# bluepill-breakout.net
KiCad netlist of a schematic drawn in EAGLE
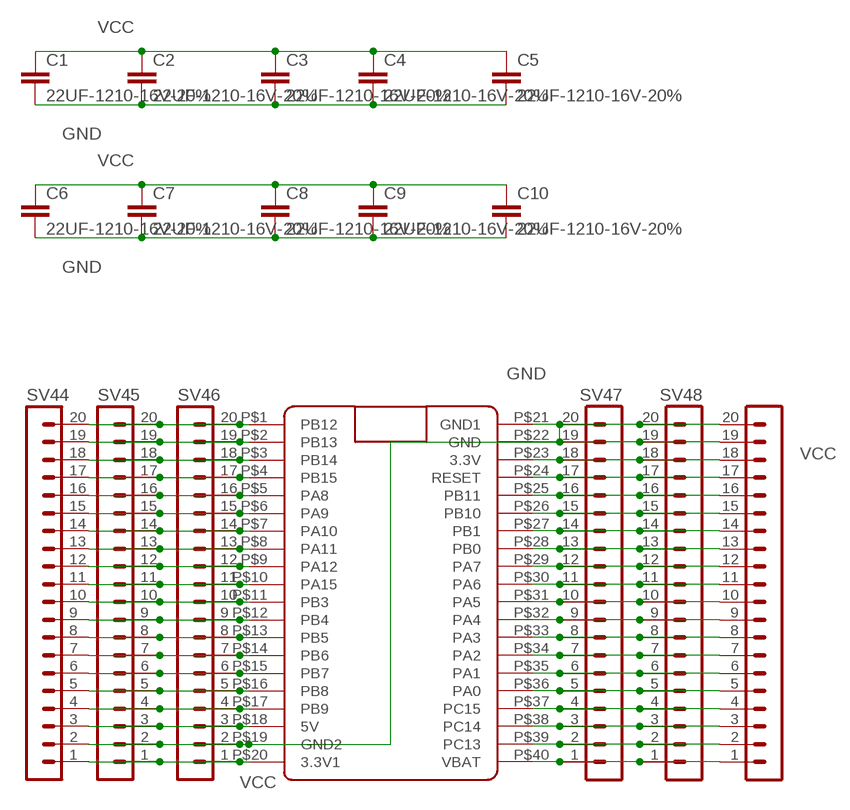
[diagram p0: schematic, sheet 1]
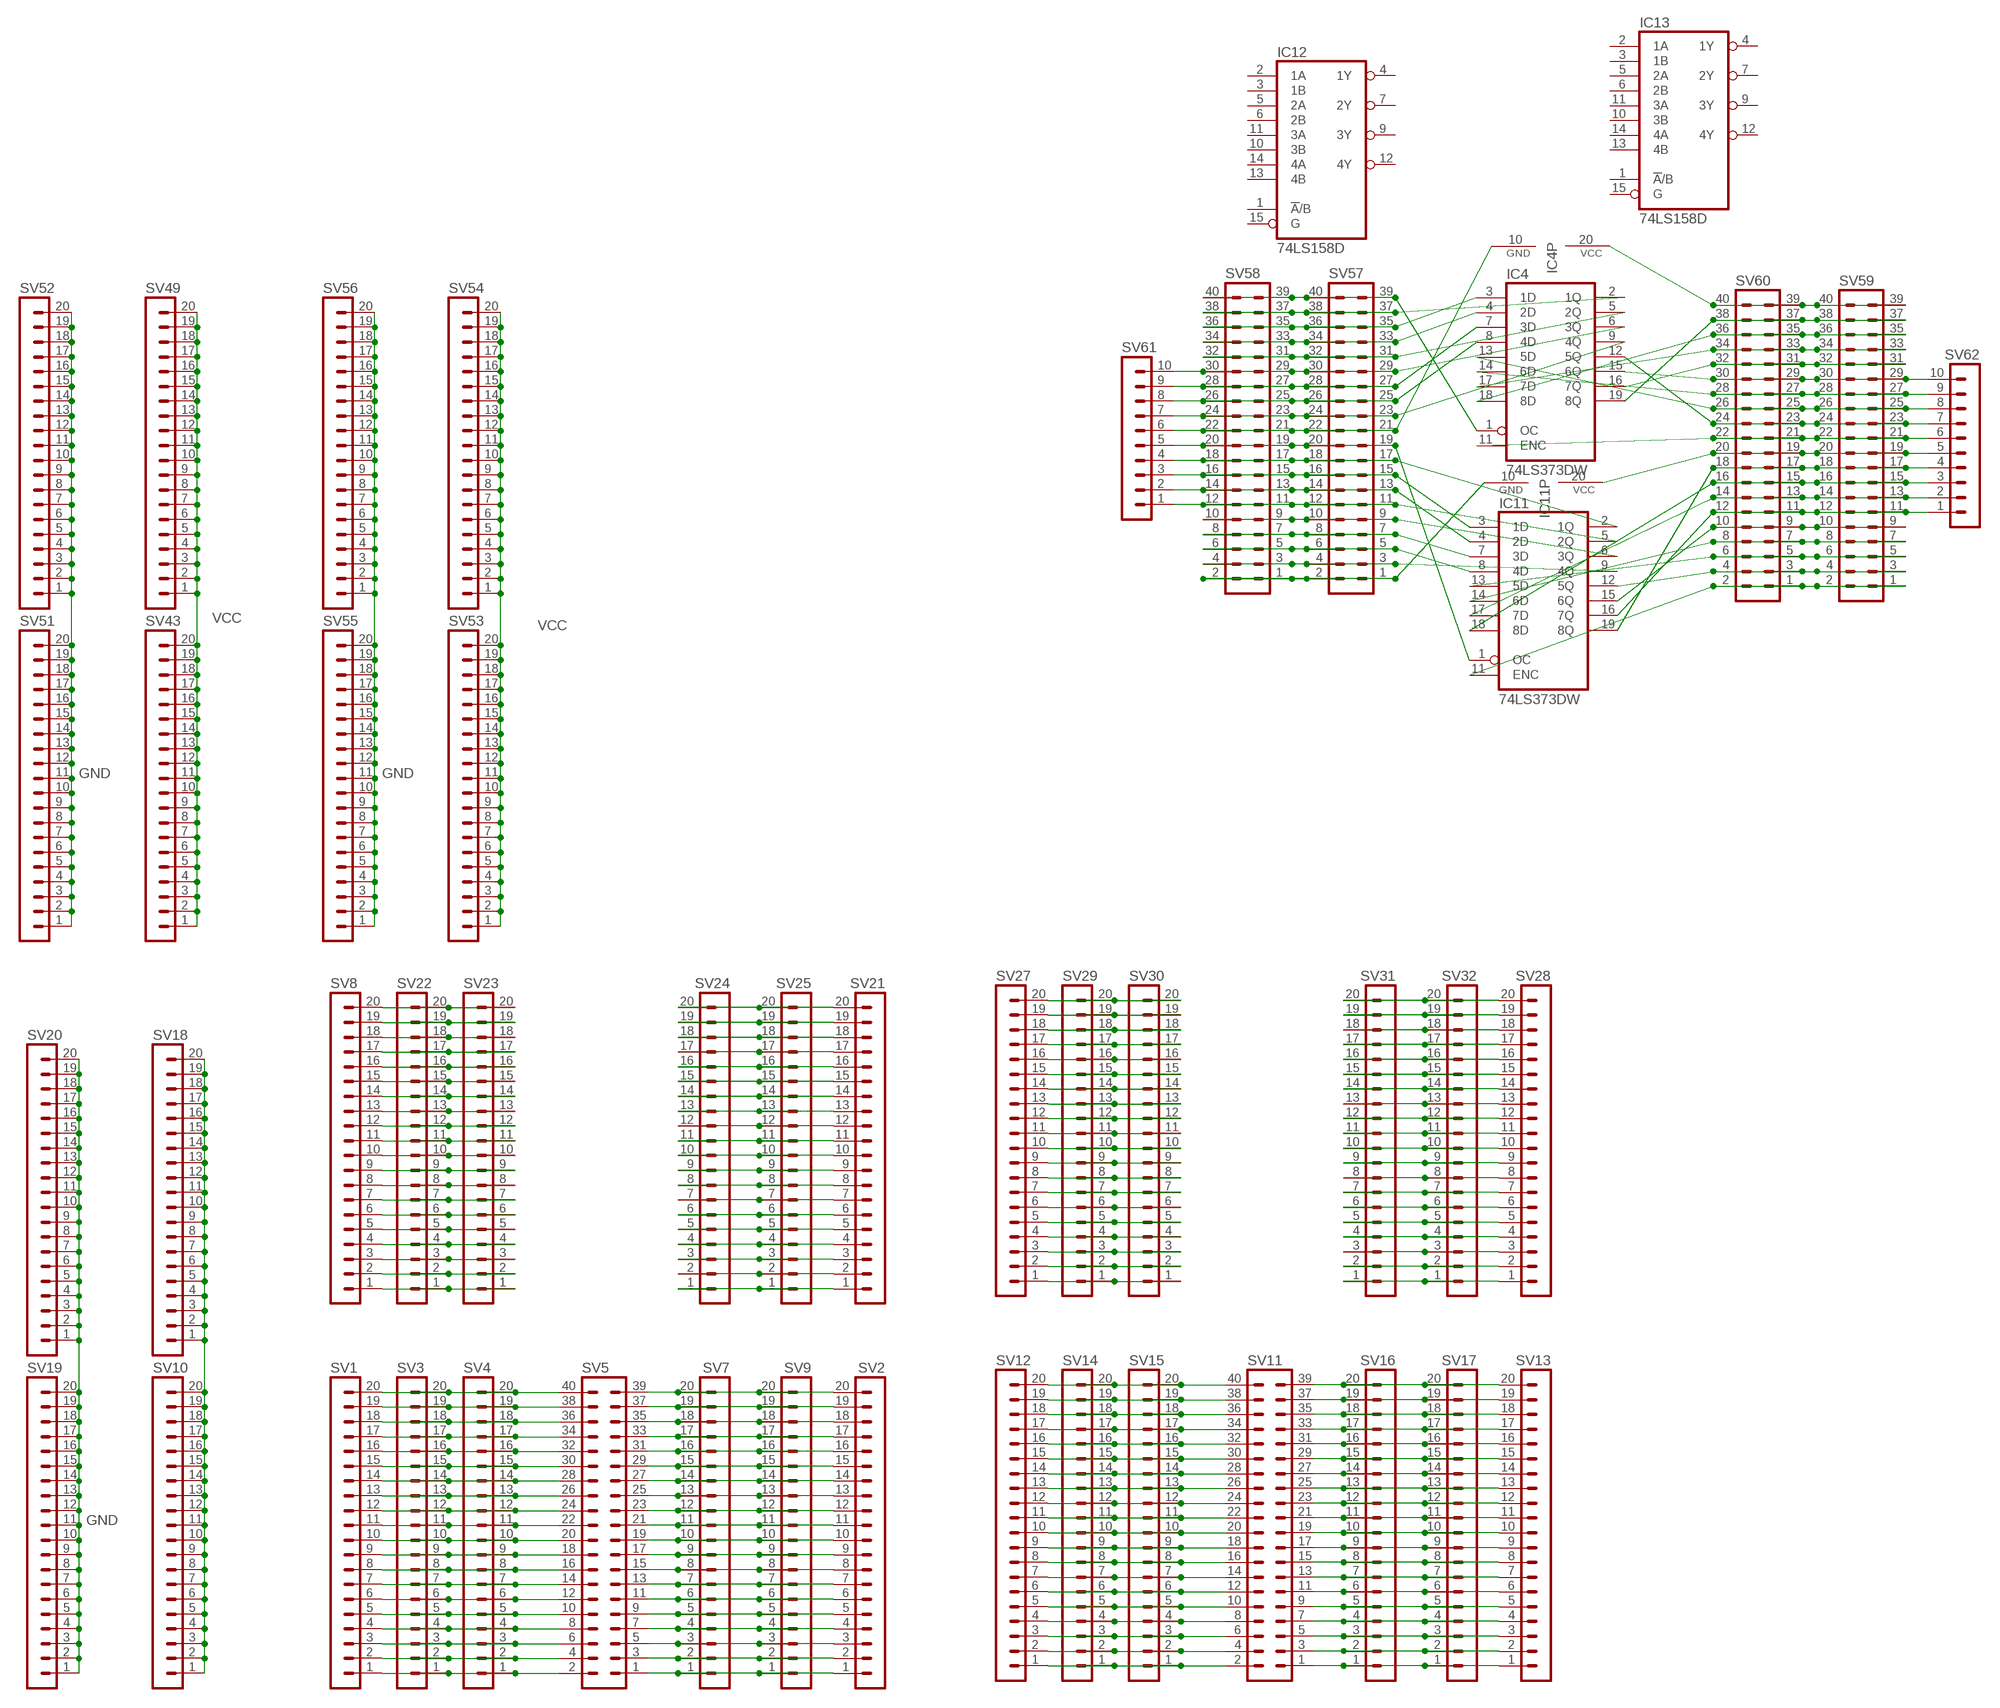
[diagram p1: schematic, sheet 2, part 1 of 2]
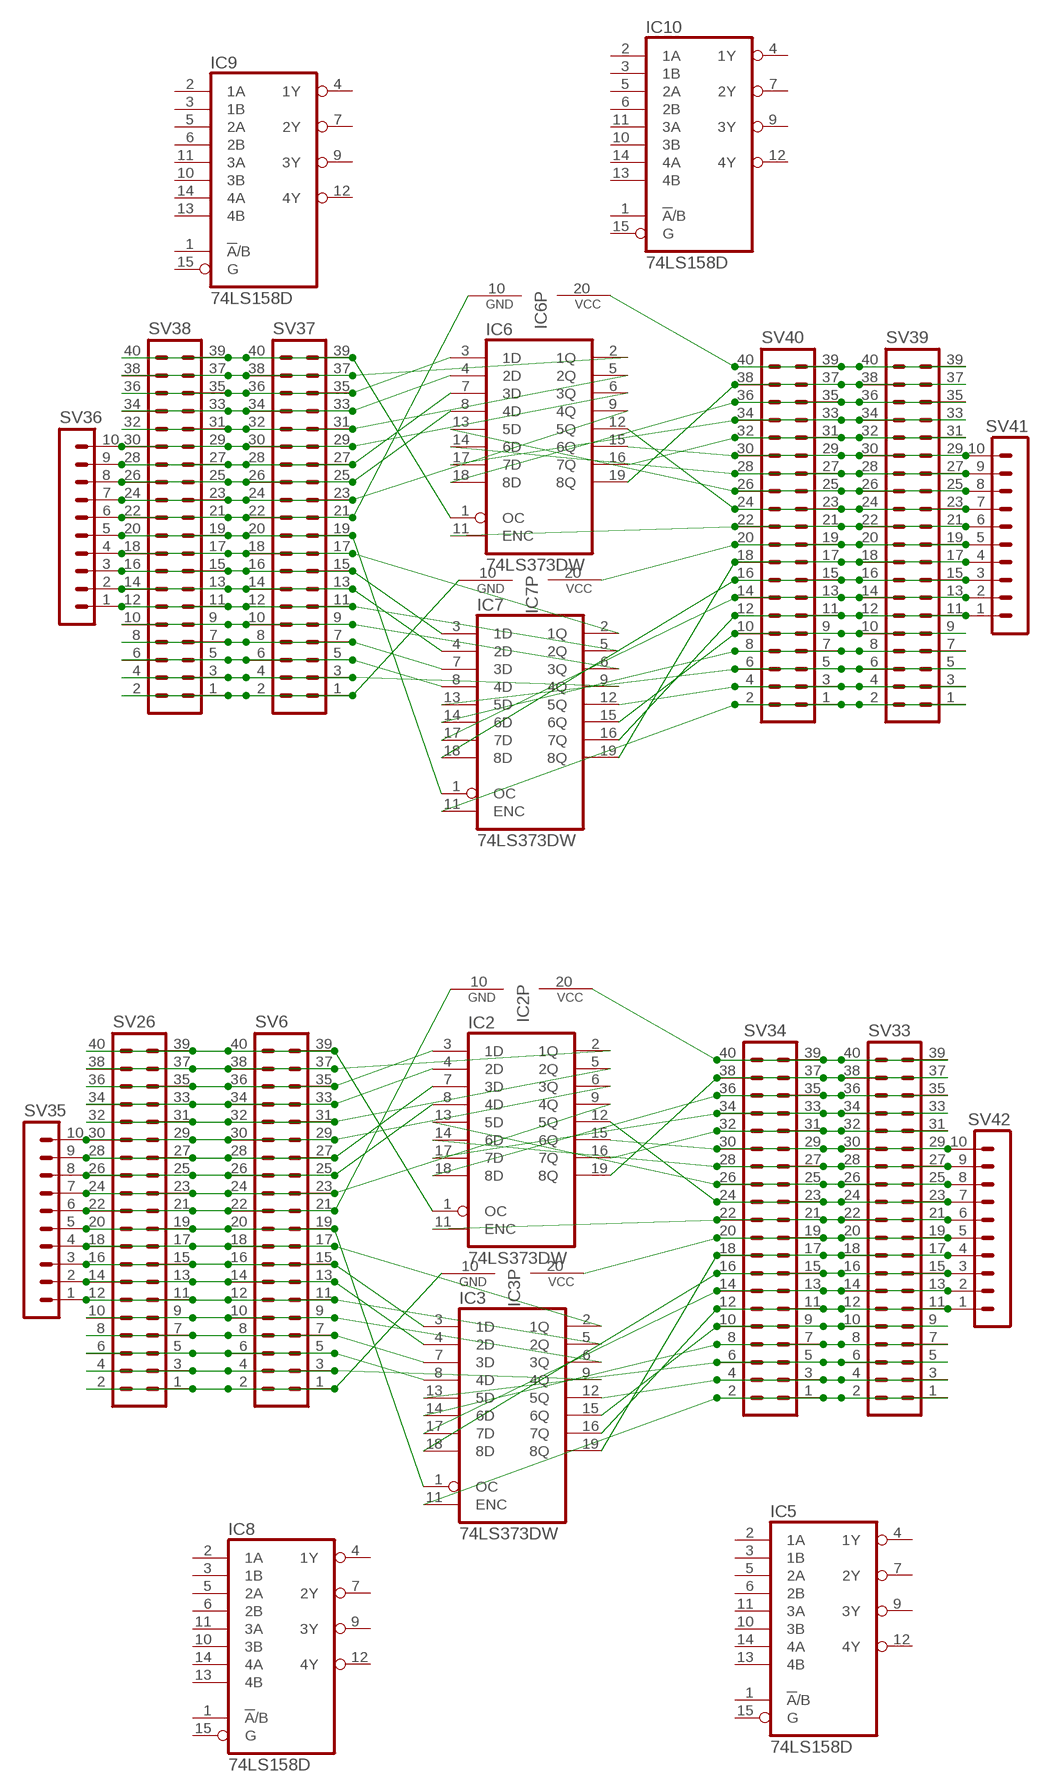
[diagram p2: schematic, sheet 2, part 2 of 2]

(export (version "E")
  (design (tool "Eeschema 10.0.6"))
  (components
    (comp (ref "C1")
      (value "22UF-1210-16V-20%")
      (footprint "eagle-import:1210")
      (libsource (lib "eagle-import") (part "22UF-1210-16V-20%"))
    )
    (comp (ref "C2")
      (value "22UF-1210-16V-20%")
      (footprint "eagle-import:1210")
      (libsource (lib "eagle-import") (part "22UF-1210-16V-20%"))
    )
    (comp (ref "C3")
      (value "22UF-1210-16V-20%")
      (footprint "eagle-import:1210")
      (libsource (lib "eagle-import") (part "22UF-1210-16V-20%"))
    )
    (comp (ref "C4")
      (value "22UF-1210-16V-20%")
      (footprint "eagle-import:1210")
      (libsource (lib "eagle-import") (part "22UF-1210-16V-20%"))
    )
    (comp (ref "C5")
      (value "22UF-1210-16V-20%")
      (footprint "eagle-import:1210")
      (libsource (lib "eagle-import") (part "22UF-1210-16V-20%"))
    )
    (comp (ref "C6")
      (value "22UF-1210-16V-20%")
      (footprint "eagle-import:1210")
      (libsource (lib "eagle-import") (part "22UF-1210-16V-20%"))
    )
    (comp (ref "C7")
      (value "22UF-1210-16V-20%")
      (footprint "eagle-import:1210")
      (libsource (lib "eagle-import") (part "22UF-1210-16V-20%"))
    )
    (comp (ref "C8")
      (value "22UF-1210-16V-20%")
      (footprint "eagle-import:1210")
      (libsource (lib "eagle-import") (part "22UF-1210-16V-20%"))
    )
    (comp (ref "C9")
      (value "22UF-1210-16V-20%")
      (footprint "eagle-import:1210")
      (libsource (lib "eagle-import") (part "22UF-1210-16V-20%"))
    )
    (comp (ref "C10")
      (value "22UF-1210-16V-20%")
      (footprint "eagle-import:1210")
      (libsource (lib "eagle-import") (part "22UF-1210-16V-20%"))
    )
    (comp (ref "SV44")
      (value "MA20-1")
      (footprint "eagle-import:MA20-1")
      (libsource (lib "eagle-import") (part "MA20-1"))
    )
    (comp (ref "SV45")
      (value "MA20-1")
      (footprint "eagle-import:MA20-1")
      (libsource (lib "eagle-import") (part "MA20-1"))
    )
    (comp (ref "SV46")
      (value "MA20-1")
      (footprint "eagle-import:MA20-1")
      (libsource (lib "eagle-import") (part "MA20-1"))
    )
    (comp (ref "SV47")
      (value "MA20-1")
      (footprint "eagle-import:MA20-1")
      (libsource (lib "eagle-import") (part "MA20-1"))
    )
    (comp (ref "SV48")
      (value "MA20-1")
      (footprint "eagle-import:MA20-1")
      (libsource (lib "eagle-import") (part "MA20-1"))
    )
    (comp (ref "SV50")
      (value "MA20-1")
      (footprint "eagle-import:MA20-1")
      (libsource (lib "eagle-import") (part "MA20-1"))
    )
    (comp (ref "U$1")
      (value "BLUE_PILLADVANCED")
      (footprint "eagle-import:BLUE_PILL_ADV")
      (libsource (lib "eagle-import") (part "BLUE_PILLADVANCED"))
    )
    (comp (ref "IC2")
      (value "74LS373DW")
      (footprint "eagle-import:SO20W")
      (libsource (lib "eagle-import") (part "74373DWLS"))
    )
    (comp (ref "IC3")
      (value "74LS373DW")
      (footprint "eagle-import:SO20W")
      (libsource (lib "eagle-import") (part "74373DWLS"))
    )
    (comp (ref "IC4")
      (value "74LS373DW")
      (footprint "eagle-import:SO20W")
      (libsource (lib "eagle-import") (part "74373DWLS"))
    )
    (comp (ref "IC5")
      (value "74LS158D")
      (footprint "eagle-import:SO16")
      (libsource (lib "eagle-import") (part "74158DLS"))
    )
    (comp (ref "IC6")
      (value "74LS373DW")
      (footprint "eagle-import:SO20W")
      (libsource (lib "eagle-import") (part "74373DWLS"))
    )
    (comp (ref "IC7")
      (value "74LS373DW")
      (footprint "eagle-import:SO20W")
      (libsource (lib "eagle-import") (part "74373DWLS"))
    )
    (comp (ref "IC8")
      (value "74LS158D")
      (footprint "eagle-import:SO16")
      (libsource (lib "eagle-import") (part "74158DLS"))
    )
    (comp (ref "IC9")
      (value "74LS158D")
      (footprint "eagle-import:SO16")
      (libsource (lib "eagle-import") (part "74158DLS"))
    )
    (comp (ref "IC10")
      (value "74LS158D")
      (footprint "eagle-import:SO16")
      (libsource (lib "eagle-import") (part "74158DLS"))
    )
    (comp (ref "IC11")
      (value "74LS373DW")
      (footprint "eagle-import:SO20W")
      (libsource (lib "eagle-import") (part "74373DWLS"))
    )
    (comp (ref "IC12")
      (value "74LS158D")
      (footprint "eagle-import:SO16")
      (libsource (lib "eagle-import") (part "74158DLS"))
    )
    (comp (ref "IC13")
      (value "74LS158D")
      (footprint "eagle-import:SO16")
      (libsource (lib "eagle-import") (part "74158DLS"))
    )
    (comp (ref "SV1")
      (value "MA20-1")
      (footprint "eagle-import:MA20-1")
      (libsource (lib "eagle-import") (part "MA20-1"))
    )
    (comp (ref "SV2")
      (value "MA20-1")
      (footprint "eagle-import:MA20-1")
      (libsource (lib "eagle-import") (part "MA20-1"))
    )
    (comp (ref "SV3")
      (value "MA20-1")
      (footprint "eagle-import:MA20-1")
      (libsource (lib "eagle-import") (part "MA20-1"))
    )
    (comp (ref "SV4")
      (value "MA20-1")
      (footprint "eagle-import:MA20-1")
      (libsource (lib "eagle-import") (part "MA20-1"))
    )
    (comp (ref "SV5")
      (value "MA20-2")
      (footprint "eagle-import:MA20-2")
      (libsource (lib "eagle-import") (part "MA20-2"))
    )
    (comp (ref "SV6")
      (value "MA20-2")
      (footprint "eagle-import:MA20-2")
      (libsource (lib "eagle-import") (part "MA20-2"))
    )
    (comp (ref "SV7")
      (value "MA20-1")
      (footprint "eagle-import:MA20-1")
      (libsource (lib "eagle-import") (part "MA20-1"))
    )
    (comp (ref "SV8")
      (value "MA20-1")
      (footprint "eagle-import:MA20-1")
      (libsource (lib "eagle-import") (part "MA20-1"))
    )
    (comp (ref "SV9")
      (value "MA20-1")
      (footprint "eagle-import:MA20-1")
      (libsource (lib "eagle-import") (part "MA20-1"))
    )
    (comp (ref "SV10")
      (value "MA20-1")
      (footprint "eagle-import:MA20-1")
      (libsource (lib "eagle-import") (part "MA20-1"))
    )
    (comp (ref "SV11")
      (value "MA20-2")
      (footprint "eagle-import:MA20-2")
      (libsource (lib "eagle-import") (part "MA20-2"))
    )
    (comp (ref "SV12")
      (value "MA20-1")
      (footprint "eagle-import:MA20-1")
      (libsource (lib "eagle-import") (part "MA20-1"))
    )
    (comp (ref "SV13")
      (value "MA20-1")
      (footprint "eagle-import:MA20-1")
      (libsource (lib "eagle-import") (part "MA20-1"))
    )
    (comp (ref "SV14")
      (value "MA20-1")
      (footprint "eagle-import:MA20-1")
      (libsource (lib "eagle-import") (part "MA20-1"))
    )
    (comp (ref "SV15")
      (value "MA20-1")
      (footprint "eagle-import:MA20-1")
      (libsource (lib "eagle-import") (part "MA20-1"))
    )
    (comp (ref "SV16")
      (value "MA20-1")
      (footprint "eagle-import:MA20-1")
      (libsource (lib "eagle-import") (part "MA20-1"))
    )
    (comp (ref "SV17")
      (value "MA20-1")
      (footprint "eagle-import:MA20-1")
      (libsource (lib "eagle-import") (part "MA20-1"))
    )
    (comp (ref "SV18")
      (value "MA20-1")
      (footprint "eagle-import:MA20-1")
      (libsource (lib "eagle-import") (part "MA20-1"))
    )
    (comp (ref "SV19")
      (value "MA20-1")
      (footprint "eagle-import:MA20-1")
      (libsource (lib "eagle-import") (part "MA20-1"))
    )
    (comp (ref "SV20")
      (value "MA20-1")
      (footprint "eagle-import:MA20-1")
      (libsource (lib "eagle-import") (part "MA20-1"))
    )
    (comp (ref "SV21")
      (value "MA20-1")
      (footprint "eagle-import:MA20-1")
      (libsource (lib "eagle-import") (part "MA20-1"))
    )
    (comp (ref "SV22")
      (value "MA20-1")
      (footprint "eagle-import:MA20-1")
      (libsource (lib "eagle-import") (part "MA20-1"))
    )
    (comp (ref "SV23")
      (value "MA20-1")
      (footprint "eagle-import:MA20-1")
      (libsource (lib "eagle-import") (part "MA20-1"))
    )
    (comp (ref "SV24")
      (value "MA20-1")
      (footprint "eagle-import:MA20-1")
      (libsource (lib "eagle-import") (part "MA20-1"))
    )
    (comp (ref "SV25")
      (value "MA20-1")
      (footprint "eagle-import:MA20-1")
      (libsource (lib "eagle-import") (part "MA20-1"))
    )
    (comp (ref "SV26")
      (value "MA20-2")
      (footprint "eagle-import:MA20-2")
      (libsource (lib "eagle-import") (part "MA20-2"))
    )
    (comp (ref "SV27")
      (value "MA20-1")
      (footprint "eagle-import:MA20-1")
      (libsource (lib "eagle-import") (part "MA20-1"))
    )
    (comp (ref "SV28")
      (value "MA20-1")
      (footprint "eagle-import:MA20-1")
      (libsource (lib "eagle-import") (part "MA20-1"))
    )
    (comp (ref "SV29")
      (value "MA20-1")
      (footprint "eagle-import:MA20-1")
      (libsource (lib "eagle-import") (part "MA20-1"))
    )
    (comp (ref "SV30")
      (value "MA20-1")
      (footprint "eagle-import:MA20-1")
      (libsource (lib "eagle-import") (part "MA20-1"))
    )
    (comp (ref "SV31")
      (value "MA20-1")
      (footprint "eagle-import:MA20-1")
      (libsource (lib "eagle-import") (part "MA20-1"))
    )
    (comp (ref "SV32")
      (value "MA20-1")
      (footprint "eagle-import:MA20-1")
      (libsource (lib "eagle-import") (part "MA20-1"))
    )
    (comp (ref "SV33")
      (value "MA20-2")
      (footprint "eagle-import:MA20-2")
      (libsource (lib "eagle-import") (part "MA20-2"))
    )
    (comp (ref "SV34")
      (value "MA20-2")
      (footprint "eagle-import:MA20-2")
      (libsource (lib "eagle-import") (part "MA20-2"))
    )
    (comp (ref "SV35")
      (value "MA10-1")
      (footprint "eagle-import:MA10-1")
      (libsource (lib "eagle-import") (part "MA10-1"))
    )
    (comp (ref "SV36")
      (value "MA10-1")
      (footprint "eagle-import:MA10-1")
      (libsource (lib "eagle-import") (part "MA10-1"))
    )
    (comp (ref "SV37")
      (value "MA20-2")
      (footprint "eagle-import:MA20-2")
      (libsource (lib "eagle-import") (part "MA20-2"))
    )
    (comp (ref "SV38")
      (value "MA20-2")
      (footprint "eagle-import:MA20-2")
      (libsource (lib "eagle-import") (part "MA20-2"))
    )
    (comp (ref "SV39")
      (value "MA20-2")
      (footprint "eagle-import:MA20-2")
      (libsource (lib "eagle-import") (part "MA20-2"))
    )
    (comp (ref "SV40")
      (value "MA20-2")
      (footprint "eagle-import:MA20-2")
      (libsource (lib "eagle-import") (part "MA20-2"))
    )
    (comp (ref "SV41")
      (value "MA10-1")
      (footprint "eagle-import:MA10-1")
      (libsource (lib "eagle-import") (part "MA10-1"))
    )
    (comp (ref "SV42")
      (value "MA10-1")
      (footprint "eagle-import:MA10-1")
      (libsource (lib "eagle-import") (part "MA10-1"))
    )
    (comp (ref "SV43")
      (value "MA20-1")
      (footprint "eagle-import:MA20-1")
      (libsource (lib "eagle-import") (part "MA20-1"))
    )
    (comp (ref "SV49")
      (value "MA20-1")
      (footprint "eagle-import:MA20-1")
      (libsource (lib "eagle-import") (part "MA20-1"))
    )
    (comp (ref "SV51")
      (value "MA20-1")
      (footprint "eagle-import:MA20-1")
      (libsource (lib "eagle-import") (part "MA20-1"))
    )
    (comp (ref "SV52")
      (value "MA20-1")
      (footprint "eagle-import:MA20-1")
      (libsource (lib "eagle-import") (part "MA20-1"))
    )
    (comp (ref "SV53")
      (value "MA20-1")
      (footprint "eagle-import:MA20-1")
      (libsource (lib "eagle-import") (part "MA20-1"))
    )
    (comp (ref "SV54")
      (value "MA20-1")
      (footprint "eagle-import:MA20-1")
      (libsource (lib "eagle-import") (part "MA20-1"))
    )
    (comp (ref "SV55")
      (value "MA20-1")
      (footprint "eagle-import:MA20-1")
      (libsource (lib "eagle-import") (part "MA20-1"))
    )
    (comp (ref "SV56")
      (value "MA20-1")
      (footprint "eagle-import:MA20-1")
      (libsource (lib "eagle-import") (part "MA20-1"))
    )
    (comp (ref "SV57")
      (value "MA20-2")
      (footprint "eagle-import:MA20-2")
      (libsource (lib "eagle-import") (part "MA20-2"))
    )
    (comp (ref "SV58")
      (value "MA20-2")
      (footprint "eagle-import:MA20-2")
      (libsource (lib "eagle-import") (part "MA20-2"))
    )
    (comp (ref "SV59")
      (value "MA20-2")
      (footprint "eagle-import:MA20-2")
      (libsource (lib "eagle-import") (part "MA20-2"))
    )
    (comp (ref "SV60")
      (value "MA20-2")
      (footprint "eagle-import:MA20-2")
      (libsource (lib "eagle-import") (part "MA20-2"))
    )
    (comp (ref "SV61")
      (value "MA10-1")
      (footprint "eagle-import:MA10-1")
      (libsource (lib "eagle-import") (part "MA10-1"))
    )
    (comp (ref "SV62")
      (value "MA10-1")
      (footprint "eagle-import:MA10-1")
      (libsource (lib "eagle-import") (part "MA10-1"))
    )
  )
  (nets
    (net (code "1") (name "GND") (class "Default")
      (node (ref "C1") (pin "2") (pinfunction "2_2") (pintype "passive"))
      (node (ref "C10") (pin "2") (pinfunction "2_2") (pintype "passive"))
      (node (ref "C2") (pin "2") (pinfunction "2_2") (pintype "passive"))
      (node (ref "C3") (pin "2") (pinfunction "2_2") (pintype "passive"))
      (node (ref "C4") (pin "2") (pinfunction "2_2") (pintype "passive"))
      (node (ref "C5") (pin "2") (pinfunction "2_2") (pintype "passive"))
      (node (ref "C6") (pin "2") (pinfunction "2_2") (pintype "passive"))
      (node (ref "C7") (pin "2") (pinfunction "2_2") (pintype "passive"))
      (node (ref "C8") (pin "2") (pinfunction "2_2") (pintype "passive"))
      (node (ref "C9") (pin "2") (pinfunction "2_2") (pintype "passive"))
      (node (ref "SV19") (pin "1") (pinfunction "1_1") (pintype "passive"))
      (node (ref "SV19") (pin "10") (pinfunction "10_10") (pintype "passive"))
      (node (ref "SV19") (pin "11") (pinfunction "11_11") (pintype "passive"))
      (node (ref "SV19") (pin "12") (pinfunction "12_12") (pintype "passive"))
      (node (ref "SV19") (pin "13") (pinfunction "13_13") (pintype "passive"))
      (node (ref "SV19") (pin "14") (pinfunction "14_14") (pintype "passive"))
      (node (ref "SV19") (pin "15") (pinfunction "15_15") (pintype "passive"))
      (node (ref "SV19") (pin "16") (pinfunction "16_16") (pintype "passive"))
      (node (ref "SV19") (pin "17") (pinfunction "17_17") (pintype "passive"))
      (node (ref "SV19") (pin "18") (pinfunction "18_18") (pintype "passive"))
      (node (ref "SV19") (pin "19") (pinfunction "19_19") (pintype "passive"))
      (node (ref "SV19") (pin "2") (pinfunction "2_2") (pintype "passive"))
      (node (ref "SV19") (pin "20") (pinfunction "20_20") (pintype "passive"))
      (node (ref "SV19") (pin "3") (pinfunction "3_3") (pintype "passive"))
      (node (ref "SV19") (pin "4") (pinfunction "4_4") (pintype "passive"))
      (node (ref "SV19") (pin "5") (pinfunction "5_5") (pintype "passive"))
      (node (ref "SV19") (pin "6") (pinfunction "6_6") (pintype "passive"))
      (node (ref "SV19") (pin "7") (pinfunction "7_7") (pintype "passive"))
      (node (ref "SV19") (pin "8") (pinfunction "8_8") (pintype "passive"))
      (node (ref "SV19") (pin "9") (pinfunction "9_9") (pintype "passive"))
      (node (ref "SV20") (pin "1") (pinfunction "1_1") (pintype "passive"))
      (node (ref "SV20") (pin "10") (pinfunction "10_10") (pintype "passive"))
      (node (ref "SV20") (pin "11") (pinfunction "11_11") (pintype "passive"))
      (node (ref "SV20") (pin "12") (pinfunction "12_12") (pintype "passive"))
      (node (ref "SV20") (pin "13") (pinfunction "13_13") (pintype "passive"))
      (node (ref "SV20") (pin "14") (pinfunction "14_14") (pintype "passive"))
      (node (ref "SV20") (pin "15") (pinfunction "15_15") (pintype "passive"))
      (node (ref "SV20") (pin "16") (pinfunction "16_16") (pintype "passive"))
      (node (ref "SV20") (pin "17") (pinfunction "17_17") (pintype "passive"))
      (node (ref "SV20") (pin "18") (pinfunction "18_18") (pintype "passive"))
      (node (ref "SV20") (pin "19") (pinfunction "19_19") (pintype "passive"))
      (node (ref "SV20") (pin "2") (pinfunction "2_2") (pintype "passive"))
      (node (ref "SV20") (pin "20") (pinfunction "20_20") (pintype "passive"))
      (node (ref "SV20") (pin "3") (pinfunction "3_3") (pintype "passive"))
      (node (ref "SV20") (pin "4") (pinfunction "4_4") (pintype "passive"))
      (node (ref "SV20") (pin "5") (pinfunction "5_5") (pintype "passive"))
      (node (ref "SV20") (pin "6") (pinfunction "6_6") (pintype "passive"))
      (node (ref "SV20") (pin "7") (pinfunction "7_7") (pintype "passive"))
      (node (ref "SV20") (pin "8") (pinfunction "8_8") (pintype "passive"))
      (node (ref "SV20") (pin "9") (pinfunction "9_9") (pintype "passive"))
      (node (ref "SV44") (pin "2") (pinfunction "2_2") (pintype "passive"))
      (node (ref "SV45") (pin "2") (pinfunction "2_2") (pintype "passive"))
      (node (ref "SV46") (pin "2") (pinfunction "2_2") (pintype "passive"))
      (node (ref "SV47") (pin "19") (pinfunction "19_19") (pintype "passive"))
      (node (ref "SV47") (pin "20") (pinfunction "20_20") (pintype "passive"))
      (node (ref "SV48") (pin "19") (pinfunction "19_19") (pintype "passive"))
      (node (ref "SV48") (pin "20") (pinfunction "20_20") (pintype "passive"))
      (node (ref "SV50") (pin "19") (pinfunction "19_19") (pintype "passive"))
      (node (ref "SV50") (pin "20") (pinfunction "20_20") (pintype "passive"))
      (node (ref "SV51") (pin "1") (pinfunction "1_1") (pintype "passive"))
      (node (ref "SV51") (pin "10") (pinfunction "10_10") (pintype "passive"))
      (node (ref "SV51") (pin "11") (pinfunction "11_11") (pintype "passive"))
      (node (ref "SV51") (pin "12") (pinfunction "12_12") (pintype "passive"))
      (node (ref "SV51") (pin "13") (pinfunction "13_13") (pintype "passive"))
      (node (ref "SV51") (pin "14") (pinfunction "14_14") (pintype "passive"))
      (node (ref "SV51") (pin "15") (pinfunction "15_15") (pintype "passive"))
      (node (ref "SV51") (pin "16") (pinfunction "16_16") (pintype "passive"))
      (node (ref "SV51") (pin "17") (pinfunction "17_17") (pintype "passive"))
      (node (ref "SV51") (pin "18") (pinfunction "18_18") (pintype "passive"))
      (node (ref "SV51") (pin "19") (pinfunction "19_19") (pintype "passive"))
      (node (ref "SV51") (pin "2") (pinfunction "2_2") (pintype "passive"))
      (node (ref "SV51") (pin "20") (pinfunction "20_20") (pintype "passive"))
      (node (ref "SV51") (pin "3") (pinfunction "3_3") (pintype "passive"))
      (node (ref "SV51") (pin "4") (pinfunction "4_4") (pintype "passive"))
      (node (ref "SV51") (pin "5") (pinfunction "5_5") (pintype "passive"))
      (node (ref "SV51") (pin "6") (pinfunction "6_6") (pintype "passive"))
      (node (ref "SV51") (pin "7") (pinfunction "7_7") (pintype "passive"))
      (node (ref "SV51") (pin "8") (pinfunction "8_8") (pintype "passive"))
      (node (ref "SV51") (pin "9") (pinfunction "9_9") (pintype "passive"))
      (node (ref "SV52") (pin "1") (pinfunction "1_1") (pintype "passive"))
      (node (ref "SV52") (pin "10") (pinfunction "10_10") (pintype "passive"))
      (node (ref "SV52") (pin "11") (pinfunction "11_11") (pintype "passive"))
      (node (ref "SV52") (pin "12") (pinfunction "12_12") (pintype "passive"))
      (node (ref "SV52") (pin "13") (pinfunction "13_13") (pintype "passive"))
      (node (ref "SV52") (pin "14") (pinfunction "14_14") (pintype "passive"))
      (node (ref "SV52") (pin "15") (pinfunction "15_15") (pintype "passive"))
      (node (ref "SV52") (pin "16") (pinfunction "16_16") (pintype "passive"))
      (node (ref "SV52") (pin "17") (pinfunction "17_17") (pintype "passive"))
      (node (ref "SV52") (pin "18") (pinfunction "18_18") (pintype "passive"))
      (node (ref "SV52") (pin "19") (pinfunction "19_19") (pintype "passive"))
      (node (ref "SV52") (pin "2") (pinfunction "2_2") (pintype "passive"))
      (node (ref "SV52") (pin "20") (pinfunction "20_20") (pintype "passive"))
      (node (ref "SV52") (pin "3") (pinfunction "3_3") (pintype "passive"))
      (node (ref "SV52") (pin "4") (pinfunction "4_4") (pintype "passive"))
      (node (ref "SV52") (pin "5") (pinfunction "5_5") (pintype "passive"))
      (node (ref "SV52") (pin "6") (pinfunction "6_6") (pintype "passive"))
      (node (ref "SV52") (pin "7") (pinfunction "7_7") (pintype "passive"))
      (node (ref "SV52") (pin "8") (pinfunction "8_8") (pintype "passive"))
      (node (ref "SV52") (pin "9") (pinfunction "9_9") (pintype "passive"))
      (node (ref "SV55") (pin "1") (pinfunction "1_1") (pintype "passive"))
      (node (ref "SV55") (pin "10") (pinfunction "10_10") (pintype "passive"))
      (node (ref "SV55") (pin "11") (pinfunction "11_11") (pintype "passive"))
      (node (ref "SV55") (pin "12") (pinfunction "12_12") (pintype "passive"))
      (node (ref "SV55") (pin "13") (pinfunction "13_13") (pintype "passive"))
      (node (ref "SV55") (pin "14") (pinfunction "14_14") (pintype "passive"))
      (node (ref "SV55") (pin "15") (pinfunction "15_15") (pintype "passive"))
      (node (ref "SV55") (pin "16") (pinfunction "16_16") (pintype "passive"))
      (node (ref "SV55") (pin "17") (pinfunction "17_17") (pintype "passive"))
      (node (ref "SV55") (pin "18") (pinfunction "18_18") (pintype "passive"))
      (node (ref "SV55") (pin "19") (pinfunction "19_19") (pintype "passive"))
      (node (ref "SV55") (pin "2") (pinfunction "2_2") (pintype "passive"))
      (node (ref "SV55") (pin "20") (pinfunction "20_20") (pintype "passive"))
      (node (ref "SV55") (pin "3") (pinfunction "3_3") (pintype "passive"))
      (node (ref "SV55") (pin "4") (pinfunction "4_4") (pintype "passive"))
      (node (ref "SV55") (pin "5") (pinfunction "5_5") (pintype "passive"))
      (node (ref "SV55") (pin "6") (pinfunction "6_6") (pintype "passive"))
      (node (ref "SV55") (pin "7") (pinfunction "7_7") (pintype "passive"))
      (node (ref "SV55") (pin "8") (pinfunction "8_8") (pintype "passive"))
      (node (ref "SV55") (pin "9") (pinfunction "9_9") (pintype "passive"))
      (node (ref "SV56") (pin "1") (pinfunction "1_1") (pintype "passive"))
      (node (ref "SV56") (pin "10") (pinfunction "10_10") (pintype "passive"))
      (node (ref "SV56") (pin "11") (pinfunction "11_11") (pintype "passive"))
      (node (ref "SV56") (pin "12") (pinfunction "12_12") (pintype "passive"))
      (node (ref "SV56") (pin "13") (pinfunction "13_13") (pintype "passive"))
      (node (ref "SV56") (pin "14") (pinfunction "14_14") (pintype "passive"))
      (node (ref "SV56") (pin "15") (pinfunction "15_15") (pintype "passive"))
      (node (ref "SV56") (pin "16") (pinfunction "16_16") (pintype "passive"))
      (node (ref "SV56") (pin "17") (pinfunction "17_17") (pintype "passive"))
      (node (ref "SV56") (pin "18") (pinfunction "18_18") (pintype "passive"))
      (node (ref "SV56") (pin "19") (pinfunction "19_19") (pintype "passive"))
      (node (ref "SV56") (pin "2") (pinfunction "2_2") (pintype "passive"))
      (node (ref "SV56") (pin "20") (pinfunction "20_20") (pintype "passive"))
      (node (ref "SV56") (pin "3") (pinfunction "3_3") (pintype "passive"))
      (node (ref "SV56") (pin "4") (pinfunction "4_4") (pintype "passive"))
      (node (ref "SV56") (pin "5") (pinfunction "5_5") (pintype "passive"))
      (node (ref "SV56") (pin "6") (pinfunction "6_6") (pintype "passive"))
      (node (ref "SV56") (pin "7") (pinfunction "7_7") (pintype "passive"))
      (node (ref "SV56") (pin "8") (pinfunction "8_8") (pintype "passive"))
      (node (ref "SV56") (pin "9") (pinfunction "9_9") (pintype "passive"))
      (node (ref "U$1") (pin "P$19") (pinfunction "GND2_P$19") (pintype "bidirectional"))
      (node (ref "U$1") (pin "P$21") (pinfunction "GND1_P$21") (pintype "power_in"))
      (node (ref "U$1") (pin "P$22") (pinfunction "GND_P$22") (pintype "bidirectional"))
    )
    (net (code "2") (name "Net-(IC2A-1D)") (class "Default")
      (node (ref "IC2") (pin "3") (pinfunction "1D_3") (pintype "input"))
      (node (ref "SV26") (pin "35") (pinfunction "35_35") (pintype "passive"))
      (node (ref "SV26") (pin "36") (pinfunction "36_36") (pintype "passive"))
      (node (ref "SV6") (pin "35") (pinfunction "35_35") (pintype "passive"))
      (node (ref "SV6") (pin "36") (pinfunction "36_36") (pintype "passive"))
    )
    (net (code "3") (name "Net-(IC2A-1Q)") (class "Default")
      (node (ref "IC2") (pin "2") (pinfunction "1Q_2") (pintype "tri_state"))
      (node (ref "SV26") (pin "37") (pinfunction "37_37") (pintype "passive"))
      (node (ref "SV26") (pin "38") (pinfunction "38_38") (pintype "passive"))
      (node (ref "SV6") (pin "37") (pinfunction "37_37") (pintype "passive"))
      (node (ref "SV6") (pin "38") (pinfunction "38_38") (pintype "passive"))
    )
    (net (code "4") (name "Net-(IC2A-2D)") (class "Default")
      (node (ref "IC2") (pin "4") (pinfunction "2D_4") (pintype "input"))
      (node (ref "SV26") (pin "33") (pinfunction "33_33") (pintype "passive"))
      (node (ref "SV26") (pin "34") (pinfunction "34_34") (pintype "passive"))
      (node (ref "SV6") (pin "33") (pinfunction "33_33") (pintype "passive"))
      (node (ref "SV6") (pin "34") (pinfunction "34_34") (pintype "passive"))
    )
    (net (code "5") (name "Net-(IC2A-2Q)") (class "Default")
      (node (ref "IC2") (pin "5") (pinfunction "2Q_5") (pintype "tri_state"))
      (node (ref "SV26") (pin "31") (pinfunction "31_31") (pintype "passive"))
      (node (ref "SV26") (pin "32") (pinfunction "32_32") (pintype "passive"))
      (node (ref "SV6") (pin "31") (pinfunction "31_31") (pintype "passive"))
      (node (ref "SV6") (pin "32") (pinfunction "32_32") (pintype "passive"))
    )
    (net (code "6") (name "Net-(IC2A-3D)") (class "Default")
      (node (ref "IC2") (pin "7") (pinfunction "3D_7") (pintype "input"))
      (node (ref "SV26") (pin "27") (pinfunction "27_27") (pintype "passive"))
      (node (ref "SV26") (pin "28") (pinfunction "28_28") (pintype "passive"))
      (node (ref "SV35") (pin "9") (pinfunction "9_9") (pintype "passive"))
      (node (ref "SV6") (pin "27") (pinfunction "27_27") (pintype "passive"))
      (node (ref "SV6") (pin "28") (pinfunction "28_28") (pintype "passive"))
    )
    (net (code "7") (name "Net-(IC2A-3Q)") (class "Default")
      (node (ref "IC2") (pin "6") (pinfunction "3Q_6") (pintype "tri_state"))
      (node (ref "SV26") (pin "29") (pinfunction "29_29") (pintype "passive"))
      (node (ref "SV26") (pin "30") (pinfunction "30_30") (pintype "passive"))
      (node (ref "SV35") (pin "10") (pinfunction "10_10") (pintype "passive"))
      (node (ref "SV6") (pin "29") (pinfunction "29_29") (pintype "passive"))
      (node (ref "SV6") (pin "30") (pinfunction "30_30") (pintype "passive"))
    )
    (net (code "8") (name "Net-(IC2A-4D)") (class "Default")
      (node (ref "IC2") (pin "8") (pinfunction "4D_8") (pintype "input"))
      (node (ref "SV26") (pin "25") (pinfunction "25_25") (pintype "passive"))
      (node (ref "SV26") (pin "26") (pinfunction "26_26") (pintype "passive"))
      (node (ref "SV35") (pin "8") (pinfunction "8_8") (pintype "passive"))
      (node (ref "SV6") (pin "25") (pinfunction "25_25") (pintype "passive"))
      (node (ref "SV6") (pin "26") (pinfunction "26_26") (pintype "passive"))
    )
    (net (code "9") (name "Net-(IC2A-4Q)") (class "Default")
      (node (ref "IC2") (pin "9") (pinfunction "4Q_9") (pintype "tri_state"))
      (node (ref "SV26") (pin "23") (pinfunction "23_23") (pintype "passive"))
      (node (ref "SV26") (pin "24") (pinfunction "24_24") (pintype "passive"))
      (node (ref "SV35") (pin "7") (pinfunction "7_7") (pintype "passive"))
      (node (ref "SV6") (pin "23") (pinfunction "23_23") (pintype "passive"))
      (node (ref "SV6") (pin "24") (pinfunction "24_24") (pintype "passive"))
    )
    (net (code "10") (name "Net-(IC2A-5D)") (class "Default")
      (node (ref "IC2") (pin "13") (pinfunction "5D_13") (pintype "input"))
      (node (ref "SV33") (pin "25") (pinfunction "25_25") (pintype "passive"))
      (node (ref "SV33") (pin "26") (pinfunction "26_26") (pintype "passive"))
      (node (ref "SV34") (pin "25") (pinfunction "25_25") (pintype "passive"))
      (node (ref "SV34") (pin "26") (pinfunction "26_26") (pintype "passive"))
      (node (ref "SV42") (pin "8") (pinfunction "8_8") (pintype "passive"))
    )
    (net (code "11") (name "Net-(IC2A-5Q)") (class "Default")
      (node (ref "IC2") (pin "12") (pinfunction "5Q_12") (pintype "tri_state"))
      (node (ref "SV33") (pin "23") (pinfunction "23_23") (pintype "passive"))
      (node (ref "SV33") (pin "24") (pinfunction "24_24") (pintype "passive"))
      (node (ref "SV34") (pin "23") (pinfunction "23_23") (pintype "passive"))
      (node (ref "SV34") (pin "24") (pinfunction "24_24") (pintype "passive"))
      (node (ref "SV42") (pin "7") (pinfunction "7_7") (pintype "passive"))
    )
    (net (code "12") (name "Net-(IC2A-6D)") (class "Default")
      (node (ref "IC2") (pin "14") (pinfunction "6D_14") (pintype "input"))
      (node (ref "SV33") (pin "27") (pinfunction "27_27") (pintype "passive"))
      (node (ref "SV33") (pin "28") (pinfunction "28_28") (pintype "passive"))
      (node (ref "SV34") (pin "27") (pinfunction "27_27") (pintype "passive"))
      (node (ref "SV34") (pin "28") (pinfunction "28_28") (pintype "passive"))
      (node (ref "SV42") (pin "9") (pinfunction "9_9") (pintype "passive"))
    )
    (net (code "13") (name "Net-(IC2A-6Q)") (class "Default")
      (node (ref "IC2") (pin "15") (pinfunction "6Q_15") (pintype "tri_state"))
      (node (ref "SV33") (pin "29") (pinfunction "29_29") (pintype "passive"))
      (node (ref "SV33") (pin "30") (pinfunction "30_30") (pintype "passive"))
      (node (ref "SV34") (pin "29") (pinfunction "29_29") (pintype "passive"))
      (node (ref "SV34") (pin "30") (pinfunction "30_30") (pintype "passive"))
      (node (ref "SV42") (pin "10") (pinfunction "10_10") (pintype "passive"))
    )
    (net (code "14") (name "Net-(IC2A-7D)") (class "Default")
      (node (ref "IC2") (pin "17") (pinfunction "7D_17") (pintype "input"))
      (node (ref "SV33") (pin "33") (pinfunction "33_33") (pintype "passive"))
      (node (ref "SV33") (pin "34") (pinfunction "34_34") (pintype "passive"))
      (node (ref "SV34") (pin "33") (pinfunction "33_33") (pintype "passive"))
      (node (ref "SV34") (pin "34") (pinfunction "34_34") (pintype "passive"))
    )
    (net (code "15") (name "Net-(IC2A-7Q)") (class "Default")
      (node (ref "IC2") (pin "16") (pinfunction "7Q_16") (pintype "tri_state"))
      (node (ref "SV33") (pin "31") (pinfunction "31_31") (pintype "passive"))
      (node (ref "SV33") (pin "32") (pinfunction "32_32") (pintype "passive"))
      (node (ref "SV34") (pin "31") (pinfunction "31_31") (pintype "passive"))
      (node (ref "SV34") (pin "32") (pinfunction "32_32") (pintype "passive"))
    )
    (net (code "16") (name "Net-(IC2A-8D)") (class "Default")
      (node (ref "IC2") (pin "18") (pinfunction "8D_18") (pintype "input"))
      (node (ref "SV33") (pin "35") (pinfunction "35_35") (pintype "passive"))
      (node (ref "SV33") (pin "36") (pinfunction "36_36") (pintype "passive"))
      (node (ref "SV34") (pin "35") (pinfunction "35_35") (pintype "passive"))
      (node (ref "SV34") (pin "36") (pinfunction "36_36") (pintype "passive"))
    )
    (net (code "17") (name "Net-(IC2A-8Q)") (class "Default")
      (node (ref "IC2") (pin "19") (pinfunction "8Q_19") (pintype "tri_state"))
      (node (ref "SV33") (pin "37") (pinfunction "37_37") (pintype "passive"))
      (node (ref "SV33") (pin "38") (pinfunction "38_38") (pintype "passive"))
      (node (ref "SV34") (pin "37") (pinfunction "37_37") (pintype "passive"))
      (node (ref "SV34") (pin "38") (pinfunction "38_38") (pintype "passive"))
    )
    (net (code "18") (name "Net-(IC2A-ENC)") (class "Default")
      (node (ref "IC2") (pin "11") (pinfunction "ENC_11") (pintype "input"))
      (node (ref "SV33") (pin "21") (pinfunction "21_21") (pintype "passive"))
      (node (ref "SV33") (pin "22") (pinfunction "22_22") (pintype "passive"))
      (node (ref "SV34") (pin "21") (pinfunction "21_21") (pintype "passive"))
      (node (ref "SV34") (pin "22") (pinfunction "22_22") (pintype "passive"))
      (node (ref "SV42") (pin "6") (pinfunction "6_6") (pintype "passive"))
    )
    (net (code "19") (name "Net-(IC2A-OC)") (class "Default")
      (node (ref "IC2") (pin "1") (pinfunction "OC_1") (pintype "input"))
      (node (ref "SV26") (pin "39") (pinfunction "39_39") (pintype "passive"))
      (node (ref "SV26") (pin "40") (pinfunction "40_40") (pintype "passive"))
      (node (ref "SV6") (pin "39") (pinfunction "39_39") (pintype "passive"))
      (node (ref "SV6") (pin "40") (pinfunction "40_40") (pintype "passive"))
    )
    (net (code "20") (name "Net-(IC2B-GND)") (class "Default")
      (node (ref "IC2") (pin "10") (pinfunction "GND_10") (pintype "power_in"))
      (node (ref "SV26") (pin "21") (pinfunction "21_21") (pintype "passive"))
      (node (ref "SV26") (pin "22") (pinfunction "22_22") (pintype "passive"))
      (node (ref "SV35") (pin "6") (pinfunction "6_6") (pintype "passive"))
      (node (ref "SV6") (pin "21") (pinfunction "21_21") (pintype "passive"))
      (node (ref "SV6") (pin "22") (pinfunction "22_22") (pintype "passive"))
    )
    (net (code "21") (name "Net-(IC2B-VCC)") (class "Default")
      (node (ref "IC2") (pin "20") (pinfunction "VCC_20") (pintype "power_in"))
      (node (ref "SV33") (pin "39") (pinfunction "39_39") (pintype "passive"))
      (node (ref "SV33") (pin "40") (pinfunction "40_40") (pintype "passive"))
      (node (ref "SV34") (pin "39") (pinfunction "39_39") (pintype "passive"))
      (node (ref "SV34") (pin "40") (pinfunction "40_40") (pintype "passive"))
    )
    (net (code "22") (name "Net-(IC3A-1D)") (class "Default")
      (node (ref "IC3") (pin "3") (pinfunction "1D_3") (pintype "input"))
      (node (ref "SV26") (pin "15") (pinfunction "15_15") (pintype "passive"))
      (node (ref "SV26") (pin "16") (pinfunction "16_16") (pintype "passive"))
      (node (ref "SV35") (pin "3") (pinfunction "3_3") (pintype "passive"))
      (node (ref "SV6") (pin "15") (pinfunction "15_15") (pintype "passive"))
      (node (ref "SV6") (pin "16") (pinfunction "16_16") (pintype "passive"))
    )
    (net (code "23") (name "Net-(IC3A-1Q)") (class "Default")
      (node (ref "IC3") (pin "2") (pinfunction "1Q_2") (pintype "tri_state"))
      (node (ref "SV26") (pin "17") (pinfunction "17_17") (pintype "passive"))
      (node (ref "SV26") (pin "18") (pinfunction "18_18") (pintype "passive"))
      (node (ref "SV35") (pin "4") (pinfunction "4_4") (pintype "passive"))
      (node (ref "SV6") (pin "17") (pinfunction "17_17") (pintype "passive"))
      (node (ref "SV6") (pin "18") (pinfunction "18_18") (pintype "passive"))
    )
    (net (code "24") (name "Net-(IC3A-2D)") (class "Default")
      (node (ref "IC3") (pin "4") (pinfunction "2D_4") (pintype "input"))
      (node (ref "SV26") (pin "13") (pinfunction "13_13") (pintype "passive"))
      (node (ref "SV26") (pin "14") (pinfunction "14_14") (pintype "passive"))
      (node (ref "SV35") (pin "2") (pinfunction "2_2") (pintype "passive"))
      (node (ref "SV6") (pin "13") (pinfunction "13_13") (pintype "passive"))
      (node (ref "SV6") (pin "14") (pinfunction "14_14") (pintype "passive"))
    )
    (net (code "25") (name "Net-(IC3A-2Q)") (class "Default")
      (node (ref "IC3") (pin "5") (pinfunction "2Q_5") (pintype "tri_state"))
      (node (ref "SV26") (pin "11") (pinfunction "11_11") (pintype "passive"))
      (node (ref "SV26") (pin "12") (pinfunction "12_12") (pintype "passive"))
      (node (ref "SV35") (pin "1") (pinfunction "1_1") (pintype "passive"))
      (node (ref "SV6") (pin "11") (pinfunction "11_11") (pintype "passive"))
      (node (ref "SV6") (pin "12") (pinfunction "12_12") (pintype "passive"))
    )
    (net (code "26") (name "Net-(IC3A-3D)") (class "Default")
      (node (ref "IC3") (pin "7") (pinfunction "3D_7") (pintype "input"))
      (node (ref "SV26") (pin "7") (pinfunction "7_7") (pintype "passive"))
      (node (ref "SV26") (pin "8") (pinfunction "8_8") (pintype "passive"))
      (node (ref "SV6") (pin "7") (pinfunction "7_7") (pintype "passive"))
      (node (ref "SV6") (pin "8") (pinfunction "8_8") (pintype "passive"))
    )
    (net (code "27") (name "Net-(IC3A-3Q)") (class "Default")
      (node (ref "IC3") (pin "6") (pinfunction "3Q_6") (pintype "tri_state"))
      (node (ref "SV26") (pin "10") (pinfunction "10_10") (pintype "passive"))
      (node (ref "SV26") (pin "9") (pinfunction "9_9") (pintype "passive"))
      (node (ref "SV6") (pin "10") (pinfunction "10_10") (pintype "passive"))
      (node (ref "SV6") (pin "9") (pinfunction "9_9") (pintype "passive"))
    )
    (net (code "28") (name "Net-(IC3A-4D)") (class "Default")
      (node (ref "IC3") (pin "8") (pinfunction "4D_8") (pintype "input"))
      (node (ref "SV26") (pin "5") (pinfunction "5_5") (pintype "passive"))
      (node (ref "SV26") (pin "6") (pinfunction "6_6") (pintype "passive"))
      (node (ref "SV6") (pin "5") (pinfunction "5_5") (pintype "passive"))
      (node (ref "SV6") (pin "6") (pinfunction "6_6") (pintype "passive"))
    )
    (net (code "29") (name "Net-(IC3A-4Q)") (class "Default")
      (node (ref "IC3") (pin "9") (pinfunction "4Q_9") (pintype "tri_state"))
      (node (ref "SV26") (pin "3") (pinfunction "3_3") (pintype "passive"))
      (node (ref "SV26") (pin "4") (pinfunction "4_4") (pintype "passive"))
      (node (ref "SV6") (pin "3") (pinfunction "3_3") (pintype "passive"))
      (node (ref "SV6") (pin "4") (pinfunction "4_4") (pintype "passive"))
    )
    (net (code "30") (name "Net-(IC3A-5D)") (class "Default")
      (node (ref "IC3") (pin "13") (pinfunction "5D_13") (pintype "input"))
      (node (ref "SV33") (pin "5") (pinfunction "5_5") (pintype "passive"))
      (node (ref "SV33") (pin "6") (pinfunction "6_6") (pintype "passive"))
      (node (ref "SV34") (pin "5") (pinfunction "5_5") (pintype "passive"))
      (node (ref "SV34") (pin "6") (pinfunction "6_6") (pintype "passive"))
    )
    (net (code "31") (name "Net-(IC3A-5Q)") (class "Default")
      (node (ref "IC3") (pin "12") (pinfunction "5Q_12") (pintype "tri_state"))
      (node (ref "SV33") (pin "3") (pinfunction "3_3") (pintype "passive"))
      (node (ref "SV33") (pin "4") (pinfunction "4_4") (pintype "passive"))
      (node (ref "SV34") (pin "3") (pinfunction "3_3") (pintype "passive"))
      (node (ref "SV34") (pin "4") (pinfunction "4_4") (pintype "passive"))
    )
    (net (code "32") (name "Net-(IC3A-6D)") (class "Default")
      (node (ref "IC3") (pin "14") (pinfunction "6D_14") (pintype "input"))
      (node (ref "SV33") (pin "7") (pinfunction "7_7") (pintype "passive"))
      (node (ref "SV33") (pin "8") (pinfunction "8_8") (pintype "passive"))
      (node (ref "SV34") (pin "7") (pinfunction "7_7") (pintype "passive"))
      (node (ref "SV34") (pin "8") (pinfunction "8_8") (pintype "passive"))
    )
    (net (code "33") (name "Net-(IC3A-6Q)") (class "Default")
      (node (ref "IC3") (pin "15") (pinfunction "6Q_15") (pintype "tri_state"))
      (node (ref "SV33") (pin "10") (pinfunction "10_10") (pintype "passive"))
      (node (ref "SV33") (pin "9") (pinfunction "9_9") (pintype "passive"))
      (node (ref "SV34") (pin "10") (pinfunction "10_10") (pintype "passive"))
      (node (ref "SV34") (pin "9") (pinfunction "9_9") (pintype "passive"))
    )
    (net (code "34") (name "Net-(IC3A-7D)") (class "Default")
      (node (ref "IC3") (pin "17") (pinfunction "7D_17") (pintype "input"))
      (node (ref "SV33") (pin "13") (pinfunction "13_13") (pintype "passive"))
      (node (ref "SV33") (pin "14") (pinfunction "14_14") (pintype "passive"))
      (node (ref "SV34") (pin "13") (pinfunction "13_13") (pintype "passive"))
      (node (ref "SV34") (pin "14") (pinfunction "14_14") (pintype "passive"))
      (node (ref "SV42") (pin "2") (pinfunction "2_2") (pintype "passive"))
    )
    (net (code "35") (name "Net-(IC3A-7Q)") (class "Default")
      (node (ref "IC3") (pin "16") (pinfunction "7Q_16") (pintype "tri_state"))
      (node (ref "SV33") (pin "11") (pinfunction "11_11") (pintype "passive"))
      (node (ref "SV33") (pin "12") (pinfunction "12_12") (pintype "passive"))
      (node (ref "SV34") (pin "11") (pinfunction "11_11") (pintype "passive"))
      (node (ref "SV34") (pin "12") (pinfunction "12_12") (pintype "passive"))
      (node (ref "SV42") (pin "1") (pinfunction "1_1") (pintype "passive"))
    )
    (net (code "36") (name "Net-(IC3A-8D)") (class "Default")
      (node (ref "IC3") (pin "18") (pinfunction "8D_18") (pintype "input"))
      (node (ref "SV33") (pin "15") (pinfunction "15_15") (pintype "passive"))
      (node (ref "SV33") (pin "16") (pinfunction "16_16") (pintype "passive"))
      (node (ref "SV34") (pin "15") (pinfunction "15_15") (pintype "passive"))
      (node (ref "SV34") (pin "16") (pinfunction "16_16") (pintype "passive"))
      (node (ref "SV42") (pin "3") (pinfunction "3_3") (pintype "passive"))
    )
    (net (code "37") (name "Net-(IC3A-8Q)") (class "Default")
      (node (ref "IC3") (pin "19") (pinfunction "8Q_19") (pintype "tri_state"))
      (node (ref "SV33") (pin "17") (pinfunction "17_17") (pintype "passive"))
      (node (ref "SV33") (pin "18") (pinfunction "18_18") (pintype "passive"))
      (node (ref "SV34") (pin "17") (pinfunction "17_17") (pintype "passive"))
      (node (ref "SV34") (pin "18") (pinfunction "18_18") (pintype "passive"))
      (node (ref "SV42") (pin "4") (pinfunction "4_4") (pintype "passive"))
    )
    (net (code "38") (name "Net-(IC3A-ENC)") (class "Default")
      (node (ref "IC3") (pin "11") (pinfunction "ENC_11") (pintype "input"))
      (node (ref "SV33") (pin "1") (pinfunction "1_1") (pintype "passive"))
      (node (ref "SV33") (pin "2") (pinfunction "2_2") (pintype "passive"))
      (node (ref "SV34") (pin "1") (pinfunction "1_1") (pintype "passive"))
      (node (ref "SV34") (pin "2") (pinfunction "2_2") (pintype "passive"))
    )
    (net (code "39") (name "Net-(IC3A-OC)") (class "Default")
      (node (ref "IC3") (pin "1") (pinfunction "OC_1") (pintype "input"))
      (node (ref "SV26") (pin "19") (pinfunction "19_19") (pintype "passive"))
      (node (ref "SV26") (pin "20") (pinfunction "20_20") (pintype "passive"))
      (node (ref "SV35") (pin "5") (pinfunction "5_5") (pintype "passive"))
      (node (ref "SV6") (pin "19") (pinfunction "19_19") (pintype "passive"))
      (node (ref "SV6") (pin "20") (pinfunction "20_20") (pintype "passive"))
    )
    (net (code "40") (name "Net-(IC3B-GND)") (class "Default")
      (node (ref "IC3") (pin "10") (pinfunction "GND_10") (pintype "power_in"))
      (node (ref "SV26") (pin "1") (pinfunction "1_1") (pintype "passive"))
      (node (ref "SV26") (pin "2") (pinfunction "2_2") (pintype "passive"))
      (node (ref "SV6") (pin "1") (pinfunction "1_1") (pintype "passive"))
      (node (ref "SV6") (pin "2") (pinfunction "2_2") (pintype "passive"))
    )
    (net (code "41") (name "Net-(IC3B-VCC)") (class "Default")
      (node (ref "IC3") (pin "20") (pinfunction "VCC_20") (pintype "power_in"))
      (node (ref "SV33") (pin "19") (pinfunction "19_19") (pintype "passive"))
      (node (ref "SV33") (pin "20") (pinfunction "20_20") (pintype "passive"))
      (node (ref "SV34") (pin "19") (pinfunction "19_19") (pintype "passive"))
      (node (ref "SV34") (pin "20") (pinfunction "20_20") (pintype "passive"))
      (node (ref "SV42") (pin "5") (pinfunction "5_5") (pintype "passive"))
    )
    (net (code "42") (name "Net-(IC4A-1D)") (class "Default")
      (node (ref "IC4") (pin "3") (pinfunction "1D_3") (pintype "input"))
      (node (ref "SV57") (pin "35") (pinfunction "35_35") (pintype "passive"))
      (node (ref "SV57") (pin "36") (pinfunction "36_36") (pintype "passive"))
      (node (ref "SV58") (pin "35") (pinfunction "35_35") (pintype "passive"))
      (node (ref "SV58") (pin "36") (pinfunction "36_36") (pintype "passive"))
    )
    (net (code "43") (name "Net-(IC4A-1Q)") (class "Default")
      (node (ref "IC4") (pin "2") (pinfunction "1Q_2") (pintype "tri_state"))
      (node (ref "SV57") (pin "37") (pinfunction "37_37") (pintype "passive"))
      (node (ref "SV57") (pin "38") (pinfunction "38_38") (pintype "passive"))
      (node (ref "SV58") (pin "37") (pinfunction "37_37") (pintype "passive"))
      (node (ref "SV58") (pin "38") (pinfunction "38_38") (pintype "passive"))
    )
    (net (code "44") (name "Net-(IC4A-2D)") (class "Default")
      (node (ref "IC4") (pin "4") (pinfunction "2D_4") (pintype "input"))
      (node (ref "SV57") (pin "33") (pinfunction "33_33") (pintype "passive"))
      (node (ref "SV57") (pin "34") (pinfunction "34_34") (pintype "passive"))
      (node (ref "SV58") (pin "33") (pinfunction "33_33") (pintype "passive"))
      (node (ref "SV58") (pin "34") (pinfunction "34_34") (pintype "passive"))
    )
    (net (code "45") (name "Net-(IC4A-2Q)") (class "Default")
      (node (ref "IC4") (pin "5") (pinfunction "2Q_5") (pintype "tri_state"))
      (node (ref "SV57") (pin "31") (pinfunction "31_31") (pintype "passive"))
      (node (ref "SV57") (pin "32") (pinfunction "32_32") (pintype "passive"))
      (node (ref "SV58") (pin "31") (pinfunction "31_31") (pintype "passive"))
      (node (ref "SV58") (pin "32") (pinfunction "32_32") (pintype "passive"))
    )
    (net (code "46") (name "Net-(IC4A-3D)") (class "Default")
      (node (ref "IC4") (pin "7") (pinfunction "3D_7") (pintype "input"))
      (node (ref "SV57") (pin "27") (pinfunction "27_27") (pintype "passive"))
      (node (ref "SV57") (pin "28") (pinfunction "28_28") (pintype "passive"))
      (node (ref "SV58") (pin "27") (pinfunction "27_27") (pintype "passive"))
      (node (ref "SV58") (pin "28") (pinfunction "28_28") (pintype "passive"))
      (node (ref "SV61") (pin "9") (pinfunction "9_9") (pintype "passive"))
    )
    (net (code "47") (name "Net-(IC4A-3Q)") (class "Default")
      (node (ref "IC4") (pin "6") (pinfunction "3Q_6") (pintype "tri_state"))
      (node (ref "SV57") (pin "29") (pinfunction "29_29") (pintype "passive"))
      (node (ref "SV57") (pin "30") (pinfunction "30_30") (pintype "passive"))
      (node (ref "SV58") (pin "29") (pinfunction "29_29") (pintype "passive"))
      (node (ref "SV58") (pin "30") (pinfunction "30_30") (pintype "passive"))
      (node (ref "SV61") (pin "10") (pinfunction "10_10") (pintype "passive"))
    )
    (net (code "48") (name "Net-(IC4A-4D)") (class "Default")
      (node (ref "IC4") (pin "8") (pinfunction "4D_8") (pintype "input"))
      (node (ref "SV57") (pin "25") (pinfunction "25_25") (pintype "passive"))
      (node (ref "SV57") (pin "26") (pinfunction "26_26") (pintype "passive"))
      (node (ref "SV58") (pin "25") (pinfunction "25_25") (pintype "passive"))
      (node (ref "SV58") (pin "26") (pinfunction "26_26") (pintype "passive"))
      (node (ref "SV61") (pin "8") (pinfunction "8_8") (pintype "passive"))
    )
    (net (code "49") (name "Net-(IC4A-4Q)") (class "Default")
      (node (ref "IC4") (pin "9") (pinfunction "4Q_9") (pintype "tri_state"))
      (node (ref "SV57") (pin "23") (pinfunction "23_23") (pintype "passive"))
      (node (ref "SV57") (pin "24") (pinfunction "24_24") (pintype "passive"))
      (node (ref "SV58") (pin "23") (pinfunction "23_23") (pintype "passive"))
      (node (ref "SV58") (pin "24") (pinfunction "24_24") (pintype "passive"))
      (node (ref "SV61") (pin "7") (pinfunction "7_7") (pintype "passive"))
    )
    (net (code "50") (name "Net-(IC4A-5D)") (class "Default")
      (node (ref "IC4") (pin "13") (pinfunction "5D_13") (pintype "input"))
      (node (ref "SV59") (pin "25") (pinfunction "25_25") (pintype "passive"))
      (node (ref "SV59") (pin "26") (pinfunction "26_26") (pintype "passive"))
      (node (ref "SV60") (pin "25") (pinfunction "25_25") (pintype "passive"))
      (node (ref "SV60") (pin "26") (pinfunction "26_26") (pintype "passive"))
      (node (ref "SV62") (pin "8") (pinfunction "8_8") (pintype "passive"))
    )
    (net (code "51") (name "Net-(IC4A-5Q)") (class "Default")
      (node (ref "IC4") (pin "12") (pinfunction "5Q_12") (pintype "tri_state"))
      (node (ref "SV59") (pin "23") (pinfunction "23_23") (pintype "passive"))
      (node (ref "SV59") (pin "24") (pinfunction "24_24") (pintype "passive"))
      (node (ref "SV60") (pin "23") (pinfunction "23_23") (pintype "passive"))
      (node (ref "SV60") (pin "24") (pinfunction "24_24") (pintype "passive"))
      (node (ref "SV62") (pin "7") (pinfunction "7_7") (pintype "passive"))
    )
    (net (code "52") (name "Net-(IC4A-6D)") (class "Default")
      (node (ref "IC4") (pin "14") (pinfunction "6D_14") (pintype "input"))
      (node (ref "SV59") (pin "27") (pinfunction "27_27") (pintype "passive"))
      (node (ref "SV59") (pin "28") (pinfunction "28_28") (pintype "passive"))
      (node (ref "SV60") (pin "27") (pinfunction "27_27") (pintype "passive"))
      (node (ref "SV60") (pin "28") (pinfunction "28_28") (pintype "passive"))
      (node (ref "SV62") (pin "9") (pinfunction "9_9") (pintype "passive"))
    )
    (net (code "53") (name "Net-(IC4A-6Q)") (class "Default")
      (node (ref "IC4") (pin "15") (pinfunction "6Q_15") (pintype "tri_state"))
      (node (ref "SV59") (pin "29") (pinfunction "29_29") (pintype "passive"))
      (node (ref "SV59") (pin "30") (pinfunction "30_30") (pintype "passive"))
      (node (ref "SV60") (pin "29") (pinfunction "29_29") (pintype "passive"))
      (node (ref "SV60") (pin "30") (pinfunction "30_30") (pintype "passive"))
      (node (ref "SV62") (pin "10") (pinfunction "10_10") (pintype "passive"))
    )
    (net (code "54") (name "Net-(IC4A-7D)") (class "Default")
      (node (ref "IC4") (pin "17") (pinfunction "7D_17") (pintype "input"))
      (node (ref "SV59") (pin "33") (pinfunction "33_33") (pintype "passive"))
      (node (ref "SV59") (pin "34") (pinfunction "34_34") (pintype "passive"))
      (node (ref "SV60") (pin "33") (pinfunction "33_33") (pintype "passive"))
      (node (ref "SV60") (pin "34") (pinfunction "34_34") (pintype "passive"))
    )
    (net (code "55") (name "Net-(IC4A-7Q)") (class "Default")
      (node (ref "IC4") (pin "16") (pinfunction "7Q_16") (pintype "tri_state"))
      (node (ref "SV59") (pin "31") (pinfunction "31_31") (pintype "passive"))
      (node (ref "SV59") (pin "32") (pinfunction "32_32") (pintype "passive"))
      (node (ref "SV60") (pin "31") (pinfunction "31_31") (pintype "passive"))
      (node (ref "SV60") (pin "32") (pinfunction "32_32") (pintype "passive"))
    )
    (net (code "56") (name "Net-(IC4A-8D)") (class "Default")
      (node (ref "IC4") (pin "18") (pinfunction "8D_18") (pintype "input"))
      (node (ref "SV59") (pin "35") (pinfunction "35_35") (pintype "passive"))
      (node (ref "SV59") (pin "36") (pinfunction "36_36") (pintype "passive"))
      (node (ref "SV60") (pin "35") (pinfunction "35_35") (pintype "passive"))
      (node (ref "SV60") (pin "36") (pinfunction "36_36") (pintype "passive"))
    )
    (net (code "57") (name "Net-(IC4A-8Q)") (class "Default")
      (node (ref "IC4") (pin "19") (pinfunction "8Q_19") (pintype "tri_state"))
      (node (ref "SV59") (pin "37") (pinfunction "37_37") (pintype "passive"))
      (node (ref "SV59") (pin "38") (pinfunction "38_38") (pintype "passive"))
      (node (ref "SV60") (pin "37") (pinfunction "37_37") (pintype "passive"))
      (node (ref "SV60") (pin "38") (pinfunction "38_38") (pintype "passive"))
    )
    (net (code "58") (name "Net-(IC4A-ENC)") (class "Default")
      (node (ref "IC4") (pin "11") (pinfunction "ENC_11") (pintype "input"))
      (node (ref "SV59") (pin "21") (pinfunction "21_21") (pintype "passive"))
      (node (ref "SV59") (pin "22") (pinfunction "22_22") (pintype "passive"))
      (node (ref "SV60") (pin "21") (pinfunction "21_21") (pintype "passive"))
      (node (ref "SV60") (pin "22") (pinfunction "22_22") (pintype "passive"))
      (node (ref "SV62") (pin "6") (pinfunction "6_6") (pintype "passive"))
    )
    (net (code "59") (name "Net-(IC4A-OC)") (class "Default")
      (node (ref "IC4") (pin "1") (pinfunction "OC_1") (pintype "input"))
      (node (ref "SV57") (pin "39") (pinfunction "39_39") (pintype "passive"))
      (node (ref "SV57") (pin "40") (pinfunction "40_40") (pintype "passive"))
      (node (ref "SV58") (pin "39") (pinfunction "39_39") (pintype "passive"))
      (node (ref "SV58") (pin "40") (pinfunction "40_40") (pintype "passive"))
    )
    (net (code "60") (name "Net-(IC4B-GND)") (class "Default")
      (node (ref "IC4") (pin "10") (pinfunction "GND_10") (pintype "power_in"))
      (node (ref "SV57") (pin "21") (pinfunction "21_21") (pintype "passive"))
      (node (ref "SV57") (pin "22") (pinfunction "22_22") (pintype "passive"))
      (node (ref "SV58") (pin "21") (pinfunction "21_21") (pintype "passive"))
      (node (ref "SV58") (pin "22") (pinfunction "22_22") (pintype "passive"))
      (node (ref "SV61") (pin "6") (pinfunction "6_6") (pintype "passive"))
    )
    (net (code "61") (name "Net-(IC4B-VCC)") (class "Default")
      (node (ref "IC4") (pin "20") (pinfunction "VCC_20") (pintype "power_in"))
      (node (ref "SV59") (pin "39") (pinfunction "39_39") (pintype "passive"))
      (node (ref "SV59") (pin "40") (pinfunction "40_40") (pintype "passive"))
      (node (ref "SV60") (pin "39") (pinfunction "39_39") (pintype "passive"))
      (node (ref "SV60") (pin "40") (pinfunction "40_40") (pintype "passive"))
    )
    (net (code "62") (name "Net-(IC6A-1D)") (class "Default")
      (node (ref "IC6") (pin "3") (pinfunction "1D_3") (pintype "input"))
      (node (ref "SV37") (pin "35") (pinfunction "35_35") (pintype "passive"))
      (node (ref "SV37") (pin "36") (pinfunction "36_36") (pintype "passive"))
      (node (ref "SV38") (pin "35") (pinfunction "35_35") (pintype "passive"))
      (node (ref "SV38") (pin "36") (pinfunction "36_36") (pintype "passive"))
    )
    (net (code "63") (name "Net-(IC6A-1Q)") (class "Default")
      (node (ref "IC6") (pin "2") (pinfunction "1Q_2") (pintype "tri_state"))
      (node (ref "SV37") (pin "37") (pinfunction "37_37") (pintype "passive"))
      (node (ref "SV37") (pin "38") (pinfunction "38_38") (pintype "passive"))
      (node (ref "SV38") (pin "37") (pinfunction "37_37") (pintype "passive"))
      (node (ref "SV38") (pin "38") (pinfunction "38_38") (pintype "passive"))
    )
    (net (code "64") (name "Net-(IC6A-2D)") (class "Default")
      (node (ref "IC6") (pin "4") (pinfunction "2D_4") (pintype "input"))
      (node (ref "SV37") (pin "33") (pinfunction "33_33") (pintype "passive"))
      (node (ref "SV37") (pin "34") (pinfunction "34_34") (pintype "passive"))
      (node (ref "SV38") (pin "33") (pinfunction "33_33") (pintype "passive"))
      (node (ref "SV38") (pin "34") (pinfunction "34_34") (pintype "passive"))
    )
    (net (code "65") (name "Net-(IC6A-2Q)") (class "Default")
      (node (ref "IC6") (pin "5") (pinfunction "2Q_5") (pintype "tri_state"))
      (node (ref "SV37") (pin "31") (pinfunction "31_31") (pintype "passive"))
      (node (ref "SV37") (pin "32") (pinfunction "32_32") (pintype "passive"))
      (node (ref "SV38") (pin "31") (pinfunction "31_31") (pintype "passive"))
      (node (ref "SV38") (pin "32") (pinfunction "32_32") (pintype "passive"))
    )
    (net (code "66") (name "Net-(IC6A-3D)") (class "Default")
      (node (ref "IC6") (pin "7") (pinfunction "3D_7") (pintype "input"))
      (node (ref "SV36") (pin "9") (pinfunction "9_9") (pintype "passive"))
      (node (ref "SV37") (pin "27") (pinfunction "27_27") (pintype "passive"))
      (node (ref "SV37") (pin "28") (pinfunction "28_28") (pintype "passive"))
      (node (ref "SV38") (pin "27") (pinfunction "27_27") (pintype "passive"))
      (node (ref "SV38") (pin "28") (pinfunction "28_28") (pintype "passive"))
    )
    (net (code "67") (name "Net-(IC6A-3Q)") (class "Default")
      (node (ref "IC6") (pin "6") (pinfunction "3Q_6") (pintype "tri_state"))
      (node (ref "SV36") (pin "10") (pinfunction "10_10") (pintype "passive"))
      (node (ref "SV37") (pin "29") (pinfunction "29_29") (pintype "passive"))
      (node (ref "SV37") (pin "30") (pinfunction "30_30") (pintype "passive"))
      (node (ref "SV38") (pin "29") (pinfunction "29_29") (pintype "passive"))
      (node (ref "SV38") (pin "30") (pinfunction "30_30") (pintype "passive"))
    )
    (net (code "68") (name "Net-(IC6A-4D)") (class "Default")
      (node (ref "IC6") (pin "8") (pinfunction "4D_8") (pintype "input"))
      (node (ref "SV36") (pin "8") (pinfunction "8_8") (pintype "passive"))
      (node (ref "SV37") (pin "25") (pinfunction "25_25") (pintype "passive"))
      (node (ref "SV37") (pin "26") (pinfunction "26_26") (pintype "passive"))
      (node (ref "SV38") (pin "25") (pinfunction "25_25") (pintype "passive"))
      (node (ref "SV38") (pin "26") (pinfunction "26_26") (pintype "passive"))
    )
    (net (code "69") (name "Net-(IC6A-4Q)") (class "Default")
      (node (ref "IC6") (pin "9") (pinfunction "4Q_9") (pintype "tri_state"))
      (node (ref "SV36") (pin "7") (pinfunction "7_7") (pintype "passive"))
      (node (ref "SV37") (pin "23") (pinfunction "23_23") (pintype "passive"))
      (node (ref "SV37") (pin "24") (pinfunction "24_24") (pintype "passive"))
      (node (ref "SV38") (pin "23") (pinfunction "23_23") (pintype "passive"))
      (node (ref "SV38") (pin "24") (pinfunction "24_24") (pintype "passive"))
    )
    (net (code "70") (name "Net-(IC6A-5D)") (class "Default")
      (node (ref "IC6") (pin "13") (pinfunction "5D_13") (pintype "input"))
      (node (ref "SV39") (pin "25") (pinfunction "25_25") (pintype "passive"))
      (node (ref "SV39") (pin "26") (pinfunction "26_26") (pintype "passive"))
      (node (ref "SV40") (pin "25") (pinfunction "25_25") (pintype "passive"))
      (node (ref "SV40") (pin "26") (pinfunction "26_26") (pintype "passive"))
      (node (ref "SV41") (pin "8") (pinfunction "8_8") (pintype "passive"))
    )
    (net (code "71") (name "Net-(IC6A-5Q)") (class "Default")
      (node (ref "IC6") (pin "12") (pinfunction "5Q_12") (pintype "tri_state"))
      (node (ref "SV39") (pin "23") (pinfunction "23_23") (pintype "passive"))
      (node (ref "SV39") (pin "24") (pinfunction "24_24") (pintype "passive"))
      (node (ref "SV40") (pin "23") (pinfunction "23_23") (pintype "passive"))
      (node (ref "SV40") (pin "24") (pinfunction "24_24") (pintype "passive"))
      (node (ref "SV41") (pin "7") (pinfunction "7_7") (pintype "passive"))
    )
    (net (code "72") (name "Net-(IC6A-6D)") (class "Default")
      (node (ref "IC6") (pin "14") (pinfunction "6D_14") (pintype "input"))
      (node (ref "SV39") (pin "27") (pinfunction "27_27") (pintype "passive"))
      (node (ref "SV39") (pin "28") (pinfunction "28_28") (pintype "passive"))
      (node (ref "SV40") (pin "27") (pinfunction "27_27") (pintype "passive"))
      (node (ref "SV40") (pin "28") (pinfunction "28_28") (pintype "passive"))
      (node (ref "SV41") (pin "9") (pinfunction "9_9") (pintype "passive"))
    )
    (net (code "73") (name "Net-(IC6A-6Q)") (class "Default")
      (node (ref "IC6") (pin "15") (pinfunction "6Q_15") (pintype "tri_state"))
      (node (ref "SV39") (pin "29") (pinfunction "29_29") (pintype "passive"))
      (node (ref "SV39") (pin "30") (pinfunction "30_30") (pintype "passive"))
      (node (ref "SV40") (pin "29") (pinfunction "29_29") (pintype "passive"))
      (node (ref "SV40") (pin "30") (pinfunction "30_30") (pintype "passive"))
      (node (ref "SV41") (pin "10") (pinfunction "10_10") (pintype "passive"))
    )
    (net (code "74") (name "Net-(IC6A-7D)") (class "Default")
      (node (ref "IC6") (pin "17") (pinfunction "7D_17") (pintype "input"))
      (node (ref "SV39") (pin "33") (pinfunction "33_33") (pintype "passive"))
      (node (ref "SV39") (pin "34") (pinfunction "34_34") (pintype "passive"))
      (node (ref "SV40") (pin "33") (pinfunction "33_33") (pintype "passive"))
      (node (ref "SV40") (pin "34") (pinfunction "34_34") (pintype "passive"))
    )
    (net (code "75") (name "Net-(IC6A-7Q)") (class "Default")
      (node (ref "IC6") (pin "16") (pinfunction "7Q_16") (pintype "tri_state"))
      (node (ref "SV39") (pin "31") (pinfunction "31_31") (pintype "passive"))
      (node (ref "SV39") (pin "32") (pinfunction "32_32") (pintype "passive"))
      (node (ref "SV40") (pin "31") (pinfunction "31_31") (pintype "passive"))
      (node (ref "SV40") (pin "32") (pinfunction "32_32") (pintype "passive"))
    )
    (net (code "76") (name "Net-(IC6A-8D)") (class "Default")
      (node (ref "IC6") (pin "18") (pinfunction "8D_18") (pintype "input"))
      (node (ref "SV39") (pin "35") (pinfunction "35_35") (pintype "passive"))
      (node (ref "SV39") (pin "36") (pinfunction "36_36") (pintype "passive"))
      (node (ref "SV40") (pin "35") (pinfunction "35_35") (pintype "passive"))
      (node (ref "SV40") (pin "36") (pinfunction "36_36") (pintype "passive"))
    )
    (net (code "77") (name "Net-(IC6A-8Q)") (class "Default")
      (node (ref "IC6") (pin "19") (pinfunction "8Q_19") (pintype "tri_state"))
      (node (ref "SV39") (pin "37") (pinfunction "37_37") (pintype "passive"))
      (node (ref "SV39") (pin "38") (pinfunction "38_38") (pintype "passive"))
      (node (ref "SV40") (pin "37") (pinfunction "37_37") (pintype "passive"))
      (node (ref "SV40") (pin "38") (pinfunction "38_38") (pintype "passive"))
    )
    (net (code "78") (name "Net-(IC6A-ENC)") (class "Default")
      (node (ref "IC6") (pin "11") (pinfunction "ENC_11") (pintype "input"))
      (node (ref "SV39") (pin "21") (pinfunction "21_21") (pintype "passive"))
      (node (ref "SV39") (pin "22") (pinfunction "22_22") (pintype "passive"))
      (node (ref "SV40") (pin "21") (pinfunction "21_21") (pintype "passive"))
      (node (ref "SV40") (pin "22") (pinfunction "22_22") (pintype "passive"))
      (node (ref "SV41") (pin "6") (pinfunction "6_6") (pintype "passive"))
    )
    (net (code "79") (name "Net-(IC6A-OC)") (class "Default")
      (node (ref "IC6") (pin "1") (pinfunction "OC_1") (pintype "input"))
      (node (ref "SV37") (pin "39") (pinfunction "39_39") (pintype "passive"))
      (node (ref "SV37") (pin "40") (pinfunction "40_40") (pintype "passive"))
      (node (ref "SV38") (pin "39") (pinfunction "39_39") (pintype "passive"))
      (node (ref "SV38") (pin "40") (pinfunction "40_40") (pintype "passive"))
    )
    (net (code "80") (name "Net-(IC6B-GND)") (class "Default")
      (node (ref "IC6") (pin "10") (pinfunction "GND_10") (pintype "power_in"))
      (node (ref "SV36") (pin "6") (pinfunction "6_6") (pintype "passive"))
      (node (ref "SV37") (pin "21") (pinfunction "21_21") (pintype "passive"))
      (node (ref "SV37") (pin "22") (pinfunction "22_22") (pintype "passive"))
      (node (ref "SV38") (pin "21") (pinfunction "21_21") (pintype "passive"))
      (node (ref "SV38") (pin "22") (pinfunction "22_22") (pintype "passive"))
    )
    (net (code "81") (name "Net-(IC6B-VCC)") (class "Default")
      (node (ref "IC6") (pin "20") (pinfunction "VCC_20") (pintype "power_in"))
      (node (ref "SV39") (pin "39") (pinfunction "39_39") (pintype "passive"))
      (node (ref "SV39") (pin "40") (pinfunction "40_40") (pintype "passive"))
      (node (ref "SV40") (pin "39") (pinfunction "39_39") (pintype "passive"))
      (node (ref "SV40") (pin "40") (pinfunction "40_40") (pintype "passive"))
    )
    (net (code "82") (name "Net-(IC7A-1D)") (class "Default")
      (node (ref "IC7") (pin "3") (pinfunction "1D_3") (pintype "input"))
      (node (ref "SV36") (pin "3") (pinfunction "3_3") (pintype "passive"))
      (node (ref "SV37") (pin "15") (pinfunction "15_15") (pintype "passive"))
      (node (ref "SV37") (pin "16") (pinfunction "16_16") (pintype "passive"))
      (node (ref "SV38") (pin "15") (pinfunction "15_15") (pintype "passive"))
      (node (ref "SV38") (pin "16") (pinfunction "16_16") (pintype "passive"))
    )
    (net (code "83") (name "Net-(IC7A-1Q)") (class "Default")
      (node (ref "IC7") (pin "2") (pinfunction "1Q_2") (pintype "tri_state"))
      (node (ref "SV36") (pin "4") (pinfunction "4_4") (pintype "passive"))
      (node (ref "SV37") (pin "17") (pinfunction "17_17") (pintype "passive"))
      (node (ref "SV37") (pin "18") (pinfunction "18_18") (pintype "passive"))
      (node (ref "SV38") (pin "17") (pinfunction "17_17") (pintype "passive"))
      (node (ref "SV38") (pin "18") (pinfunction "18_18") (pintype "passive"))
    )
    (net (code "84") (name "Net-(IC7A-2D)") (class "Default")
      (node (ref "IC7") (pin "4") (pinfunction "2D_4") (pintype "input"))
      (node (ref "SV36") (pin "2") (pinfunction "2_2") (pintype "passive"))
      (node (ref "SV37") (pin "13") (pinfunction "13_13") (pintype "passive"))
      (node (ref "SV37") (pin "14") (pinfunction "14_14") (pintype "passive"))
      (node (ref "SV38") (pin "13") (pinfunction "13_13") (pintype "passive"))
      (node (ref "SV38") (pin "14") (pinfunction "14_14") (pintype "passive"))
    )
    (net (code "85") (name "Net-(IC7A-2Q)") (class "Default")
      (node (ref "IC7") (pin "5") (pinfunction "2Q_5") (pintype "tri_state"))
      (node (ref "SV36") (pin "1") (pinfunction "1_1") (pintype "passive"))
      (node (ref "SV37") (pin "11") (pinfunction "11_11") (pintype "passive"))
      (node (ref "SV37") (pin "12") (pinfunction "12_12") (pintype "passive"))
      (node (ref "SV38") (pin "11") (pinfunction "11_11") (pintype "passive"))
      (node (ref "SV38") (pin "12") (pinfunction "12_12") (pintype "passive"))
    )
    (net (code "86") (name "Net-(IC7A-3D)") (class "Default")
      (node (ref "IC7") (pin "7") (pinfunction "3D_7") (pintype "input"))
      (node (ref "SV37") (pin "7") (pinfunction "7_7") (pintype "passive"))
      (node (ref "SV37") (pin "8") (pinfunction "8_8") (pintype "passive"))
      (node (ref "SV38") (pin "7") (pinfunction "7_7") (pintype "passive"))
      (node (ref "SV38") (pin "8") (pinfunction "8_8") (pintype "passive"))
    )
    (net (code "87") (name "Net-(IC7A-3Q)") (class "Default")
      (node (ref "IC7") (pin "6") (pinfunction "3Q_6") (pintype "tri_state"))
      (node (ref "SV37") (pin "10") (pinfunction "10_10") (pintype "passive"))
      (node (ref "SV37") (pin "9") (pinfunction "9_9") (pintype "passive"))
      (node (ref "SV38") (pin "10") (pinfunction "10_10") (pintype "passive"))
      (node (ref "SV38") (pin "9") (pinfunction "9_9") (pintype "passive"))
    )
    (net (code "88") (name "Net-(IC7A-4D)") (class "Default")
      (node (ref "IC7") (pin "8") (pinfunction "4D_8") (pintype "input"))
      (node (ref "SV37") (pin "5") (pinfunction "5_5") (pintype "passive"))
      (node (ref "SV37") (pin "6") (pinfunction "6_6") (pintype "passive"))
      (node (ref "SV38") (pin "5") (pinfunction "5_5") (pintype "passive"))
      (node (ref "SV38") (pin "6") (pinfunction "6_6") (pintype "passive"))
    )
    (net (code "89") (name "Net-(IC7A-4Q)") (class "Default")
      (node (ref "IC7") (pin "9") (pinfunction "4Q_9") (pintype "tri_state"))
      (node (ref "SV37") (pin "3") (pinfunction "3_3") (pintype "passive"))
      (node (ref "SV37") (pin "4") (pinfunction "4_4") (pintype "passive"))
      (node (ref "SV38") (pin "3") (pinfunction "3_3") (pintype "passive"))
      (node (ref "SV38") (pin "4") (pinfunction "4_4") (pintype "passive"))
    )
    (net (code "90") (name "Net-(IC7A-5D)") (class "Default")
      (node (ref "IC7") (pin "13") (pinfunction "5D_13") (pintype "input"))
      (node (ref "SV39") (pin "5") (pinfunction "5_5") (pintype "passive"))
      (node (ref "SV39") (pin "6") (pinfunction "6_6") (pintype "passive"))
      (node (ref "SV40") (pin "5") (pinfunction "5_5") (pintype "passive"))
      (node (ref "SV40") (pin "6") (pinfunction "6_6") (pintype "passive"))
    )
    (net (code "91") (name "Net-(IC7A-5Q)") (class "Default")
      (node (ref "IC7") (pin "12") (pinfunction "5Q_12") (pintype "tri_state"))
      (node (ref "SV39") (pin "3") (pinfunction "3_3") (pintype "passive"))
      (node (ref "SV39") (pin "4") (pinfunction "4_4") (pintype "passive"))
      (node (ref "SV40") (pin "3") (pinfunction "3_3") (pintype "passive"))
      (node (ref "SV40") (pin "4") (pinfunction "4_4") (pintype "passive"))
    )
    (net (code "92") (name "Net-(IC7A-6D)") (class "Default")
      (node (ref "IC7") (pin "14") (pinfunction "6D_14") (pintype "input"))
      (node (ref "SV39") (pin "7") (pinfunction "7_7") (pintype "passive"))
      (node (ref "SV39") (pin "8") (pinfunction "8_8") (pintype "passive"))
      (node (ref "SV40") (pin "7") (pinfunction "7_7") (pintype "passive"))
      (node (ref "SV40") (pin "8") (pinfunction "8_8") (pintype "passive"))
    )
    (net (code "93") (name "Net-(IC7A-6Q)") (class "Default")
      (node (ref "IC7") (pin "15") (pinfunction "6Q_15") (pintype "tri_state"))
      (node (ref "SV39") (pin "10") (pinfunction "10_10") (pintype "passive"))
      (node (ref "SV39") (pin "9") (pinfunction "9_9") (pintype "passive"))
      (node (ref "SV40") (pin "10") (pinfunction "10_10") (pintype "passive"))
      (node (ref "SV40") (pin "9") (pinfunction "9_9") (pintype "passive"))
    )
    (net (code "94") (name "Net-(IC7A-7D)") (class "Default")
      (node (ref "IC7") (pin "17") (pinfunction "7D_17") (pintype "input"))
      (node (ref "SV39") (pin "13") (pinfunction "13_13") (pintype "passive"))
      (node (ref "SV39") (pin "14") (pinfunction "14_14") (pintype "passive"))
      (node (ref "SV40") (pin "13") (pinfunction "13_13") (pintype "passive"))
      (node (ref "SV40") (pin "14") (pinfunction "14_14") (pintype "passive"))
      (node (ref "SV41") (pin "2") (pinfunction "2_2") (pintype "passive"))
    )
    (net (code "95") (name "Net-(IC7A-7Q)") (class "Default")
      (node (ref "IC7") (pin "16") (pinfunction "7Q_16") (pintype "tri_state"))
      (node (ref "SV39") (pin "11") (pinfunction "11_11") (pintype "passive"))
      (node (ref "SV39") (pin "12") (pinfunction "12_12") (pintype "passive"))
      (node (ref "SV40") (pin "11") (pinfunction "11_11") (pintype "passive"))
      (node (ref "SV40") (pin "12") (pinfunction "12_12") (pintype "passive"))
      (node (ref "SV41") (pin "1") (pinfunction "1_1") (pintype "passive"))
    )
    (net (code "96") (name "Net-(IC7A-8D)") (class "Default")
      (node (ref "IC7") (pin "18") (pinfunction "8D_18") (pintype "input"))
      (node (ref "SV39") (pin "15") (pinfunction "15_15") (pintype "passive"))
      (node (ref "SV39") (pin "16") (pinfunction "16_16") (pintype "passive"))
      (node (ref "SV40") (pin "15") (pinfunction "15_15") (pintype "passive"))
      (node (ref "SV40") (pin "16") (pinfunction "16_16") (pintype "passive"))
      (node (ref "SV41") (pin "3") (pinfunction "3_3") (pintype "passive"))
    )
    (net (code "97") (name "Net-(IC7A-8Q)") (class "Default")
      (node (ref "IC7") (pin "19") (pinfunction "8Q_19") (pintype "tri_state"))
      (node (ref "SV39") (pin "17") (pinfunction "17_17") (pintype "passive"))
      (node (ref "SV39") (pin "18") (pinfunction "18_18") (pintype "passive"))
      (node (ref "SV40") (pin "17") (pinfunction "17_17") (pintype "passive"))
      (node (ref "SV40") (pin "18") (pinfunction "18_18") (pintype "passive"))
      (node (ref "SV41") (pin "4") (pinfunction "4_4") (pintype "passive"))
    )
    (net (code "98") (name "Net-(IC7A-ENC)") (class "Default")
      (node (ref "IC7") (pin "11") (pinfunction "ENC_11") (pintype "input"))
      (node (ref "SV39") (pin "1") (pinfunction "1_1") (pintype "passive"))
      (node (ref "SV39") (pin "2") (pinfunction "2_2") (pintype "passive"))
      (node (ref "SV40") (pin "1") (pinfunction "1_1") (pintype "passive"))
      (node (ref "SV40") (pin "2") (pinfunction "2_2") (pintype "passive"))
    )
    (net (code "99") (name "Net-(IC7A-OC)") (class "Default")
      (node (ref "IC7") (pin "1") (pinfunction "OC_1") (pintype "input"))
      (node (ref "SV36") (pin "5") (pinfunction "5_5") (pintype "passive"))
      (node (ref "SV37") (pin "19") (pinfunction "19_19") (pintype "passive"))
      (node (ref "SV37") (pin "20") (pinfunction "20_20") (pintype "passive"))
      (node (ref "SV38") (pin "19") (pinfunction "19_19") (pintype "passive"))
      (node (ref "SV38") (pin "20") (pinfunction "20_20") (pintype "passive"))
    )
    (net (code "100") (name "Net-(IC7B-GND)") (class "Default")
      (node (ref "IC7") (pin "10") (pinfunction "GND_10") (pintype "power_in"))
      (node (ref "SV37") (pin "1") (pinfunction "1_1") (pintype "passive"))
      (node (ref "SV37") (pin "2") (pinfunction "2_2") (pintype "passive"))
      (node (ref "SV38") (pin "1") (pinfunction "1_1") (pintype "passive"))
      (node (ref "SV38") (pin "2") (pinfunction "2_2") (pintype "passive"))
    )
    (net (code "101") (name "Net-(IC7B-VCC)") (class "Default")
      (node (ref "IC7") (pin "20") (pinfunction "VCC_20") (pintype "power_in"))
      (node (ref "SV39") (pin "19") (pinfunction "19_19") (pintype "passive"))
      (node (ref "SV39") (pin "20") (pinfunction "20_20") (pintype "passive"))
      (node (ref "SV40") (pin "19") (pinfunction "19_19") (pintype "passive"))
      (node (ref "SV40") (pin "20") (pinfunction "20_20") (pintype "passive"))
      (node (ref "SV41") (pin "5") (pinfunction "5_5") (pintype "passive"))
    )
    (net (code "102") (name "Net-(IC11A-1D)") (class "Default")
      (node (ref "IC11") (pin "3") (pinfunction "1D_3") (pintype "input"))
      (node (ref "SV57") (pin "15") (pinfunction "15_15") (pintype "passive"))
      (node (ref "SV57") (pin "16") (pinfunction "16_16") (pintype "passive"))
      (node (ref "SV58") (pin "15") (pinfunction "15_15") (pintype "passive"))
      (node (ref "SV58") (pin "16") (pinfunction "16_16") (pintype "passive"))
      (node (ref "SV61") (pin "3") (pinfunction "3_3") (pintype "passive"))
    )
    (net (code "103") (name "Net-(IC11A-1Q)") (class "Default")
      (node (ref "IC11") (pin "2") (pinfunction "1Q_2") (pintype "tri_state"))
      (node (ref "SV57") (pin "17") (pinfunction "17_17") (pintype "passive"))
      (node (ref "SV57") (pin "18") (pinfunction "18_18") (pintype "passive"))
      (node (ref "SV58") (pin "17") (pinfunction "17_17") (pintype "passive"))
      (node (ref "SV58") (pin "18") (pinfunction "18_18") (pintype "passive"))
      (node (ref "SV61") (pin "4") (pinfunction "4_4") (pintype "passive"))
    )
    (net (code "104") (name "Net-(IC11A-2D)") (class "Default")
      (node (ref "IC11") (pin "4") (pinfunction "2D_4") (pintype "input"))
      (node (ref "SV57") (pin "13") (pinfunction "13_13") (pintype "passive"))
      (node (ref "SV57") (pin "14") (pinfunction "14_14") (pintype "passive"))
      (node (ref "SV58") (pin "13") (pinfunction "13_13") (pintype "passive"))
      (node (ref "SV58") (pin "14") (pinfunction "14_14") (pintype "passive"))
      (node (ref "SV61") (pin "2") (pinfunction "2_2") (pintype "passive"))
    )
    (net (code "105") (name "Net-(IC11A-2Q)") (class "Default")
      (node (ref "IC11") (pin "5") (pinfunction "2Q_5") (pintype "tri_state"))
      (node (ref "SV57") (pin "11") (pinfunction "11_11") (pintype "passive"))
      (node (ref "SV57") (pin "12") (pinfunction "12_12") (pintype "passive"))
      (node (ref "SV58") (pin "11") (pinfunction "11_11") (pintype "passive"))
      (node (ref "SV58") (pin "12") (pinfunction "12_12") (pintype "passive"))
      (node (ref "SV61") (pin "1") (pinfunction "1_1") (pintype "passive"))
    )
    (net (code "106") (name "Net-(IC11A-3D)") (class "Default")
      (node (ref "IC11") (pin "7") (pinfunction "3D_7") (pintype "input"))
      (node (ref "SV57") (pin "7") (pinfunction "7_7") (pintype "passive"))
      (node (ref "SV57") (pin "8") (pinfunction "8_8") (pintype "passive"))
      (node (ref "SV58") (pin "7") (pinfunction "7_7") (pintype "passive"))
      (node (ref "SV58") (pin "8") (pinfunction "8_8") (pintype "passive"))
    )
    (net (code "107") (name "Net-(IC11A-3Q)") (class "Default")
      (node (ref "IC11") (pin "6") (pinfunction "3Q_6") (pintype "tri_state"))
      (node (ref "SV57") (pin "10") (pinfunction "10_10") (pintype "passive"))
      (node (ref "SV57") (pin "9") (pinfunction "9_9") (pintype "passive"))
      (node (ref "SV58") (pin "10") (pinfunction "10_10") (pintype "passive"))
      (node (ref "SV58") (pin "9") (pinfunction "9_9") (pintype "passive"))
    )
    (net (code "108") (name "Net-(IC11A-4D)") (class "Default")
      (node (ref "IC11") (pin "8") (pinfunction "4D_8") (pintype "input"))
      (node (ref "SV57") (pin "5") (pinfunction "5_5") (pintype "passive"))
      (node (ref "SV57") (pin "6") (pinfunction "6_6") (pintype "passive"))
      (node (ref "SV58") (pin "5") (pinfunction "5_5") (pintype "passive"))
      (node (ref "SV58") (pin "6") (pinfunction "6_6") (pintype "passive"))
    )
    (net (code "109") (name "Net-(IC11A-4Q)") (class "Default")
      (node (ref "IC11") (pin "9") (pinfunction "4Q_9") (pintype "tri_state"))
      (node (ref "SV57") (pin "3") (pinfunction "3_3") (pintype "passive"))
      (node (ref "SV57") (pin "4") (pinfunction "4_4") (pintype "passive"))
      (node (ref "SV58") (pin "3") (pinfunction "3_3") (pintype "passive"))
      (node (ref "SV58") (pin "4") (pinfunction "4_4") (pintype "passive"))
    )
    (net (code "110") (name "Net-(IC11A-5D)") (class "Default")
      (node (ref "IC11") (pin "13") (pinfunction "5D_13") (pintype "input"))
      (node (ref "SV59") (pin "5") (pinfunction "5_5") (pintype "passive"))
      (node (ref "SV59") (pin "6") (pinfunction "6_6") (pintype "passive"))
      (node (ref "SV60") (pin "5") (pinfunction "5_5") (pintype "passive"))
      (node (ref "SV60") (pin "6") (pinfunction "6_6") (pintype "passive"))
    )
    (net (code "111") (name "Net-(IC11A-5Q)") (class "Default")
      (node (ref "IC11") (pin "12") (pinfunction "5Q_12") (pintype "tri_state"))
      (node (ref "SV59") (pin "3") (pinfunction "3_3") (pintype "passive"))
      (node (ref "SV59") (pin "4") (pinfunction "4_4") (pintype "passive"))
      (node (ref "SV60") (pin "3") (pinfunction "3_3") (pintype "passive"))
      (node (ref "SV60") (pin "4") (pinfunction "4_4") (pintype "passive"))
    )
    (net (code "112") (name "Net-(IC11A-6D)") (class "Default")
      (node (ref "IC11") (pin "14") (pinfunction "6D_14") (pintype "input"))
      (node (ref "SV59") (pin "7") (pinfunction "7_7") (pintype "passive"))
      (node (ref "SV59") (pin "8") (pinfunction "8_8") (pintype "passive"))
      (node (ref "SV60") (pin "7") (pinfunction "7_7") (pintype "passive"))
      (node (ref "SV60") (pin "8") (pinfunction "8_8") (pintype "passive"))
    )
    (net (code "113") (name "Net-(IC11A-6Q)") (class "Default")
      (node (ref "IC11") (pin "15") (pinfunction "6Q_15") (pintype "tri_state"))
      (node (ref "SV59") (pin "10") (pinfunction "10_10") (pintype "passive"))
      (node (ref "SV59") (pin "9") (pinfunction "9_9") (pintype "passive"))
      (node (ref "SV60") (pin "10") (pinfunction "10_10") (pintype "passive"))
      (node (ref "SV60") (pin "9") (pinfunction "9_9") (pintype "passive"))
    )
    (net (code "114") (name "Net-(IC11A-7D)") (class "Default")
      (node (ref "IC11") (pin "17") (pinfunction "7D_17") (pintype "input"))
      (node (ref "SV59") (pin "13") (pinfunction "13_13") (pintype "passive"))
      (node (ref "SV59") (pin "14") (pinfunction "14_14") (pintype "passive"))
      (node (ref "SV60") (pin "13") (pinfunction "13_13") (pintype "passive"))
      (node (ref "SV60") (pin "14") (pinfunction "14_14") (pintype "passive"))
      (node (ref "SV62") (pin "2") (pinfunction "2_2") (pintype "passive"))
    )
    (net (code "115") (name "Net-(IC11A-7Q)") (class "Default")
      (node (ref "IC11") (pin "16") (pinfunction "7Q_16") (pintype "tri_state"))
      (node (ref "SV59") (pin "11") (pinfunction "11_11") (pintype "passive"))
      (node (ref "SV59") (pin "12") (pinfunction "12_12") (pintype "passive"))
      (node (ref "SV60") (pin "11") (pinfunction "11_11") (pintype "passive"))
      (node (ref "SV60") (pin "12") (pinfunction "12_12") (pintype "passive"))
      (node (ref "SV62") (pin "1") (pinfunction "1_1") (pintype "passive"))
    )
    (net (code "116") (name "Net-(IC11A-8D)") (class "Default")
      (node (ref "IC11") (pin "18") (pinfunction "8D_18") (pintype "input"))
      (node (ref "SV59") (pin "15") (pinfunction "15_15") (pintype "passive"))
      (node (ref "SV59") (pin "16") (pinfunction "16_16") (pintype "passive"))
      (node (ref "SV60") (pin "15") (pinfunction "15_15") (pintype "passive"))
      (node (ref "SV60") (pin "16") (pinfunction "16_16") (pintype "passive"))
      (node (ref "SV62") (pin "3") (pinfunction "3_3") (pintype "passive"))
    )
    (net (code "117") (name "Net-(IC11A-8Q)") (class "Default")
      (node (ref "IC11") (pin "19") (pinfunction "8Q_19") (pintype "tri_state"))
      (node (ref "SV59") (pin "17") (pinfunction "17_17") (pintype "passive"))
      (node (ref "SV59") (pin "18") (pinfunction "18_18") (pintype "passive"))
      (node (ref "SV60") (pin "17") (pinfunction "17_17") (pintype "passive"))
      (node (ref "SV60") (pin "18") (pinfunction "18_18") (pintype "passive"))
      (node (ref "SV62") (pin "4") (pinfunction "4_4") (pintype "passive"))
    )
    (net (code "118") (name "Net-(IC11A-ENC)") (class "Default")
      (node (ref "IC11") (pin "11") (pinfunction "ENC_11") (pintype "input"))
      (node (ref "SV59") (pin "1") (pinfunction "1_1") (pintype "passive"))
      (node (ref "SV59") (pin "2") (pinfunction "2_2") (pintype "passive"))
      (node (ref "SV60") (pin "1") (pinfunction "1_1") (pintype "passive"))
      (node (ref "SV60") (pin "2") (pinfunction "2_2") (pintype "passive"))
    )
    (net (code "119") (name "Net-(IC11A-OC)") (class "Default")
      (node (ref "IC11") (pin "1") (pinfunction "OC_1") (pintype "input"))
      (node (ref "SV57") (pin "19") (pinfunction "19_19") (pintype "passive"))
      (node (ref "SV57") (pin "20") (pinfunction "20_20") (pintype "passive"))
      (node (ref "SV58") (pin "19") (pinfunction "19_19") (pintype "passive"))
      (node (ref "SV58") (pin "20") (pinfunction "20_20") (pintype "passive"))
      (node (ref "SV61") (pin "5") (pinfunction "5_5") (pintype "passive"))
    )
    (net (code "120") (name "Net-(IC11B-GND)") (class "Default")
      (node (ref "IC11") (pin "10") (pinfunction "GND_10") (pintype "power_in"))
      (node (ref "SV57") (pin "1") (pinfunction "1_1") (pintype "passive"))
      (node (ref "SV57") (pin "2") (pinfunction "2_2") (pintype "passive"))
      (node (ref "SV58") (pin "1") (pinfunction "1_1") (pintype "passive"))
      (node (ref "SV58") (pin "2") (pinfunction "2_2") (pintype "passive"))
    )
    (net (code "121") (name "Net-(IC11B-VCC)") (class "Default")
      (node (ref "IC11") (pin "20") (pinfunction "VCC_20") (pintype "power_in"))
      (node (ref "SV59") (pin "19") (pinfunction "19_19") (pintype "passive"))
      (node (ref "SV59") (pin "20") (pinfunction "20_20") (pintype "passive"))
      (node (ref "SV60") (pin "19") (pinfunction "19_19") (pintype "passive"))
      (node (ref "SV60") (pin "20") (pinfunction "20_20") (pintype "passive"))
      (node (ref "SV62") (pin "5") (pinfunction "5_5") (pintype "passive"))
    )
    (net (code "122") (name "Net-(SV1-Pad1)") (class "Default")
      (node (ref "SV1") (pin "1") (pinfunction "1_1") (pintype "passive"))
      (node (ref "SV3") (pin "1") (pinfunction "1_1") (pintype "passive"))
      (node (ref "SV4") (pin "1") (pinfunction "1_1") (pintype "passive"))
      (node (ref "SV5") (pin "2") (pinfunction "2_2") (pintype "passive"))
    )
    (net (code "123") (name "Net-(SV1-Pad2)") (class "Default")
      (node (ref "SV1") (pin "2") (pinfunction "2_2") (pintype "passive"))
      (node (ref "SV3") (pin "2") (pinfunction "2_2") (pintype "passive"))
      (node (ref "SV4") (pin "2") (pinfunction "2_2") (pintype "passive"))
      (node (ref "SV5") (pin "4") (pinfunction "4_4") (pintype "passive"))
    )
    (net (code "124") (name "Net-(SV1-Pad3)") (class "Default")
      (node (ref "SV1") (pin "3") (pinfunction "3_3") (pintype "passive"))
      (node (ref "SV3") (pin "3") (pinfunction "3_3") (pintype "passive"))
      (node (ref "SV4") (pin "3") (pinfunction "3_3") (pintype "passive"))
      (node (ref "SV5") (pin "6") (pinfunction "6_6") (pintype "passive"))
    )
    (net (code "125") (name "Net-(SV1-Pad4)") (class "Default")
      (node (ref "SV1") (pin "4") (pinfunction "4_4") (pintype "passive"))
      (node (ref "SV3") (pin "4") (pinfunction "4_4") (pintype "passive"))
      (node (ref "SV4") (pin "4") (pinfunction "4_4") (pintype "passive"))
      (node (ref "SV5") (pin "8") (pinfunction "8_8") (pintype "passive"))
    )
    (net (code "126") (name "Net-(SV1-Pad5)") (class "Default")
      (node (ref "SV1") (pin "5") (pinfunction "5_5") (pintype "passive"))
      (node (ref "SV3") (pin "5") (pinfunction "5_5") (pintype "passive"))
      (node (ref "SV4") (pin "5") (pinfunction "5_5") (pintype "passive"))
      (node (ref "SV5") (pin "10") (pinfunction "10_10") (pintype "passive"))
    )
    (net (code "127") (name "Net-(SV1-Pad6)") (class "Default")
      (node (ref "SV1") (pin "6") (pinfunction "6_6") (pintype "passive"))
      (node (ref "SV3") (pin "6") (pinfunction "6_6") (pintype "passive"))
      (node (ref "SV4") (pin "6") (pinfunction "6_6") (pintype "passive"))
      (node (ref "SV5") (pin "12") (pinfunction "12_12") (pintype "passive"))
    )
    (net (code "128") (name "Net-(SV1-Pad7)") (class "Default")
      (node (ref "SV1") (pin "7") (pinfunction "7_7") (pintype "passive"))
      (node (ref "SV3") (pin "7") (pinfunction "7_7") (pintype "passive"))
      (node (ref "SV4") (pin "7") (pinfunction "7_7") (pintype "passive"))
      (node (ref "SV5") (pin "14") (pinfunction "14_14") (pintype "passive"))
    )
    (net (code "129") (name "Net-(SV1-Pad8)") (class "Default")
      (node (ref "SV1") (pin "8") (pinfunction "8_8") (pintype "passive"))
      (node (ref "SV3") (pin "8") (pinfunction "8_8") (pintype "passive"))
      (node (ref "SV4") (pin "8") (pinfunction "8_8") (pintype "passive"))
      (node (ref "SV5") (pin "16") (pinfunction "16_16") (pintype "passive"))
    )
    (net (code "130") (name "Net-(SV1-Pad9)") (class "Default")
      (node (ref "SV1") (pin "9") (pinfunction "9_9") (pintype "passive"))
      (node (ref "SV3") (pin "9") (pinfunction "9_9") (pintype "passive"))
      (node (ref "SV4") (pin "9") (pinfunction "9_9") (pintype "passive"))
      (node (ref "SV5") (pin "18") (pinfunction "18_18") (pintype "passive"))
    )
    (net (code "131") (name "Net-(SV1-Pad10)") (class "Default")
      (node (ref "SV1") (pin "10") (pinfunction "10_10") (pintype "passive"))
      (node (ref "SV3") (pin "10") (pinfunction "10_10") (pintype "passive"))
      (node (ref "SV4") (pin "10") (pinfunction "10_10") (pintype "passive"))
      (node (ref "SV5") (pin "20") (pinfunction "20_20") (pintype "passive"))
    )
    (net (code "132") (name "Net-(SV1-Pad11)") (class "Default")
      (node (ref "SV1") (pin "11") (pinfunction "11_11") (pintype "passive"))
      (node (ref "SV3") (pin "11") (pinfunction "11_11") (pintype "passive"))
      (node (ref "SV4") (pin "11") (pinfunction "11_11") (pintype "passive"))
      (node (ref "SV5") (pin "22") (pinfunction "22_22") (pintype "passive"))
    )
    (net (code "133") (name "Net-(SV1-Pad12)") (class "Default")
      (node (ref "SV1") (pin "12") (pinfunction "12_12") (pintype "passive"))
      (node (ref "SV3") (pin "12") (pinfunction "12_12") (pintype "passive"))
      (node (ref "SV4") (pin "12") (pinfunction "12_12") (pintype "passive"))
      (node (ref "SV5") (pin "24") (pinfunction "24_24") (pintype "passive"))
    )
    (net (code "134") (name "Net-(SV1-Pad13)") (class "Default")
      (node (ref "SV1") (pin "13") (pinfunction "13_13") (pintype "passive"))
      (node (ref "SV3") (pin "13") (pinfunction "13_13") (pintype "passive"))
      (node (ref "SV4") (pin "13") (pinfunction "13_13") (pintype "passive"))
      (node (ref "SV5") (pin "26") (pinfunction "26_26") (pintype "passive"))
    )
    (net (code "135") (name "Net-(SV1-Pad14)") (class "Default")
      (node (ref "SV1") (pin "14") (pinfunction "14_14") (pintype "passive"))
      (node (ref "SV3") (pin "14") (pinfunction "14_14") (pintype "passive"))
      (node (ref "SV4") (pin "14") (pinfunction "14_14") (pintype "passive"))
      (node (ref "SV5") (pin "28") (pinfunction "28_28") (pintype "passive"))
    )
    (net (code "136") (name "Net-(SV1-Pad15)") (class "Default")
      (node (ref "SV1") (pin "15") (pinfunction "15_15") (pintype "passive"))
      (node (ref "SV3") (pin "15") (pinfunction "15_15") (pintype "passive"))
      (node (ref "SV4") (pin "15") (pinfunction "15_15") (pintype "passive"))
      (node (ref "SV5") (pin "30") (pinfunction "30_30") (pintype "passive"))
    )
    (net (code "137") (name "Net-(SV1-Pad16)") (class "Default")
      (node (ref "SV1") (pin "16") (pinfunction "16_16") (pintype "passive"))
      (node (ref "SV3") (pin "16") (pinfunction "16_16") (pintype "passive"))
      (node (ref "SV4") (pin "16") (pinfunction "16_16") (pintype "passive"))
      (node (ref "SV5") (pin "32") (pinfunction "32_32") (pintype "passive"))
    )
    (net (code "138") (name "Net-(SV1-Pad17)") (class "Default")
      (node (ref "SV1") (pin "17") (pinfunction "17_17") (pintype "passive"))
      (node (ref "SV3") (pin "17") (pinfunction "17_17") (pintype "passive"))
      (node (ref "SV4") (pin "17") (pinfunction "17_17") (pintype "passive"))
      (node (ref "SV5") (pin "34") (pinfunction "34_34") (pintype "passive"))
    )
    (net (code "139") (name "Net-(SV1-Pad18)") (class "Default")
      (node (ref "SV1") (pin "18") (pinfunction "18_18") (pintype "passive"))
      (node (ref "SV3") (pin "18") (pinfunction "18_18") (pintype "passive"))
      (node (ref "SV4") (pin "18") (pinfunction "18_18") (pintype "passive"))
      (node (ref "SV5") (pin "36") (pinfunction "36_36") (pintype "passive"))
    )
    (net (code "140") (name "Net-(SV1-Pad19)") (class "Default")
      (node (ref "SV1") (pin "19") (pinfunction "19_19") (pintype "passive"))
      (node (ref "SV3") (pin "19") (pinfunction "19_19") (pintype "passive"))
      (node (ref "SV4") (pin "19") (pinfunction "19_19") (pintype "passive"))
      (node (ref "SV5") (pin "38") (pinfunction "38_38") (pintype "passive"))
    )
    (net (code "141") (name "Net-(SV1-Pad20)") (class "Default")
      (node (ref "SV1") (pin "20") (pinfunction "20_20") (pintype "passive"))
      (node (ref "SV3") (pin "20") (pinfunction "20_20") (pintype "passive"))
      (node (ref "SV4") (pin "20") (pinfunction "20_20") (pintype "passive"))
      (node (ref "SV5") (pin "40") (pinfunction "40_40") (pintype "passive"))
    )
    (net (code "142") (name "Net-(SV2-Pad1)") (class "Default")
      (node (ref "SV2") (pin "1") (pinfunction "1_1") (pintype "passive"))
      (node (ref "SV5") (pin "1") (pinfunction "1_1") (pintype "passive"))
      (node (ref "SV7") (pin "1") (pinfunction "1_1") (pintype "passive"))
      (node (ref "SV9") (pin "1") (pinfunction "1_1") (pintype "passive"))
    )
    (net (code "143") (name "Net-(SV2-Pad2)") (class "Default")
      (node (ref "SV2") (pin "2") (pinfunction "2_2") (pintype "passive"))
      (node (ref "SV5") (pin "3") (pinfunction "3_3") (pintype "passive"))
      (node (ref "SV7") (pin "2") (pinfunction "2_2") (pintype "passive"))
      (node (ref "SV9") (pin "2") (pinfunction "2_2") (pintype "passive"))
    )
    (net (code "144") (name "Net-(SV2-Pad3)") (class "Default")
      (node (ref "SV2") (pin "3") (pinfunction "3_3") (pintype "passive"))
      (node (ref "SV5") (pin "5") (pinfunction "5_5") (pintype "passive"))
      (node (ref "SV7") (pin "3") (pinfunction "3_3") (pintype "passive"))
      (node (ref "SV9") (pin "3") (pinfunction "3_3") (pintype "passive"))
    )
    (net (code "145") (name "Net-(SV2-Pad4)") (class "Default")
      (node (ref "SV2") (pin "4") (pinfunction "4_4") (pintype "passive"))
      (node (ref "SV5") (pin "7") (pinfunction "7_7") (pintype "passive"))
      (node (ref "SV7") (pin "4") (pinfunction "4_4") (pintype "passive"))
      (node (ref "SV9") (pin "4") (pinfunction "4_4") (pintype "passive"))
    )
    (net (code "146") (name "Net-(SV2-Pad5)") (class "Default")
      (node (ref "SV2") (pin "5") (pinfunction "5_5") (pintype "passive"))
      (node (ref "SV5") (pin "9") (pinfunction "9_9") (pintype "passive"))
      (node (ref "SV7") (pin "5") (pinfunction "5_5") (pintype "passive"))
      (node (ref "SV9") (pin "5") (pinfunction "5_5") (pintype "passive"))
    )
    (net (code "147") (name "Net-(SV2-Pad6)") (class "Default")
      (node (ref "SV2") (pin "6") (pinfunction "6_6") (pintype "passive"))
      (node (ref "SV5") (pin "11") (pinfunction "11_11") (pintype "passive"))
      (node (ref "SV7") (pin "6") (pinfunction "6_6") (pintype "passive"))
      (node (ref "SV9") (pin "6") (pinfunction "6_6") (pintype "passive"))
    )
    (net (code "148") (name "Net-(SV2-Pad7)") (class "Default")
      (node (ref "SV2") (pin "7") (pinfunction "7_7") (pintype "passive"))
      (node (ref "SV5") (pin "13") (pinfunction "13_13") (pintype "passive"))
      (node (ref "SV7") (pin "7") (pinfunction "7_7") (pintype "passive"))
      (node (ref "SV9") (pin "7") (pinfunction "7_7") (pintype "passive"))
    )
    (net (code "149") (name "Net-(SV2-Pad8)") (class "Default")
      (node (ref "SV2") (pin "8") (pinfunction "8_8") (pintype "passive"))
      (node (ref "SV5") (pin "15") (pinfunction "15_15") (pintype "passive"))
      (node (ref "SV7") (pin "8") (pinfunction "8_8") (pintype "passive"))
      (node (ref "SV9") (pin "8") (pinfunction "8_8") (pintype "passive"))
    )
    (net (code "150") (name "Net-(SV2-Pad9)") (class "Default")
      (node (ref "SV2") (pin "9") (pinfunction "9_9") (pintype "passive"))
      (node (ref "SV5") (pin "17") (pinfunction "17_17") (pintype "passive"))
      (node (ref "SV7") (pin "9") (pinfunction "9_9") (pintype "passive"))
      (node (ref "SV9") (pin "9") (pinfunction "9_9") (pintype "passive"))
    )
    (net (code "151") (name "Net-(SV2-Pad10)") (class "Default")
      (node (ref "SV2") (pin "10") (pinfunction "10_10") (pintype "passive"))
      (node (ref "SV5") (pin "19") (pinfunction "19_19") (pintype "passive"))
      (node (ref "SV7") (pin "10") (pinfunction "10_10") (pintype "passive"))
      (node (ref "SV9") (pin "10") (pinfunction "10_10") (pintype "passive"))
    )
    (net (code "152") (name "Net-(SV2-Pad11)") (class "Default")
      (node (ref "SV2") (pin "11") (pinfunction "11_11") (pintype "passive"))
      (node (ref "SV5") (pin "21") (pinfunction "21_21") (pintype "passive"))
      (node (ref "SV7") (pin "11") (pinfunction "11_11") (pintype "passive"))
      (node (ref "SV9") (pin "11") (pinfunction "11_11") (pintype "passive"))
    )
    (net (code "153") (name "Net-(SV2-Pad12)") (class "Default")
      (node (ref "SV2") (pin "12") (pinfunction "12_12") (pintype "passive"))
      (node (ref "SV5") (pin "23") (pinfunction "23_23") (pintype "passive"))
      (node (ref "SV7") (pin "12") (pinfunction "12_12") (pintype "passive"))
      (node (ref "SV9") (pin "12") (pinfunction "12_12") (pintype "passive"))
    )
    (net (code "154") (name "Net-(SV2-Pad13)") (class "Default")
      (node (ref "SV2") (pin "13") (pinfunction "13_13") (pintype "passive"))
      (node (ref "SV5") (pin "25") (pinfunction "25_25") (pintype "passive"))
      (node (ref "SV7") (pin "13") (pinfunction "13_13") (pintype "passive"))
      (node (ref "SV9") (pin "13") (pinfunction "13_13") (pintype "passive"))
    )
    (net (code "155") (name "Net-(SV2-Pad14)") (class "Default")
      (node (ref "SV2") (pin "14") (pinfunction "14_14") (pintype "passive"))
      (node (ref "SV5") (pin "27") (pinfunction "27_27") (pintype "passive"))
      (node (ref "SV7") (pin "14") (pinfunction "14_14") (pintype "passive"))
      (node (ref "SV9") (pin "14") (pinfunction "14_14") (pintype "passive"))
    )
    (net (code "156") (name "Net-(SV2-Pad15)") (class "Default")
      (node (ref "SV2") (pin "15") (pinfunction "15_15") (pintype "passive"))
      (node (ref "SV5") (pin "29") (pinfunction "29_29") (pintype "passive"))
      (node (ref "SV7") (pin "15") (pinfunction "15_15") (pintype "passive"))
      (node (ref "SV9") (pin "15") (pinfunction "15_15") (pintype "passive"))
    )
    (net (code "157") (name "Net-(SV2-Pad16)") (class "Default")
      (node (ref "SV2") (pin "16") (pinfunction "16_16") (pintype "passive"))
      (node (ref "SV5") (pin "31") (pinfunction "31_31") (pintype "passive"))
      (node (ref "SV7") (pin "16") (pinfunction "16_16") (pintype "passive"))
      (node (ref "SV9") (pin "16") (pinfunction "16_16") (pintype "passive"))
    )
    (net (code "158") (name "Net-(SV2-Pad17)") (class "Default")
      (node (ref "SV2") (pin "17") (pinfunction "17_17") (pintype "passive"))
      (node (ref "SV5") (pin "33") (pinfunction "33_33") (pintype "passive"))
      (node (ref "SV7") (pin "17") (pinfunction "17_17") (pintype "passive"))
      (node (ref "SV9") (pin "17") (pinfunction "17_17") (pintype "passive"))
    )
    (net (code "159") (name "Net-(SV2-Pad18)") (class "Default")
      (node (ref "SV2") (pin "18") (pinfunction "18_18") (pintype "passive"))
      (node (ref "SV5") (pin "35") (pinfunction "35_35") (pintype "passive"))
      (node (ref "SV7") (pin "18") (pinfunction "18_18") (pintype "passive"))
      (node (ref "SV9") (pin "18") (pinfunction "18_18") (pintype "passive"))
    )
    (net (code "160") (name "Net-(SV2-Pad19)") (class "Default")
      (node (ref "SV2") (pin "19") (pinfunction "19_19") (pintype "passive"))
      (node (ref "SV5") (pin "37") (pinfunction "37_37") (pintype "passive"))
      (node (ref "SV7") (pin "19") (pinfunction "19_19") (pintype "passive"))
      (node (ref "SV9") (pin "19") (pinfunction "19_19") (pintype "passive"))
    )
    (net (code "161") (name "Net-(SV2-Pad20)") (class "Default")
      (node (ref "SV2") (pin "20") (pinfunction "20_20") (pintype "passive"))
      (node (ref "SV5") (pin "39") (pinfunction "39_39") (pintype "passive"))
      (node (ref "SV7") (pin "20") (pinfunction "20_20") (pintype "passive"))
      (node (ref "SV9") (pin "20") (pinfunction "20_20") (pintype "passive"))
    )
    (net (code "162") (name "Net-(SV11-Pad1)") (class "Default")
      (node (ref "SV11") (pin "1") (pinfunction "1_1") (pintype "passive"))
      (node (ref "SV13") (pin "1") (pinfunction "1_1") (pintype "passive"))
      (node (ref "SV16") (pin "1") (pinfunction "1_1") (pintype "passive"))
      (node (ref "SV17") (pin "1") (pinfunction "1_1") (pintype "passive"))
    )
    (net (code "163") (name "Net-(SV11-Pad2)") (class "Default")
      (node (ref "SV11") (pin "2") (pinfunction "2_2") (pintype "passive"))
      (node (ref "SV12") (pin "1") (pinfunction "1_1") (pintype "passive"))
      (node (ref "SV14") (pin "1") (pinfunction "1_1") (pintype "passive"))
      (node (ref "SV15") (pin "1") (pinfunction "1_1") (pintype "passive"))
    )
    (net (code "164") (name "Net-(SV11-Pad3)") (class "Default")
      (node (ref "SV11") (pin "3") (pinfunction "3_3") (pintype "passive"))
      (node (ref "SV13") (pin "2") (pinfunction "2_2") (pintype "passive"))
      (node (ref "SV16") (pin "2") (pinfunction "2_2") (pintype "passive"))
      (node (ref "SV17") (pin "2") (pinfunction "2_2") (pintype "passive"))
    )
    (net (code "165") (name "Net-(SV11-Pad4)") (class "Default")
      (node (ref "SV11") (pin "4") (pinfunction "4_4") (pintype "passive"))
      (node (ref "SV12") (pin "2") (pinfunction "2_2") (pintype "passive"))
      (node (ref "SV14") (pin "2") (pinfunction "2_2") (pintype "passive"))
      (node (ref "SV15") (pin "2") (pinfunction "2_2") (pintype "passive"))
    )
    (net (code "166") (name "Net-(SV11-Pad5)") (class "Default")
      (node (ref "SV11") (pin "5") (pinfunction "5_5") (pintype "passive"))
      (node (ref "SV13") (pin "3") (pinfunction "3_3") (pintype "passive"))
      (node (ref "SV16") (pin "3") (pinfunction "3_3") (pintype "passive"))
      (node (ref "SV17") (pin "3") (pinfunction "3_3") (pintype "passive"))
    )
    (net (code "167") (name "Net-(SV11-Pad6)") (class "Default")
      (node (ref "SV11") (pin "6") (pinfunction "6_6") (pintype "passive"))
      (node (ref "SV12") (pin "3") (pinfunction "3_3") (pintype "passive"))
      (node (ref "SV14") (pin "3") (pinfunction "3_3") (pintype "passive"))
      (node (ref "SV15") (pin "3") (pinfunction "3_3") (pintype "passive"))
    )
    (net (code "168") (name "Net-(SV11-Pad7)") (class "Default")
      (node (ref "SV11") (pin "7") (pinfunction "7_7") (pintype "passive"))
      (node (ref "SV13") (pin "4") (pinfunction "4_4") (pintype "passive"))
      (node (ref "SV16") (pin "4") (pinfunction "4_4") (pintype "passive"))
      (node (ref "SV17") (pin "4") (pinfunction "4_4") (pintype "passive"))
    )
    (net (code "169") (name "Net-(SV11-Pad8)") (class "Default")
      (node (ref "SV11") (pin "8") (pinfunction "8_8") (pintype "passive"))
      (node (ref "SV12") (pin "4") (pinfunction "4_4") (pintype "passive"))
      (node (ref "SV14") (pin "4") (pinfunction "4_4") (pintype "passive"))
      (node (ref "SV15") (pin "4") (pinfunction "4_4") (pintype "passive"))
    )
    (net (code "170") (name "Net-(SV11-Pad9)") (class "Default")
      (node (ref "SV11") (pin "9") (pinfunction "9_9") (pintype "passive"))
      (node (ref "SV13") (pin "5") (pinfunction "5_5") (pintype "passive"))
      (node (ref "SV16") (pin "5") (pinfunction "5_5") (pintype "passive"))
      (node (ref "SV17") (pin "5") (pinfunction "5_5") (pintype "passive"))
    )
    (net (code "171") (name "Net-(SV11-Pad10)") (class "Default")
      (node (ref "SV11") (pin "10") (pinfunction "10_10") (pintype "passive"))
      (node (ref "SV12") (pin "5") (pinfunction "5_5") (pintype "passive"))
      (node (ref "SV14") (pin "5") (pinfunction "5_5") (pintype "passive"))
      (node (ref "SV15") (pin "5") (pinfunction "5_5") (pintype "passive"))
    )
    (net (code "172") (name "Net-(SV11-Pad11)") (class "Default")
      (node (ref "SV11") (pin "11") (pinfunction "11_11") (pintype "passive"))
      (node (ref "SV13") (pin "6") (pinfunction "6_6") (pintype "passive"))
      (node (ref "SV16") (pin "6") (pinfunction "6_6") (pintype "passive"))
      (node (ref "SV17") (pin "6") (pinfunction "6_6") (pintype "passive"))
    )
    (net (code "173") (name "Net-(SV11-Pad12)") (class "Default")
      (node (ref "SV11") (pin "12") (pinfunction "12_12") (pintype "passive"))
      (node (ref "SV12") (pin "6") (pinfunction "6_6") (pintype "passive"))
      (node (ref "SV14") (pin "6") (pinfunction "6_6") (pintype "passive"))
      (node (ref "SV15") (pin "6") (pinfunction "6_6") (pintype "passive"))
    )
    (net (code "174") (name "Net-(SV11-Pad13)") (class "Default")
      (node (ref "SV11") (pin "13") (pinfunction "13_13") (pintype "passive"))
      (node (ref "SV13") (pin "7") (pinfunction "7_7") (pintype "passive"))
      (node (ref "SV16") (pin "7") (pinfunction "7_7") (pintype "passive"))
      (node (ref "SV17") (pin "7") (pinfunction "7_7") (pintype "passive"))
    )
    (net (code "175") (name "Net-(SV11-Pad14)") (class "Default")
      (node (ref "SV11") (pin "14") (pinfunction "14_14") (pintype "passive"))
      (node (ref "SV12") (pin "7") (pinfunction "7_7") (pintype "passive"))
      (node (ref "SV14") (pin "7") (pinfunction "7_7") (pintype "passive"))
      (node (ref "SV15") (pin "7") (pinfunction "7_7") (pintype "passive"))
    )
    (net (code "176") (name "Net-(SV11-Pad15)") (class "Default")
      (node (ref "SV11") (pin "15") (pinfunction "15_15") (pintype "passive"))
      (node (ref "SV13") (pin "8") (pinfunction "8_8") (pintype "passive"))
      (node (ref "SV16") (pin "8") (pinfunction "8_8") (pintype "passive"))
      (node (ref "SV17") (pin "8") (pinfunction "8_8") (pintype "passive"))
    )
    (net (code "177") (name "Net-(SV11-Pad16)") (class "Default")
      (node (ref "SV11") (pin "16") (pinfunction "16_16") (pintype "passive"))
      (node (ref "SV12") (pin "8") (pinfunction "8_8") (pintype "passive"))
      (node (ref "SV14") (pin "8") (pinfunction "8_8") (pintype "passive"))
      (node (ref "SV15") (pin "8") (pinfunction "8_8") (pintype "passive"))
    )
    (net (code "178") (name "Net-(SV11-Pad17)") (class "Default")
      (node (ref "SV11") (pin "17") (pinfunction "17_17") (pintype "passive"))
      (node (ref "SV13") (pin "9") (pinfunction "9_9") (pintype "passive"))
      (node (ref "SV16") (pin "9") (pinfunction "9_9") (pintype "passive"))
      (node (ref "SV17") (pin "9") (pinfunction "9_9") (pintype "passive"))
    )
    (net (code "179") (name "Net-(SV11-Pad18)") (class "Default")
      (node (ref "SV11") (pin "18") (pinfunction "18_18") (pintype "passive"))
      (node (ref "SV12") (pin "9") (pinfunction "9_9") (pintype "passive"))
      (node (ref "SV14") (pin "9") (pinfunction "9_9") (pintype "passive"))
      (node (ref "SV15") (pin "9") (pinfunction "9_9") (pintype "passive"))
    )
    (net (code "180") (name "Net-(SV11-Pad19)") (class "Default")
      (node (ref "SV11") (pin "19") (pinfunction "19_19") (pintype "passive"))
      (node (ref "SV13") (pin "10") (pinfunction "10_10") (pintype "passive"))
      (node (ref "SV16") (pin "10") (pinfunction "10_10") (pintype "passive"))
      (node (ref "SV17") (pin "10") (pinfunction "10_10") (pintype "passive"))
    )
    (net (code "181") (name "Net-(SV11-Pad20)") (class "Default")
      (node (ref "SV11") (pin "20") (pinfunction "20_20") (pintype "passive"))
      (node (ref "SV12") (pin "10") (pinfunction "10_10") (pintype "passive"))
      (node (ref "SV14") (pin "10") (pinfunction "10_10") (pintype "passive"))
      (node (ref "SV15") (pin "10") (pinfunction "10_10") (pintype "passive"))
    )
    (net (code "182") (name "Net-(SV11-Pad21)") (class "Default")
      (node (ref "SV11") (pin "21") (pinfunction "21_21") (pintype "passive"))
      (node (ref "SV13") (pin "11") (pinfunction "11_11") (pintype "passive"))
      (node (ref "SV16") (pin "11") (pinfunction "11_11") (pintype "passive"))
      (node (ref "SV17") (pin "11") (pinfunction "11_11") (pintype "passive"))
    )
    (net (code "183") (name "Net-(SV11-Pad22)") (class "Default")
      (node (ref "SV11") (pin "22") (pinfunction "22_22") (pintype "passive"))
      (node (ref "SV12") (pin "11") (pinfunction "11_11") (pintype "passive"))
      (node (ref "SV14") (pin "11") (pinfunction "11_11") (pintype "passive"))
      (node (ref "SV15") (pin "11") (pinfunction "11_11") (pintype "passive"))
    )
    (net (code "184") (name "Net-(SV11-Pad23)") (class "Default")
      (node (ref "SV11") (pin "23") (pinfunction "23_23") (pintype "passive"))
      (node (ref "SV13") (pin "12") (pinfunction "12_12") (pintype "passive"))
      (node (ref "SV16") (pin "12") (pinfunction "12_12") (pintype "passive"))
      (node (ref "SV17") (pin "12") (pinfunction "12_12") (pintype "passive"))
    )
    (net (code "185") (name "Net-(SV11-Pad24)") (class "Default")
      (node (ref "SV11") (pin "24") (pinfunction "24_24") (pintype "passive"))
      (node (ref "SV12") (pin "12") (pinfunction "12_12") (pintype "passive"))
      (node (ref "SV14") (pin "12") (pinfunction "12_12") (pintype "passive"))
      (node (ref "SV15") (pin "12") (pinfunction "12_12") (pintype "passive"))
    )
    (net (code "186") (name "Net-(SV11-Pad25)") (class "Default")
      (node (ref "SV11") (pin "25") (pinfunction "25_25") (pintype "passive"))
      (node (ref "SV13") (pin "13") (pinfunction "13_13") (pintype "passive"))
      (node (ref "SV16") (pin "13") (pinfunction "13_13") (pintype "passive"))
      (node (ref "SV17") (pin "13") (pinfunction "13_13") (pintype "passive"))
    )
    (net (code "187") (name "Net-(SV11-Pad26)") (class "Default")
      (node (ref "SV11") (pin "26") (pinfunction "26_26") (pintype "passive"))
      (node (ref "SV12") (pin "13") (pinfunction "13_13") (pintype "passive"))
      (node (ref "SV14") (pin "13") (pinfunction "13_13") (pintype "passive"))
      (node (ref "SV15") (pin "13") (pinfunction "13_13") (pintype "passive"))
    )
    (net (code "188") (name "Net-(SV11-Pad27)") (class "Default")
      (node (ref "SV11") (pin "27") (pinfunction "27_27") (pintype "passive"))
      (node (ref "SV13") (pin "14") (pinfunction "14_14") (pintype "passive"))
      (node (ref "SV16") (pin "14") (pinfunction "14_14") (pintype "passive"))
      (node (ref "SV17") (pin "14") (pinfunction "14_14") (pintype "passive"))
    )
    (net (code "189") (name "Net-(SV11-Pad28)") (class "Default")
      (node (ref "SV11") (pin "28") (pinfunction "28_28") (pintype "passive"))
      (node (ref "SV12") (pin "14") (pinfunction "14_14") (pintype "passive"))
      (node (ref "SV14") (pin "14") (pinfunction "14_14") (pintype "passive"))
      (node (ref "SV15") (pin "14") (pinfunction "14_14") (pintype "passive"))
    )
    (net (code "190") (name "Net-(SV11-Pad29)") (class "Default")
      (node (ref "SV11") (pin "29") (pinfunction "29_29") (pintype "passive"))
      (node (ref "SV13") (pin "15") (pinfunction "15_15") (pintype "passive"))
      (node (ref "SV16") (pin "15") (pinfunction "15_15") (pintype "passive"))
      (node (ref "SV17") (pin "15") (pinfunction "15_15") (pintype "passive"))
    )
    (net (code "191") (name "Net-(SV11-Pad30)") (class "Default")
      (node (ref "SV11") (pin "30") (pinfunction "30_30") (pintype "passive"))
      (node (ref "SV12") (pin "15") (pinfunction "15_15") (pintype "passive"))
      (node (ref "SV14") (pin "15") (pinfunction "15_15") (pintype "passive"))
      (node (ref "SV15") (pin "15") (pinfunction "15_15") (pintype "passive"))
    )
    (net (code "192") (name "Net-(SV11-Pad31)") (class "Default")
      (node (ref "SV11") (pin "31") (pinfunction "31_31") (pintype "passive"))
      (node (ref "SV13") (pin "16") (pinfunction "16_16") (pintype "passive"))
      (node (ref "SV16") (pin "16") (pinfunction "16_16") (pintype "passive"))
      (node (ref "SV17") (pin "16") (pinfunction "16_16") (pintype "passive"))
    )
    (net (code "193") (name "Net-(SV11-Pad32)") (class "Default")
      (node (ref "SV11") (pin "32") (pinfunction "32_32") (pintype "passive"))
      (node (ref "SV12") (pin "16") (pinfunction "16_16") (pintype "passive"))
      (node (ref "SV14") (pin "16") (pinfunction "16_16") (pintype "passive"))
      (node (ref "SV15") (pin "16") (pinfunction "16_16") (pintype "passive"))
    )
    (net (code "194") (name "Net-(SV11-Pad33)") (class "Default")
      (node (ref "SV11") (pin "33") (pinfunction "33_33") (pintype "passive"))
      (node (ref "SV13") (pin "17") (pinfunction "17_17") (pintype "passive"))
      (node (ref "SV16") (pin "17") (pinfunction "17_17") (pintype "passive"))
      (node (ref "SV17") (pin "17") (pinfunction "17_17") (pintype "passive"))
    )
    (net (code "195") (name "Net-(SV11-Pad34)") (class "Default")
      (node (ref "SV11") (pin "34") (pinfunction "34_34") (pintype "passive"))
      (node (ref "SV12") (pin "17") (pinfunction "17_17") (pintype "passive"))
      (node (ref "SV14") (pin "17") (pinfunction "17_17") (pintype "passive"))
      (node (ref "SV15") (pin "17") (pinfunction "17_17") (pintype "passive"))
    )
    (net (code "196") (name "Net-(SV11-Pad35)") (class "Default")
      (node (ref "SV11") (pin "35") (pinfunction "35_35") (pintype "passive"))
      (node (ref "SV13") (pin "18") (pinfunction "18_18") (pintype "passive"))
      (node (ref "SV16") (pin "18") (pinfunction "18_18") (pintype "passive"))
      (node (ref "SV17") (pin "18") (pinfunction "18_18") (pintype "passive"))
    )
    (net (code "197") (name "Net-(SV11-Pad36)") (class "Default")
      (node (ref "SV11") (pin "36") (pinfunction "36_36") (pintype "passive"))
      (node (ref "SV12") (pin "18") (pinfunction "18_18") (pintype "passive"))
      (node (ref "SV14") (pin "18") (pinfunction "18_18") (pintype "passive"))
      (node (ref "SV15") (pin "18") (pinfunction "18_18") (pintype "passive"))
    )
    (net (code "198") (name "Net-(SV11-Pad37)") (class "Default")
      (node (ref "SV11") (pin "37") (pinfunction "37_37") (pintype "passive"))
      (node (ref "SV13") (pin "19") (pinfunction "19_19") (pintype "passive"))
      (node (ref "SV16") (pin "19") (pinfunction "19_19") (pintype "passive"))
      (node (ref "SV17") (pin "19") (pinfunction "19_19") (pintype "passive"))
    )
    (net (code "199") (name "Net-(SV11-Pad38)") (class "Default")
      (node (ref "SV11") (pin "38") (pinfunction "38_38") (pintype "passive"))
      (node (ref "SV12") (pin "19") (pinfunction "19_19") (pintype "passive"))
      (node (ref "SV14") (pin "19") (pinfunction "19_19") (pintype "passive"))
      (node (ref "SV15") (pin "19") (pinfunction "19_19") (pintype "passive"))
    )
    (net (code "200") (name "Net-(SV11-Pad39)") (class "Default")
      (node (ref "SV11") (pin "39") (pinfunction "39_39") (pintype "passive"))
      (node (ref "SV13") (pin "20") (pinfunction "20_20") (pintype "passive"))
      (node (ref "SV16") (pin "20") (pinfunction "20_20") (pintype "passive"))
      (node (ref "SV17") (pin "20") (pinfunction "20_20") (pintype "passive"))
    )
    (net (code "201") (name "Net-(SV11-Pad40)") (class "Default")
      (node (ref "SV11") (pin "40") (pinfunction "40_40") (pintype "passive"))
      (node (ref "SV12") (pin "20") (pinfunction "20_20") (pintype "passive"))
      (node (ref "SV14") (pin "20") (pinfunction "20_20") (pintype "passive"))
      (node (ref "SV15") (pin "20") (pinfunction "20_20") (pintype "passive"))
    )
    (net (code "202") (name "Net-(SV21-Pad1)") (class "Default")
      (node (ref "SV21") (pin "1") (pinfunction "1_1") (pintype "passive"))
      (node (ref "SV24") (pin "1") (pinfunction "1_1") (pintype "passive"))
      (node (ref "SV25") (pin "1") (pinfunction "1_1") (pintype "passive"))
    )
    (net (code "203") (name "Net-(SV21-Pad2)") (class "Default")
      (node (ref "SV21") (pin "2") (pinfunction "2_2") (pintype "passive"))
      (node (ref "SV24") (pin "2") (pinfunction "2_2") (pintype "passive"))
      (node (ref "SV25") (pin "2") (pinfunction "2_2") (pintype "passive"))
    )
    (net (code "204") (name "Net-(SV21-Pad3)") (class "Default")
      (node (ref "SV21") (pin "3") (pinfunction "3_3") (pintype "passive"))
      (node (ref "SV24") (pin "3") (pinfunction "3_3") (pintype "passive"))
      (node (ref "SV25") (pin "3") (pinfunction "3_3") (pintype "passive"))
    )
    (net (code "205") (name "Net-(SV21-Pad4)") (class "Default")
      (node (ref "SV21") (pin "4") (pinfunction "4_4") (pintype "passive"))
      (node (ref "SV24") (pin "4") (pinfunction "4_4") (pintype "passive"))
      (node (ref "SV25") (pin "4") (pinfunction "4_4") (pintype "passive"))
    )
    (net (code "206") (name "Net-(SV21-Pad5)") (class "Default")
      (node (ref "SV21") (pin "5") (pinfunction "5_5") (pintype "passive"))
      (node (ref "SV24") (pin "5") (pinfunction "5_5") (pintype "passive"))
      (node (ref "SV25") (pin "5") (pinfunction "5_5") (pintype "passive"))
    )
    (net (code "207") (name "Net-(SV21-Pad6)") (class "Default")
      (node (ref "SV21") (pin "6") (pinfunction "6_6") (pintype "passive"))
      (node (ref "SV24") (pin "6") (pinfunction "6_6") (pintype "passive"))
      (node (ref "SV25") (pin "6") (pinfunction "6_6") (pintype "passive"))
    )
    (net (code "208") (name "Net-(SV21-Pad7)") (class "Default")
      (node (ref "SV21") (pin "7") (pinfunction "7_7") (pintype "passive"))
      (node (ref "SV24") (pin "7") (pinfunction "7_7") (pintype "passive"))
      (node (ref "SV25") (pin "7") (pinfunction "7_7") (pintype "passive"))
    )
    (net (code "209") (name "Net-(SV21-Pad8)") (class "Default")
      (node (ref "SV21") (pin "8") (pinfunction "8_8") (pintype "passive"))
      (node (ref "SV24") (pin "8") (pinfunction "8_8") (pintype "passive"))
      (node (ref "SV25") (pin "8") (pinfunction "8_8") (pintype "passive"))
    )
    (net (code "210") (name "Net-(SV21-Pad9)") (class "Default")
      (node (ref "SV21") (pin "9") (pinfunction "9_9") (pintype "passive"))
      (node (ref "SV24") (pin "9") (pinfunction "9_9") (pintype "passive"))
      (node (ref "SV25") (pin "9") (pinfunction "9_9") (pintype "passive"))
    )
    (net (code "211") (name "Net-(SV21-Pad10)") (class "Default")
      (node (ref "SV21") (pin "10") (pinfunction "10_10") (pintype "passive"))
      (node (ref "SV24") (pin "10") (pinfunction "10_10") (pintype "passive"))
      (node (ref "SV25") (pin "10") (pinfunction "10_10") (pintype "passive"))
    )
    (net (code "212") (name "Net-(SV21-Pad11)") (class "Default")
      (node (ref "SV21") (pin "11") (pinfunction "11_11") (pintype "passive"))
      (node (ref "SV24") (pin "11") (pinfunction "11_11") (pintype "passive"))
      (node (ref "SV25") (pin "11") (pinfunction "11_11") (pintype "passive"))
    )
    (net (code "213") (name "Net-(SV21-Pad12)") (class "Default")
      (node (ref "SV21") (pin "12") (pinfunction "12_12") (pintype "passive"))
      (node (ref "SV24") (pin "12") (pinfunction "12_12") (pintype "passive"))
      (node (ref "SV25") (pin "12") (pinfunction "12_12") (pintype "passive"))
    )
    (net (code "214") (name "Net-(SV21-Pad13)") (class "Default")
      (node (ref "SV21") (pin "13") (pinfunction "13_13") (pintype "passive"))
      (node (ref "SV24") (pin "13") (pinfunction "13_13") (pintype "passive"))
      (node (ref "SV25") (pin "13") (pinfunction "13_13") (pintype "passive"))
    )
    (net (code "215") (name "Net-(SV21-Pad14)") (class "Default")
      (node (ref "SV21") (pin "14") (pinfunction "14_14") (pintype "passive"))
      (node (ref "SV24") (pin "14") (pinfunction "14_14") (pintype "passive"))
      (node (ref "SV25") (pin "14") (pinfunction "14_14") (pintype "passive"))
    )
    (net (code "216") (name "Net-(SV21-Pad15)") (class "Default")
      (node (ref "SV21") (pin "15") (pinfunction "15_15") (pintype "passive"))
      (node (ref "SV24") (pin "15") (pinfunction "15_15") (pintype "passive"))
      (node (ref "SV25") (pin "15") (pinfunction "15_15") (pintype "passive"))
    )
    (net (code "217") (name "Net-(SV21-Pad16)") (class "Default")
      (node (ref "SV21") (pin "16") (pinfunction "16_16") (pintype "passive"))
      (node (ref "SV24") (pin "16") (pinfunction "16_16") (pintype "passive"))
      (node (ref "SV25") (pin "16") (pinfunction "16_16") (pintype "passive"))
    )
    (net (code "218") (name "Net-(SV21-Pad17)") (class "Default")
      (node (ref "SV21") (pin "17") (pinfunction "17_17") (pintype "passive"))
      (node (ref "SV24") (pin "17") (pinfunction "17_17") (pintype "passive"))
      (node (ref "SV25") (pin "17") (pinfunction "17_17") (pintype "passive"))
    )
    (net (code "219") (name "Net-(SV21-Pad18)") (class "Default")
      (node (ref "SV21") (pin "18") (pinfunction "18_18") (pintype "passive"))
      (node (ref "SV24") (pin "18") (pinfunction "18_18") (pintype "passive"))
      (node (ref "SV25") (pin "18") (pinfunction "18_18") (pintype "passive"))
    )
    (net (code "220") (name "Net-(SV21-Pad19)") (class "Default")
      (node (ref "SV21") (pin "19") (pinfunction "19_19") (pintype "passive"))
      (node (ref "SV24") (pin "19") (pinfunction "19_19") (pintype "passive"))
      (node (ref "SV25") (pin "19") (pinfunction "19_19") (pintype "passive"))
    )
    (net (code "221") (name "Net-(SV21-Pad20)") (class "Default")
      (node (ref "SV21") (pin "20") (pinfunction "20_20") (pintype "passive"))
      (node (ref "SV24") (pin "20") (pinfunction "20_20") (pintype "passive"))
      (node (ref "SV25") (pin "20") (pinfunction "20_20") (pintype "passive"))
    )
    (net (code "222") (name "Net-(SV22-Pad1)") (class "Default")
      (node (ref "SV22") (pin "1") (pinfunction "1_1") (pintype "passive"))
      (node (ref "SV23") (pin "1") (pinfunction "1_1") (pintype "passive"))
      (node (ref "SV8") (pin "1") (pinfunction "1_1") (pintype "passive"))
    )
    (net (code "223") (name "Net-(SV22-Pad2)") (class "Default")
      (node (ref "SV22") (pin "2") (pinfunction "2_2") (pintype "passive"))
      (node (ref "SV23") (pin "2") (pinfunction "2_2") (pintype "passive"))
      (node (ref "SV8") (pin "2") (pinfunction "2_2") (pintype "passive"))
    )
    (net (code "224") (name "Net-(SV22-Pad3)") (class "Default")
      (node (ref "SV22") (pin "3") (pinfunction "3_3") (pintype "passive"))
      (node (ref "SV23") (pin "3") (pinfunction "3_3") (pintype "passive"))
      (node (ref "SV8") (pin "3") (pinfunction "3_3") (pintype "passive"))
    )
    (net (code "225") (name "Net-(SV22-Pad4)") (class "Default")
      (node (ref "SV22") (pin "4") (pinfunction "4_4") (pintype "passive"))
      (node (ref "SV23") (pin "4") (pinfunction "4_4") (pintype "passive"))
      (node (ref "SV8") (pin "4") (pinfunction "4_4") (pintype "passive"))
    )
    (net (code "226") (name "Net-(SV22-Pad5)") (class "Default")
      (node (ref "SV22") (pin "5") (pinfunction "5_5") (pintype "passive"))
      (node (ref "SV23") (pin "5") (pinfunction "5_5") (pintype "passive"))
      (node (ref "SV8") (pin "5") (pinfunction "5_5") (pintype "passive"))
    )
    (net (code "227") (name "Net-(SV22-Pad6)") (class "Default")
      (node (ref "SV22") (pin "6") (pinfunction "6_6") (pintype "passive"))
      (node (ref "SV23") (pin "6") (pinfunction "6_6") (pintype "passive"))
      (node (ref "SV8") (pin "6") (pinfunction "6_6") (pintype "passive"))
    )
    (net (code "228") (name "Net-(SV22-Pad7)") (class "Default")
      (node (ref "SV22") (pin "7") (pinfunction "7_7") (pintype "passive"))
      (node (ref "SV23") (pin "7") (pinfunction "7_7") (pintype "passive"))
      (node (ref "SV8") (pin "7") (pinfunction "7_7") (pintype "passive"))
    )
    (net (code "229") (name "Net-(SV22-Pad8)") (class "Default")
      (node (ref "SV22") (pin "8") (pinfunction "8_8") (pintype "passive"))
      (node (ref "SV23") (pin "8") (pinfunction "8_8") (pintype "passive"))
      (node (ref "SV8") (pin "8") (pinfunction "8_8") (pintype "passive"))
    )
    (net (code "230") (name "Net-(SV22-Pad9)") (class "Default")
      (node (ref "SV22") (pin "9") (pinfunction "9_9") (pintype "passive"))
      (node (ref "SV23") (pin "9") (pinfunction "9_9") (pintype "passive"))
      (node (ref "SV8") (pin "9") (pinfunction "9_9") (pintype "passive"))
    )
    (net (code "231") (name "Net-(SV22-Pad10)") (class "Default")
      (node (ref "SV22") (pin "10") (pinfunction "10_10") (pintype "passive"))
      (node (ref "SV23") (pin "10") (pinfunction "10_10") (pintype "passive"))
      (node (ref "SV8") (pin "10") (pinfunction "10_10") (pintype "passive"))
    )
    (net (code "232") (name "Net-(SV22-Pad11)") (class "Default")
      (node (ref "SV22") (pin "11") (pinfunction "11_11") (pintype "passive"))
      (node (ref "SV23") (pin "11") (pinfunction "11_11") (pintype "passive"))
      (node (ref "SV8") (pin "11") (pinfunction "11_11") (pintype "passive"))
    )
    (net (code "233") (name "Net-(SV22-Pad12)") (class "Default")
      (node (ref "SV22") (pin "12") (pinfunction "12_12") (pintype "passive"))
      (node (ref "SV23") (pin "12") (pinfunction "12_12") (pintype "passive"))
      (node (ref "SV8") (pin "12") (pinfunction "12_12") (pintype "passive"))
    )
    (net (code "234") (name "Net-(SV22-Pad13)") (class "Default")
      (node (ref "SV22") (pin "13") (pinfunction "13_13") (pintype "passive"))
      (node (ref "SV23") (pin "13") (pinfunction "13_13") (pintype "passive"))
      (node (ref "SV8") (pin "13") (pinfunction "13_13") (pintype "passive"))
    )
    (net (code "235") (name "Net-(SV22-Pad14)") (class "Default")
      (node (ref "SV22") (pin "14") (pinfunction "14_14") (pintype "passive"))
      (node (ref "SV23") (pin "14") (pinfunction "14_14") (pintype "passive"))
      (node (ref "SV8") (pin "14") (pinfunction "14_14") (pintype "passive"))
    )
    (net (code "236") (name "Net-(SV22-Pad15)") (class "Default")
      (node (ref "SV22") (pin "15") (pinfunction "15_15") (pintype "passive"))
      (node (ref "SV23") (pin "15") (pinfunction "15_15") (pintype "passive"))
      (node (ref "SV8") (pin "15") (pinfunction "15_15") (pintype "passive"))
    )
    (net (code "237") (name "Net-(SV22-Pad16)") (class "Default")
      (node (ref "SV22") (pin "16") (pinfunction "16_16") (pintype "passive"))
      (node (ref "SV23") (pin "16") (pinfunction "16_16") (pintype "passive"))
      (node (ref "SV8") (pin "16") (pinfunction "16_16") (pintype "passive"))
    )
    (net (code "238") (name "Net-(SV22-Pad17)") (class "Default")
      (node (ref "SV22") (pin "17") (pinfunction "17_17") (pintype "passive"))
      (node (ref "SV23") (pin "17") (pinfunction "17_17") (pintype "passive"))
      (node (ref "SV8") (pin "17") (pinfunction "17_17") (pintype "passive"))
    )
    (net (code "239") (name "Net-(SV22-Pad18)") (class "Default")
      (node (ref "SV22") (pin "18") (pinfunction "18_18") (pintype "passive"))
      (node (ref "SV23") (pin "18") (pinfunction "18_18") (pintype "passive"))
      (node (ref "SV8") (pin "18") (pinfunction "18_18") (pintype "passive"))
    )
    (net (code "240") (name "Net-(SV22-Pad19)") (class "Default")
      (node (ref "SV22") (pin "19") (pinfunction "19_19") (pintype "passive"))
      (node (ref "SV23") (pin "19") (pinfunction "19_19") (pintype "passive"))
      (node (ref "SV8") (pin "19") (pinfunction "19_19") (pintype "passive"))
    )
    (net (code "241") (name "Net-(SV22-Pad20)") (class "Default")
      (node (ref "SV22") (pin "20") (pinfunction "20_20") (pintype "passive"))
      (node (ref "SV23") (pin "20") (pinfunction "20_20") (pintype "passive"))
      (node (ref "SV8") (pin "20") (pinfunction "20_20") (pintype "passive"))
    )
    (net (code "242") (name "Net-(SV27-Pad1)") (class "Default")
      (node (ref "SV27") (pin "1") (pinfunction "1_1") (pintype "passive"))
      (node (ref "SV29") (pin "1") (pinfunction "1_1") (pintype "passive"))
      (node (ref "SV30") (pin "1") (pinfunction "1_1") (pintype "passive"))
    )
    (net (code "243") (name "Net-(SV27-Pad2)") (class "Default")
      (node (ref "SV27") (pin "2") (pinfunction "2_2") (pintype "passive"))
      (node (ref "SV29") (pin "2") (pinfunction "2_2") (pintype "passive"))
      (node (ref "SV30") (pin "2") (pinfunction "2_2") (pintype "passive"))
    )
    (net (code "244") (name "Net-(SV27-Pad3)") (class "Default")
      (node (ref "SV27") (pin "3") (pinfunction "3_3") (pintype "passive"))
      (node (ref "SV29") (pin "3") (pinfunction "3_3") (pintype "passive"))
      (node (ref "SV30") (pin "3") (pinfunction "3_3") (pintype "passive"))
    )
    (net (code "245") (name "Net-(SV27-Pad4)") (class "Default")
      (node (ref "SV27") (pin "4") (pinfunction "4_4") (pintype "passive"))
      (node (ref "SV29") (pin "4") (pinfunction "4_4") (pintype "passive"))
      (node (ref "SV30") (pin "4") (pinfunction "4_4") (pintype "passive"))
    )
    (net (code "246") (name "Net-(SV27-Pad5)") (class "Default")
      (node (ref "SV27") (pin "5") (pinfunction "5_5") (pintype "passive"))
      (node (ref "SV29") (pin "5") (pinfunction "5_5") (pintype "passive"))
      (node (ref "SV30") (pin "5") (pinfunction "5_5") (pintype "passive"))
    )
    (net (code "247") (name "Net-(SV27-Pad6)") (class "Default")
      (node (ref "SV27") (pin "6") (pinfunction "6_6") (pintype "passive"))
      (node (ref "SV29") (pin "6") (pinfunction "6_6") (pintype "passive"))
      (node (ref "SV30") (pin "6") (pinfunction "6_6") (pintype "passive"))
    )
    (net (code "248") (name "Net-(SV27-Pad7)") (class "Default")
      (node (ref "SV27") (pin "7") (pinfunction "7_7") (pintype "passive"))
      (node (ref "SV29") (pin "7") (pinfunction "7_7") (pintype "passive"))
      (node (ref "SV30") (pin "7") (pinfunction "7_7") (pintype "passive"))
    )
    (net (code "249") (name "Net-(SV27-Pad8)") (class "Default")
      (node (ref "SV27") (pin "8") (pinfunction "8_8") (pintype "passive"))
      (node (ref "SV29") (pin "8") (pinfunction "8_8") (pintype "passive"))
      (node (ref "SV30") (pin "8") (pinfunction "8_8") (pintype "passive"))
    )
    (net (code "250") (name "Net-(SV27-Pad9)") (class "Default")
      (node (ref "SV27") (pin "9") (pinfunction "9_9") (pintype "passive"))
      (node (ref "SV29") (pin "9") (pinfunction "9_9") (pintype "passive"))
      (node (ref "SV30") (pin "9") (pinfunction "9_9") (pintype "passive"))
    )
    (net (code "251") (name "Net-(SV27-Pad10)") (class "Default")
      (node (ref "SV27") (pin "10") (pinfunction "10_10") (pintype "passive"))
      (node (ref "SV29") (pin "10") (pinfunction "10_10") (pintype "passive"))
      (node (ref "SV30") (pin "10") (pinfunction "10_10") (pintype "passive"))
    )
    (net (code "252") (name "Net-(SV27-Pad11)") (class "Default")
      (node (ref "SV27") (pin "11") (pinfunction "11_11") (pintype "passive"))
      (node (ref "SV29") (pin "11") (pinfunction "11_11") (pintype "passive"))
      (node (ref "SV30") (pin "11") (pinfunction "11_11") (pintype "passive"))
    )
    (net (code "253") (name "Net-(SV27-Pad12)") (class "Default")
      (node (ref "SV27") (pin "12") (pinfunction "12_12") (pintype "passive"))
      (node (ref "SV29") (pin "12") (pinfunction "12_12") (pintype "passive"))
      (node (ref "SV30") (pin "12") (pinfunction "12_12") (pintype "passive"))
    )
    (net (code "254") (name "Net-(SV27-Pad13)") (class "Default")
      (node (ref "SV27") (pin "13") (pinfunction "13_13") (pintype "passive"))
      (node (ref "SV29") (pin "13") (pinfunction "13_13") (pintype "passive"))
      (node (ref "SV30") (pin "13") (pinfunction "13_13") (pintype "passive"))
    )
    (net (code "255") (name "Net-(SV27-Pad14)") (class "Default")
      (node (ref "SV27") (pin "14") (pinfunction "14_14") (pintype "passive"))
      (node (ref "SV29") (pin "14") (pinfunction "14_14") (pintype "passive"))
      (node (ref "SV30") (pin "14") (pinfunction "14_14") (pintype "passive"))
    )
    (net (code "256") (name "Net-(SV27-Pad15)") (class "Default")
      (node (ref "SV27") (pin "15") (pinfunction "15_15") (pintype "passive"))
      (node (ref "SV29") (pin "15") (pinfunction "15_15") (pintype "passive"))
      (node (ref "SV30") (pin "15") (pinfunction "15_15") (pintype "passive"))
    )
    (net (code "257") (name "Net-(SV27-Pad16)") (class "Default")
      (node (ref "SV27") (pin "16") (pinfunction "16_16") (pintype "passive"))
      (node (ref "SV29") (pin "16") (pinfunction "16_16") (pintype "passive"))
      (node (ref "SV30") (pin "16") (pinfunction "16_16") (pintype "passive"))
    )
    (net (code "258") (name "Net-(SV27-Pad17)") (class "Default")
      (node (ref "SV27") (pin "17") (pinfunction "17_17") (pintype "passive"))
      (node (ref "SV29") (pin "17") (pinfunction "17_17") (pintype "passive"))
      (node (ref "SV30") (pin "17") (pinfunction "17_17") (pintype "passive"))
    )
    (net (code "259") (name "Net-(SV27-Pad18)") (class "Default")
      (node (ref "SV27") (pin "18") (pinfunction "18_18") (pintype "passive"))
      (node (ref "SV29") (pin "18") (pinfunction "18_18") (pintype "passive"))
      (node (ref "SV30") (pin "18") (pinfunction "18_18") (pintype "passive"))
    )
    (net (code "260") (name "Net-(SV27-Pad19)") (class "Default")
      (node (ref "SV27") (pin "19") (pinfunction "19_19") (pintype "passive"))
      (node (ref "SV29") (pin "19") (pinfunction "19_19") (pintype "passive"))
      (node (ref "SV30") (pin "19") (pinfunction "19_19") (pintype "passive"))
    )
    (net (code "261") (name "Net-(SV27-Pad20)") (class "Default")
      (node (ref "SV27") (pin "20") (pinfunction "20_20") (pintype "passive"))
      (node (ref "SV29") (pin "20") (pinfunction "20_20") (pintype "passive"))
      (node (ref "SV30") (pin "20") (pinfunction "20_20") (pintype "passive"))
    )
    (net (code "262") (name "Net-(SV28-Pad1)") (class "Default")
      (node (ref "SV28") (pin "1") (pinfunction "1_1") (pintype "passive"))
      (node (ref "SV31") (pin "1") (pinfunction "1_1") (pintype "passive"))
      (node (ref "SV32") (pin "1") (pinfunction "1_1") (pintype "passive"))
    )
    (net (code "263") (name "Net-(SV28-Pad2)") (class "Default")
      (node (ref "SV28") (pin "2") (pinfunction "2_2") (pintype "passive"))
      (node (ref "SV31") (pin "2") (pinfunction "2_2") (pintype "passive"))
      (node (ref "SV32") (pin "2") (pinfunction "2_2") (pintype "passive"))
    )
    (net (code "264") (name "Net-(SV28-Pad3)") (class "Default")
      (node (ref "SV28") (pin "3") (pinfunction "3_3") (pintype "passive"))
      (node (ref "SV31") (pin "3") (pinfunction "3_3") (pintype "passive"))
      (node (ref "SV32") (pin "3") (pinfunction "3_3") (pintype "passive"))
    )
    (net (code "265") (name "Net-(SV28-Pad4)") (class "Default")
      (node (ref "SV28") (pin "4") (pinfunction "4_4") (pintype "passive"))
      (node (ref "SV31") (pin "4") (pinfunction "4_4") (pintype "passive"))
      (node (ref "SV32") (pin "4") (pinfunction "4_4") (pintype "passive"))
    )
    (net (code "266") (name "Net-(SV28-Pad5)") (class "Default")
      (node (ref "SV28") (pin "5") (pinfunction "5_5") (pintype "passive"))
      (node (ref "SV31") (pin "5") (pinfunction "5_5") (pintype "passive"))
      (node (ref "SV32") (pin "5") (pinfunction "5_5") (pintype "passive"))
    )
    (net (code "267") (name "Net-(SV28-Pad6)") (class "Default")
      (node (ref "SV28") (pin "6") (pinfunction "6_6") (pintype "passive"))
      (node (ref "SV31") (pin "6") (pinfunction "6_6") (pintype "passive"))
      (node (ref "SV32") (pin "6") (pinfunction "6_6") (pintype "passive"))
    )
    (net (code "268") (name "Net-(SV28-Pad7)") (class "Default")
      (node (ref "SV28") (pin "7") (pinfunction "7_7") (pintype "passive"))
      (node (ref "SV31") (pin "7") (pinfunction "7_7") (pintype "passive"))
      (node (ref "SV32") (pin "7") (pinfunction "7_7") (pintype "passive"))
    )
    (net (code "269") (name "Net-(SV28-Pad8)") (class "Default")
      (node (ref "SV28") (pin "8") (pinfunction "8_8") (pintype "passive"))
      (node (ref "SV31") (pin "8") (pinfunction "8_8") (pintype "passive"))
      (node (ref "SV32") (pin "8") (pinfunction "8_8") (pintype "passive"))
    )
    (net (code "270") (name "Net-(SV28-Pad9)") (class "Default")
      (node (ref "SV28") (pin "9") (pinfunction "9_9") (pintype "passive"))
      (node (ref "SV31") (pin "9") (pinfunction "9_9") (pintype "passive"))
      (node (ref "SV32") (pin "9") (pinfunction "9_9") (pintype "passive"))
    )
    (net (code "271") (name "Net-(SV28-Pad10)") (class "Default")
      (node (ref "SV28") (pin "10") (pinfunction "10_10") (pintype "passive"))
      (node (ref "SV31") (pin "10") (pinfunction "10_10") (pintype "passive"))
      (node (ref "SV32") (pin "10") (pinfunction "10_10") (pintype "passive"))
    )
    (net (code "272") (name "Net-(SV28-Pad11)") (class "Default")
      (node (ref "SV28") (pin "11") (pinfunction "11_11") (pintype "passive"))
      (node (ref "SV31") (pin "11") (pinfunction "11_11") (pintype "passive"))
      (node (ref "SV32") (pin "11") (pinfunction "11_11") (pintype "passive"))
    )
    (net (code "273") (name "Net-(SV28-Pad12)") (class "Default")
      (node (ref "SV28") (pin "12") (pinfunction "12_12") (pintype "passive"))
      (node (ref "SV31") (pin "12") (pinfunction "12_12") (pintype "passive"))
      (node (ref "SV32") (pin "12") (pinfunction "12_12") (pintype "passive"))
    )
    (net (code "274") (name "Net-(SV28-Pad13)") (class "Default")
      (node (ref "SV28") (pin "13") (pinfunction "13_13") (pintype "passive"))
      (node (ref "SV31") (pin "13") (pinfunction "13_13") (pintype "passive"))
      (node (ref "SV32") (pin "13") (pinfunction "13_13") (pintype "passive"))
    )
    (net (code "275") (name "Net-(SV28-Pad14)") (class "Default")
      (node (ref "SV28") (pin "14") (pinfunction "14_14") (pintype "passive"))
      (node (ref "SV31") (pin "14") (pinfunction "14_14") (pintype "passive"))
      (node (ref "SV32") (pin "14") (pinfunction "14_14") (pintype "passive"))
    )
    (net (code "276") (name "Net-(SV28-Pad15)") (class "Default")
      (node (ref "SV28") (pin "15") (pinfunction "15_15") (pintype "passive"))
      (node (ref "SV31") (pin "15") (pinfunction "15_15") (pintype "passive"))
      (node (ref "SV32") (pin "15") (pinfunction "15_15") (pintype "passive"))
    )
    (net (code "277") (name "Net-(SV28-Pad16)") (class "Default")
      (node (ref "SV28") (pin "16") (pinfunction "16_16") (pintype "passive"))
      (node (ref "SV31") (pin "16") (pinfunction "16_16") (pintype "passive"))
      (node (ref "SV32") (pin "16") (pinfunction "16_16") (pintype "passive"))
    )
    (net (code "278") (name "Net-(SV28-Pad17)") (class "Default")
      (node (ref "SV28") (pin "17") (pinfunction "17_17") (pintype "passive"))
      (node (ref "SV31") (pin "17") (pinfunction "17_17") (pintype "passive"))
      (node (ref "SV32") (pin "17") (pinfunction "17_17") (pintype "passive"))
    )
    (net (code "279") (name "Net-(SV28-Pad18)") (class "Default")
      (node (ref "SV28") (pin "18") (pinfunction "18_18") (pintype "passive"))
      (node (ref "SV31") (pin "18") (pinfunction "18_18") (pintype "passive"))
      (node (ref "SV32") (pin "18") (pinfunction "18_18") (pintype "passive"))
    )
    (net (code "280") (name "Net-(SV28-Pad19)") (class "Default")
      (node (ref "SV28") (pin "19") (pinfunction "19_19") (pintype "passive"))
      (node (ref "SV31") (pin "19") (pinfunction "19_19") (pintype "passive"))
      (node (ref "SV32") (pin "19") (pinfunction "19_19") (pintype "passive"))
    )
    (net (code "281") (name "Net-(SV28-Pad20)") (class "Default")
      (node (ref "SV28") (pin "20") (pinfunction "20_20") (pintype "passive"))
      (node (ref "SV31") (pin "20") (pinfunction "20_20") (pintype "passive"))
      (node (ref "SV32") (pin "20") (pinfunction "20_20") (pintype "passive"))
    )
    (net (code "282") (name "Net-(U$1-5V)") (class "Default")
      (node (ref "SV44") (pin "3") (pinfunction "3_3") (pintype "passive"))
      (node (ref "SV45") (pin "3") (pinfunction "3_3") (pintype "passive"))
      (node (ref "SV46") (pin "3") (pinfunction "3_3") (pintype "passive"))
      (node (ref "U$1") (pin "P$18") (pinfunction "5V_P$18") (pintype "bidirectional"))
    )
    (net (code "283") (name "Net-(U$1-PA0)") (class "Default")
      (node (ref "SV47") (pin "5") (pinfunction "5_5") (pintype "passive"))
      (node (ref "SV48") (pin "5") (pinfunction "5_5") (pintype "passive"))
      (node (ref "SV50") (pin "5") (pinfunction "5_5") (pintype "passive"))
      (node (ref "U$1") (pin "P$36") (pinfunction "PA0_P$36") (pintype "bidirectional"))
    )
    (net (code "284") (name "Net-(U$1-PA1)") (class "Default")
      (node (ref "SV47") (pin "6") (pinfunction "6_6") (pintype "passive"))
      (node (ref "SV48") (pin "6") (pinfunction "6_6") (pintype "passive"))
      (node (ref "SV50") (pin "6") (pinfunction "6_6") (pintype "passive"))
      (node (ref "U$1") (pin "P$35") (pinfunction "PA1_P$35") (pintype "bidirectional"))
    )
    (net (code "285") (name "Net-(U$1-PA2)") (class "Default")
      (node (ref "SV47") (pin "7") (pinfunction "7_7") (pintype "passive"))
      (node (ref "SV48") (pin "7") (pinfunction "7_7") (pintype "passive"))
      (node (ref "SV50") (pin "7") (pinfunction "7_7") (pintype "passive"))
      (node (ref "U$1") (pin "P$34") (pinfunction "PA2_P$34") (pintype "bidirectional"))
    )
    (net (code "286") (name "Net-(U$1-PA3)") (class "Default")
      (node (ref "SV47") (pin "8") (pinfunction "8_8") (pintype "passive"))
      (node (ref "SV48") (pin "8") (pinfunction "8_8") (pintype "passive"))
      (node (ref "SV50") (pin "8") (pinfunction "8_8") (pintype "passive"))
      (node (ref "U$1") (pin "P$33") (pinfunction "PA3_P$33") (pintype "bidirectional"))
    )
    (net (code "287") (name "Net-(U$1-PA4)") (class "Default")
      (node (ref "SV47") (pin "9") (pinfunction "9_9") (pintype "passive"))
      (node (ref "SV48") (pin "9") (pinfunction "9_9") (pintype "passive"))
      (node (ref "SV50") (pin "9") (pinfunction "9_9") (pintype "passive"))
      (node (ref "U$1") (pin "P$32") (pinfunction "PA4_P$32") (pintype "bidirectional"))
    )
    (net (code "288") (name "Net-(U$1-PA5)") (class "Default")
      (node (ref "SV47") (pin "10") (pinfunction "10_10") (pintype "passive"))
      (node (ref "SV48") (pin "10") (pinfunction "10_10") (pintype "passive"))
      (node (ref "SV50") (pin "10") (pinfunction "10_10") (pintype "passive"))
      (node (ref "U$1") (pin "P$31") (pinfunction "PA5_P$31") (pintype "bidirectional"))
    )
    (net (code "289") (name "Net-(U$1-PA6)") (class "Default")
      (node (ref "SV47") (pin "11") (pinfunction "11_11") (pintype "passive"))
      (node (ref "SV48") (pin "11") (pinfunction "11_11") (pintype "passive"))
      (node (ref "SV50") (pin "11") (pinfunction "11_11") (pintype "passive"))
      (node (ref "U$1") (pin "P$30") (pinfunction "PA6_P$30") (pintype "bidirectional"))
    )
    (net (code "290") (name "Net-(U$1-PA7)") (class "Default")
      (node (ref "SV47") (pin "12") (pinfunction "12_12") (pintype "passive"))
      (node (ref "SV48") (pin "12") (pinfunction "12_12") (pintype "passive"))
      (node (ref "SV50") (pin "12") (pinfunction "12_12") (pintype "passive"))
      (node (ref "U$1") (pin "P$29") (pinfunction "PA7_P$29") (pintype "bidirectional"))
    )
    (net (code "291") (name "Net-(U$1-PA8)") (class "Default")
      (node (ref "SV44") (pin "16") (pinfunction "16_16") (pintype "passive"))
      (node (ref "SV45") (pin "16") (pinfunction "16_16") (pintype "passive"))
      (node (ref "SV46") (pin "16") (pinfunction "16_16") (pintype "passive"))
      (node (ref "U$1") (pin "P$5") (pinfunction "PA8_P$5") (pintype "bidirectional"))
    )
    (net (code "292") (name "Net-(U$1-PA9)") (class "Default")
      (node (ref "SV44") (pin "15") (pinfunction "15_15") (pintype "passive"))
      (node (ref "SV45") (pin "15") (pinfunction "15_15") (pintype "passive"))
      (node (ref "SV46") (pin "15") (pinfunction "15_15") (pintype "passive"))
      (node (ref "U$1") (pin "P$6") (pinfunction "PA9_P$6") (pintype "bidirectional"))
    )
    (net (code "293") (name "Net-(U$1-PA10)") (class "Default")
      (node (ref "SV44") (pin "14") (pinfunction "14_14") (pintype "passive"))
      (node (ref "SV45") (pin "14") (pinfunction "14_14") (pintype "passive"))
      (node (ref "SV46") (pin "14") (pinfunction "14_14") (pintype "passive"))
      (node (ref "U$1") (pin "P$7") (pinfunction "PA10_P$7") (pintype "bidirectional"))
    )
    (net (code "294") (name "Net-(U$1-PA11)") (class "Default")
      (node (ref "SV44") (pin "13") (pinfunction "13_13") (pintype "passive"))
      (node (ref "SV45") (pin "13") (pinfunction "13_13") (pintype "passive"))
      (node (ref "SV46") (pin "13") (pinfunction "13_13") (pintype "passive"))
      (node (ref "U$1") (pin "P$8") (pinfunction "PA11_P$8") (pintype "bidirectional"))
    )
    (net (code "295") (name "Net-(U$1-PA12)") (class "Default")
      (node (ref "SV44") (pin "12") (pinfunction "12_12") (pintype "passive"))
      (node (ref "SV45") (pin "12") (pinfunction "12_12") (pintype "passive"))
      (node (ref "SV46") (pin "12") (pinfunction "12_12") (pintype "passive"))
      (node (ref "U$1") (pin "P$9") (pinfunction "PA12_P$9") (pintype "bidirectional"))
    )
    (net (code "296") (name "Net-(U$1-PA15)") (class "Default")
      (node (ref "SV44") (pin "11") (pinfunction "11_11") (pintype "passive"))
      (node (ref "SV45") (pin "11") (pinfunction "11_11") (pintype "passive"))
      (node (ref "SV46") (pin "11") (pinfunction "11_11") (pintype "passive"))
      (node (ref "U$1") (pin "P$10") (pinfunction "PA15_P$10") (pintype "bidirectional"))
    )
    (net (code "297") (name "Net-(U$1-PB0)") (class "Default")
      (node (ref "SV47") (pin "13") (pinfunction "13_13") (pintype "passive"))
      (node (ref "SV48") (pin "13") (pinfunction "13_13") (pintype "passive"))
      (node (ref "SV50") (pin "13") (pinfunction "13_13") (pintype "passive"))
      (node (ref "U$1") (pin "P$28") (pinfunction "PB0_P$28") (pintype "bidirectional"))
    )
    (net (code "298") (name "Net-(U$1-PB1)") (class "Default")
      (node (ref "SV47") (pin "14") (pinfunction "14_14") (pintype "passive"))
      (node (ref "SV48") (pin "14") (pinfunction "14_14") (pintype "passive"))
      (node (ref "SV50") (pin "14") (pinfunction "14_14") (pintype "passive"))
      (node (ref "U$1") (pin "P$27") (pinfunction "PB1_P$27") (pintype "bidirectional"))
    )
    (net (code "299") (name "Net-(U$1-PB3)") (class "Default")
      (node (ref "SV44") (pin "10") (pinfunction "10_10") (pintype "passive"))
      (node (ref "SV45") (pin "10") (pinfunction "10_10") (pintype "passive"))
      (node (ref "SV46") (pin "10") (pinfunction "10_10") (pintype "passive"))
      (node (ref "U$1") (pin "P$11") (pinfunction "PB3_P$11") (pintype "bidirectional"))
    )
    (net (code "300") (name "Net-(U$1-PB4)") (class "Default")
      (node (ref "SV44") (pin "9") (pinfunction "9_9") (pintype "passive"))
      (node (ref "SV45") (pin "9") (pinfunction "9_9") (pintype "passive"))
      (node (ref "SV46") (pin "9") (pinfunction "9_9") (pintype "passive"))
      (node (ref "U$1") (pin "P$12") (pinfunction "PB4_P$12") (pintype "bidirectional"))
    )
    (net (code "301") (name "Net-(U$1-PB5)") (class "Default")
      (node (ref "SV44") (pin "8") (pinfunction "8_8") (pintype "passive"))
      (node (ref "SV45") (pin "8") (pinfunction "8_8") (pintype "passive"))
      (node (ref "SV46") (pin "8") (pinfunction "8_8") (pintype "passive"))
      (node (ref "U$1") (pin "P$13") (pinfunction "PB5_P$13") (pintype "bidirectional"))
    )
    (net (code "302") (name "Net-(U$1-PB6)") (class "Default")
      (node (ref "SV44") (pin "7") (pinfunction "7_7") (pintype "passive"))
      (node (ref "SV45") (pin "7") (pinfunction "7_7") (pintype "passive"))
      (node (ref "SV46") (pin "7") (pinfunction "7_7") (pintype "passive"))
      (node (ref "U$1") (pin "P$14") (pinfunction "PB6_P$14") (pintype "bidirectional"))
    )
    (net (code "303") (name "Net-(U$1-PB7)") (class "Default")
      (node (ref "SV44") (pin "6") (pinfunction "6_6") (pintype "passive"))
      (node (ref "SV45") (pin "6") (pinfunction "6_6") (pintype "passive"))
      (node (ref "SV46") (pin "6") (pinfunction "6_6") (pintype "passive"))
      (node (ref "U$1") (pin "P$15") (pinfunction "PB7_P$15") (pintype "bidirectional"))
    )
    (net (code "304") (name "Net-(U$1-PB8)") (class "Default")
      (node (ref "SV44") (pin "5") (pinfunction "5_5") (pintype "passive"))
      (node (ref "SV45") (pin "5") (pinfunction "5_5") (pintype "passive"))
      (node (ref "SV46") (pin "5") (pinfunction "5_5") (pintype "passive"))
      (node (ref "U$1") (pin "P$16") (pinfunction "PB8_P$16") (pintype "bidirectional"))
    )
    (net (code "305") (name "Net-(U$1-PB9)") (class "Default")
      (node (ref "SV44") (pin "4") (pinfunction "4_4") (pintype "passive"))
      (node (ref "SV45") (pin "4") (pinfunction "4_4") (pintype "passive"))
      (node (ref "SV46") (pin "4") (pinfunction "4_4") (pintype "passive"))
      (node (ref "U$1") (pin "P$17") (pinfunction "PB9_P$17") (pintype "bidirectional"))
    )
    (net (code "306") (name "Net-(U$1-PB10)") (class "Default")
      (node (ref "SV47") (pin "15") (pinfunction "15_15") (pintype "passive"))
      (node (ref "SV48") (pin "15") (pinfunction "15_15") (pintype "passive"))
      (node (ref "SV50") (pin "15") (pinfunction "15_15") (pintype "passive"))
      (node (ref "U$1") (pin "P$26") (pinfunction "PB10_P$26") (pintype "bidirectional"))
    )
    (net (code "307") (name "Net-(U$1-PB11)") (class "Default")
      (node (ref "SV47") (pin "16") (pinfunction "16_16") (pintype "passive"))
      (node (ref "SV48") (pin "16") (pinfunction "16_16") (pintype "passive"))
      (node (ref "SV50") (pin "16") (pinfunction "16_16") (pintype "passive"))
      (node (ref "U$1") (pin "P$25") (pinfunction "PB11_P$25") (pintype "bidirectional"))
    )
    (net (code "308") (name "Net-(U$1-PB12)") (class "Default")
      (node (ref "SV44") (pin "20") (pinfunction "20_20") (pintype "passive"))
      (node (ref "SV45") (pin "20") (pinfunction "20_20") (pintype "passive"))
      (node (ref "SV46") (pin "20") (pinfunction "20_20") (pintype "passive"))
      (node (ref "U$1") (pin "P$1") (pinfunction "PB12_P$1") (pintype "bidirectional"))
    )
    (net (code "309") (name "Net-(U$1-PB13)") (class "Default")
      (node (ref "SV44") (pin "19") (pinfunction "19_19") (pintype "passive"))
      (node (ref "SV45") (pin "19") (pinfunction "19_19") (pintype "passive"))
      (node (ref "SV46") (pin "19") (pinfunction "19_19") (pintype "passive"))
      (node (ref "U$1") (pin "P$2") (pinfunction "PB13_P$2") (pintype "bidirectional"))
    )
    (net (code "310") (name "Net-(U$1-PB14)") (class "Default")
      (node (ref "SV44") (pin "18") (pinfunction "18_18") (pintype "passive"))
      (node (ref "SV45") (pin "18") (pinfunction "18_18") (pintype "passive"))
      (node (ref "SV46") (pin "18") (pinfunction "18_18") (pintype "passive"))
      (node (ref "U$1") (pin "P$3") (pinfunction "PB14_P$3") (pintype "bidirectional"))
    )
    (net (code "311") (name "Net-(U$1-PB15)") (class "Default")
      (node (ref "SV44") (pin "17") (pinfunction "17_17") (pintype "passive"))
      (node (ref "SV45") (pin "17") (pinfunction "17_17") (pintype "passive"))
      (node (ref "SV46") (pin "17") (pinfunction "17_17") (pintype "passive"))
      (node (ref "U$1") (pin "P$4") (pinfunction "PB15_P$4") (pintype "bidirectional"))
    )
    (net (code "312") (name "Net-(U$1-PC13)") (class "Default")
      (node (ref "SV47") (pin "2") (pinfunction "2_2") (pintype "passive"))
      (node (ref "SV48") (pin "2") (pinfunction "2_2") (pintype "passive"))
      (node (ref "SV50") (pin "2") (pinfunction "2_2") (pintype "passive"))
      (node (ref "U$1") (pin "P$39") (pinfunction "PC13_P$39") (pintype "bidirectional"))
    )
    (net (code "313") (name "Net-(U$1-PC14)") (class "Default")
      (node (ref "SV47") (pin "3") (pinfunction "3_3") (pintype "passive"))
      (node (ref "SV48") (pin "3") (pinfunction "3_3") (pintype "passive"))
      (node (ref "SV50") (pin "3") (pinfunction "3_3") (pintype "passive"))
      (node (ref "U$1") (pin "P$38") (pinfunction "PC14_P$38") (pintype "bidirectional"))
    )
    (net (code "314") (name "Net-(U$1-PC15)") (class "Default")
      (node (ref "SV47") (pin "4") (pinfunction "4_4") (pintype "passive"))
      (node (ref "SV48") (pin "4") (pinfunction "4_4") (pintype "passive"))
      (node (ref "SV50") (pin "4") (pinfunction "4_4") (pintype "passive"))
      (node (ref "U$1") (pin "P$37") (pinfunction "PC15_P$37") (pintype "bidirectional"))
    )
    (net (code "315") (name "Net-(U$1-RESET)") (class "Default")
      (node (ref "SV47") (pin "17") (pinfunction "17_17") (pintype "passive"))
      (node (ref "SV48") (pin "17") (pinfunction "17_17") (pintype "passive"))
      (node (ref "SV50") (pin "17") (pinfunction "17_17") (pintype "passive"))
      (node (ref "U$1") (pin "P$24") (pinfunction "RESET_P$24") (pintype "bidirectional"))
    )
    (net (code "316") (name "Net-(U$1-VBAT)") (class "Default")
      (node (ref "SV47") (pin "1") (pinfunction "1_1") (pintype "passive"))
      (node (ref "SV48") (pin "1") (pinfunction "1_1") (pintype "passive"))
      (node (ref "SV50") (pin "1") (pinfunction "1_1") (pintype "passive"))
      (node (ref "U$1") (pin "P$40") (pinfunction "VBAT_P$40") (pintype "bidirectional"))
    )
    (net (code "317") (name "VCC") (class "Default")
      (node (ref "C1") (pin "1") (pinfunction "1_1") (pintype "passive"))
      (node (ref "C10") (pin "1") (pinfunction "1_1") (pintype "passive"))
      (node (ref "C2") (pin "1") (pinfunction "1_1") (pintype "passive"))
      (node (ref "C3") (pin "1") (pinfunction "1_1") (pintype "passive"))
      (node (ref "C4") (pin "1") (pinfunction "1_1") (pintype "passive"))
      (node (ref "C5") (pin "1") (pinfunction "1_1") (pintype "passive"))
      (node (ref "C6") (pin "1") (pinfunction "1_1") (pintype "passive"))
      (node (ref "C7") (pin "1") (pinfunction "1_1") (pintype "passive"))
      (node (ref "C8") (pin "1") (pinfunction "1_1") (pintype "passive"))
      (node (ref "C9") (pin "1") (pinfunction "1_1") (pintype "passive"))
      (node (ref "SV10") (pin "1") (pinfunction "1_1") (pintype "passive"))
      (node (ref "SV10") (pin "10") (pinfunction "10_10") (pintype "passive"))
      (node (ref "SV10") (pin "11") (pinfunction "11_11") (pintype "passive"))
      (node (ref "SV10") (pin "12") (pinfunction "12_12") (pintype "passive"))
      (node (ref "SV10") (pin "13") (pinfunction "13_13") (pintype "passive"))
      (node (ref "SV10") (pin "14") (pinfunction "14_14") (pintype "passive"))
      (node (ref "SV10") (pin "15") (pinfunction "15_15") (pintype "passive"))
      (node (ref "SV10") (pin "16") (pinfunction "16_16") (pintype "passive"))
      (node (ref "SV10") (pin "17") (pinfunction "17_17") (pintype "passive"))
      (node (ref "SV10") (pin "18") (pinfunction "18_18") (pintype "passive"))
      (node (ref "SV10") (pin "19") (pinfunction "19_19") (pintype "passive"))
      (node (ref "SV10") (pin "2") (pinfunction "2_2") (pintype "passive"))
      (node (ref "SV10") (pin "20") (pinfunction "20_20") (pintype "passive"))
      (node (ref "SV10") (pin "3") (pinfunction "3_3") (pintype "passive"))
      (node (ref "SV10") (pin "4") (pinfunction "4_4") (pintype "passive"))
      (node (ref "SV10") (pin "5") (pinfunction "5_5") (pintype "passive"))
      (node (ref "SV10") (pin "6") (pinfunction "6_6") (pintype "passive"))
      (node (ref "SV10") (pin "7") (pinfunction "7_7") (pintype "passive"))
      (node (ref "SV10") (pin "8") (pinfunction "8_8") (pintype "passive"))
      (node (ref "SV10") (pin "9") (pinfunction "9_9") (pintype "passive"))
      (node (ref "SV18") (pin "1") (pinfunction "1_1") (pintype "passive"))
      (node (ref "SV18") (pin "10") (pinfunction "10_10") (pintype "passive"))
      (node (ref "SV18") (pin "11") (pinfunction "11_11") (pintype "passive"))
      (node (ref "SV18") (pin "12") (pinfunction "12_12") (pintype "passive"))
      (node (ref "SV18") (pin "13") (pinfunction "13_13") (pintype "passive"))
      (node (ref "SV18") (pin "14") (pinfunction "14_14") (pintype "passive"))
      (node (ref "SV18") (pin "15") (pinfunction "15_15") (pintype "passive"))
      (node (ref "SV18") (pin "16") (pinfunction "16_16") (pintype "passive"))
      (node (ref "SV18") (pin "17") (pinfunction "17_17") (pintype "passive"))
      (node (ref "SV18") (pin "18") (pinfunction "18_18") (pintype "passive"))
      (node (ref "SV18") (pin "19") (pinfunction "19_19") (pintype "passive"))
      (node (ref "SV18") (pin "2") (pinfunction "2_2") (pintype "passive"))
      (node (ref "SV18") (pin "20") (pinfunction "20_20") (pintype "passive"))
      (node (ref "SV18") (pin "3") (pinfunction "3_3") (pintype "passive"))
      (node (ref "SV18") (pin "4") (pinfunction "4_4") (pintype "passive"))
      (node (ref "SV18") (pin "5") (pinfunction "5_5") (pintype "passive"))
      (node (ref "SV18") (pin "6") (pinfunction "6_6") (pintype "passive"))
      (node (ref "SV18") (pin "7") (pinfunction "7_7") (pintype "passive"))
      (node (ref "SV18") (pin "8") (pinfunction "8_8") (pintype "passive"))
      (node (ref "SV18") (pin "9") (pinfunction "9_9") (pintype "passive"))
      (node (ref "SV43") (pin "1") (pinfunction "1_1") (pintype "passive"))
      (node (ref "SV43") (pin "10") (pinfunction "10_10") (pintype "passive"))
      (node (ref "SV43") (pin "11") (pinfunction "11_11") (pintype "passive"))
      (node (ref "SV43") (pin "12") (pinfunction "12_12") (pintype "passive"))
      (node (ref "SV43") (pin "13") (pinfunction "13_13") (pintype "passive"))
      (node (ref "SV43") (pin "14") (pinfunction "14_14") (pintype "passive"))
      (node (ref "SV43") (pin "15") (pinfunction "15_15") (pintype "passive"))
      (node (ref "SV43") (pin "16") (pinfunction "16_16") (pintype "passive"))
      (node (ref "SV43") (pin "17") (pinfunction "17_17") (pintype "passive"))
      (node (ref "SV43") (pin "18") (pinfunction "18_18") (pintype "passive"))
      (node (ref "SV43") (pin "19") (pinfunction "19_19") (pintype "passive"))
      (node (ref "SV43") (pin "2") (pinfunction "2_2") (pintype "passive"))
      (node (ref "SV43") (pin "20") (pinfunction "20_20") (pintype "passive"))
      (node (ref "SV43") (pin "3") (pinfunction "3_3") (pintype "passive"))
      (node (ref "SV43") (pin "4") (pinfunction "4_4") (pintype "passive"))
      (node (ref "SV43") (pin "5") (pinfunction "5_5") (pintype "passive"))
      (node (ref "SV43") (pin "6") (pinfunction "6_6") (pintype "passive"))
      (node (ref "SV43") (pin "7") (pinfunction "7_7") (pintype "passive"))
      (node (ref "SV43") (pin "8") (pinfunction "8_8") (pintype "passive"))
      (node (ref "SV43") (pin "9") (pinfunction "9_9") (pintype "passive"))
      (node (ref "SV44") (pin "1") (pinfunction "1_1") (pintype "passive"))
      (node (ref "SV45") (pin "1") (pinfunction "1_1") (pintype "passive"))
      (node (ref "SV46") (pin "1") (pinfunction "1_1") (pintype "passive"))
      (node (ref "SV47") (pin "18") (pinfunction "18_18") (pintype "passive"))
      (node (ref "SV48") (pin "18") (pinfunction "18_18") (pintype "passive"))
      (node (ref "SV49") (pin "1") (pinfunction "1_1") (pintype "passive"))
      (node (ref "SV49") (pin "10") (pinfunction "10_10") (pintype "passive"))
      (node (ref "SV49") (pin "11") (pinfunction "11_11") (pintype "passive"))
      (node (ref "SV49") (pin "12") (pinfunction "12_12") (pintype "passive"))
      (node (ref "SV49") (pin "13") (pinfunction "13_13") (pintype "passive"))
      (node (ref "SV49") (pin "14") (pinfunction "14_14") (pintype "passive"))
      (node (ref "SV49") (pin "15") (pinfunction "15_15") (pintype "passive"))
      (node (ref "SV49") (pin "16") (pinfunction "16_16") (pintype "passive"))
      (node (ref "SV49") (pin "17") (pinfunction "17_17") (pintype "passive"))
      (node (ref "SV49") (pin "18") (pinfunction "18_18") (pintype "passive"))
      (node (ref "SV49") (pin "19") (pinfunction "19_19") (pintype "passive"))
      (node (ref "SV49") (pin "2") (pinfunction "2_2") (pintype "passive"))
      (node (ref "SV49") (pin "20") (pinfunction "20_20") (pintype "passive"))
      (node (ref "SV49") (pin "3") (pinfunction "3_3") (pintype "passive"))
      (node (ref "SV49") (pin "4") (pinfunction "4_4") (pintype "passive"))
      (node (ref "SV49") (pin "5") (pinfunction "5_5") (pintype "passive"))
      (node (ref "SV49") (pin "6") (pinfunction "6_6") (pintype "passive"))
      (node (ref "SV49") (pin "7") (pinfunction "7_7") (pintype "passive"))
      (node (ref "SV49") (pin "8") (pinfunction "8_8") (pintype "passive"))
      (node (ref "SV49") (pin "9") (pinfunction "9_9") (pintype "passive"))
      (node (ref "SV50") (pin "18") (pinfunction "18_18") (pintype "passive"))
      (node (ref "SV53") (pin "1") (pinfunction "1_1") (pintype "passive"))
      (node (ref "SV53") (pin "10") (pinfunction "10_10") (pintype "passive"))
      (node (ref "SV53") (pin "11") (pinfunction "11_11") (pintype "passive"))
      (node (ref "SV53") (pin "12") (pinfunction "12_12") (pintype "passive"))
      (node (ref "SV53") (pin "13") (pinfunction "13_13") (pintype "passive"))
      (node (ref "SV53") (pin "14") (pinfunction "14_14") (pintype "passive"))
      (node (ref "SV53") (pin "15") (pinfunction "15_15") (pintype "passive"))
      (node (ref "SV53") (pin "16") (pinfunction "16_16") (pintype "passive"))
      (node (ref "SV53") (pin "17") (pinfunction "17_17") (pintype "passive"))
      (node (ref "SV53") (pin "18") (pinfunction "18_18") (pintype "passive"))
      (node (ref "SV53") (pin "19") (pinfunction "19_19") (pintype "passive"))
      (node (ref "SV53") (pin "2") (pinfunction "2_2") (pintype "passive"))
      (node (ref "SV53") (pin "20") (pinfunction "20_20") (pintype "passive"))
      (node (ref "SV53") (pin "3") (pinfunction "3_3") (pintype "passive"))
      (node (ref "SV53") (pin "4") (pinfunction "4_4") (pintype "passive"))
      (node (ref "SV53") (pin "5") (pinfunction "5_5") (pintype "passive"))
      (node (ref "SV53") (pin "6") (pinfunction "6_6") (pintype "passive"))
      (node (ref "SV53") (pin "7") (pinfunction "7_7") (pintype "passive"))
      (node (ref "SV53") (pin "8") (pinfunction "8_8") (pintype "passive"))
      (node (ref "SV53") (pin "9") (pinfunction "9_9") (pintype "passive"))
      (node (ref "SV54") (pin "1") (pinfunction "1_1") (pintype "passive"))
      (node (ref "SV54") (pin "10") (pinfunction "10_10") (pintype "passive"))
      (node (ref "SV54") (pin "11") (pinfunction "11_11") (pintype "passive"))
      (node (ref "SV54") (pin "12") (pinfunction "12_12") (pintype "passive"))
      (node (ref "SV54") (pin "13") (pinfunction "13_13") (pintype "passive"))
      (node (ref "SV54") (pin "14") (pinfunction "14_14") (pintype "passive"))
      (node (ref "SV54") (pin "15") (pinfunction "15_15") (pintype "passive"))
      (node (ref "SV54") (pin "16") (pinfunction "16_16") (pintype "passive"))
      (node (ref "SV54") (pin "17") (pinfunction "17_17") (pintype "passive"))
      (node (ref "SV54") (pin "18") (pinfunction "18_18") (pintype "passive"))
      (node (ref "SV54") (pin "19") (pinfunction "19_19") (pintype "passive"))
      (node (ref "SV54") (pin "2") (pinfunction "2_2") (pintype "passive"))
      (node (ref "SV54") (pin "20") (pinfunction "20_20") (pintype "passive"))
      (node (ref "SV54") (pin "3") (pinfunction "3_3") (pintype "passive"))
      (node (ref "SV54") (pin "4") (pinfunction "4_4") (pintype "passive"))
      (node (ref "SV54") (pin "5") (pinfunction "5_5") (pintype "passive"))
      (node (ref "SV54") (pin "6") (pinfunction "6_6") (pintype "passive"))
      (node (ref "SV54") (pin "7") (pinfunction "7_7") (pintype "passive"))
      (node (ref "SV54") (pin "8") (pinfunction "8_8") (pintype "passive"))
      (node (ref "SV54") (pin "9") (pinfunction "9_9") (pintype "passive"))
      (node (ref "U$1") (pin "P$20") (pinfunction "3.3V1_P$20") (pintype "bidirectional"))
      (node (ref "U$1") (pin "P$23") (pinfunction "3.3V_P$23") (pintype "bidirectional"))
    )
    (net (code "318") (name "unconnected-(IC5A-1A-Pad2)") (class "Default")
      (node (ref "IC5") (pin "2") (pinfunction "1A_2") (pintype "input"))
    )
    (net (code "319") (name "unconnected-(IC5A-1B-Pad3)") (class "Default")
      (node (ref "IC5") (pin "3") (pinfunction "1B_3") (pintype "input"))
    )
    (net (code "320") (name "unconnected-(IC5A-1Y-Pad4)") (class "Default")
      (node (ref "IC5") (pin "4") (pinfunction "1Y_4") (pintype "output"))
    )
    (net (code "321") (name "unconnected-(IC5A-2A-Pad5)") (class "Default")
      (node (ref "IC5") (pin "5") (pinfunction "2A_5") (pintype "input"))
    )
    (net (code "322") (name "unconnected-(IC5A-2B-Pad6)") (class "Default")
      (node (ref "IC5") (pin "6") (pinfunction "2B_6") (pintype "input"))
    )
    (net (code "323") (name "unconnected-(IC5A-2Y-Pad7)") (class "Default")
      (node (ref "IC5") (pin "7") (pinfunction "2Y_7") (pintype "output"))
    )
    (net (code "324") (name "unconnected-(IC5A-3A-Pad11)") (class "Default")
      (node (ref "IC5") (pin "11") (pinfunction "3A_11") (pintype "input"))
    )
    (net (code "325") (name "unconnected-(IC5A-3B-Pad10)") (class "Default")
      (node (ref "IC5") (pin "10") (pinfunction "3B_10") (pintype "input"))
    )
    (net (code "326") (name "unconnected-(IC5A-3Y-Pad9)") (class "Default")
      (node (ref "IC5") (pin "9") (pinfunction "3Y_9") (pintype "output"))
    )
    (net (code "327") (name "unconnected-(IC5A-4A-Pad14)") (class "Default")
      (node (ref "IC5") (pin "14") (pinfunction "4A_14") (pintype "input"))
    )
    (net (code "328") (name "unconnected-(IC5A-4B-Pad13)") (class "Default")
      (node (ref "IC5") (pin "13") (pinfunction "4B_13") (pintype "input"))
    )
    (net (code "329") (name "unconnected-(IC5A-4Y-Pad12)") (class "Default")
      (node (ref "IC5") (pin "12") (pinfunction "4Y_12") (pintype "output"))
    )
    (net (code "330") (name "unconnected-(IC5A-G-Pad15)") (class "Default")
      (node (ref "IC5") (pin "15") (pinfunction "G_15") (pintype "input"))
    )
    (net (code "331") (name "unconnected-(IC5A-~{A}{slash}B-Pad1)") (class "Default")
      (node (ref "IC5") (pin "1") (pinfunction "~{A}/B_1") (pintype "input"))
    )
    (net (code "332") (name "unconnected-(IC8A-1A-Pad2)") (class "Default")
      (node (ref "IC8") (pin "2") (pinfunction "1A_2") (pintype "input"))
    )
    (net (code "333") (name "unconnected-(IC8A-1B-Pad3)") (class "Default")
      (node (ref "IC8") (pin "3") (pinfunction "1B_3") (pintype "input"))
    )
    (net (code "334") (name "unconnected-(IC8A-1Y-Pad4)") (class "Default")
      (node (ref "IC8") (pin "4") (pinfunction "1Y_4") (pintype "output"))
    )
    (net (code "335") (name "unconnected-(IC8A-2A-Pad5)") (class "Default")
      (node (ref "IC8") (pin "5") (pinfunction "2A_5") (pintype "input"))
    )
    (net (code "336") (name "unconnected-(IC8A-2B-Pad6)") (class "Default")
      (node (ref "IC8") (pin "6") (pinfunction "2B_6") (pintype "input"))
    )
    (net (code "337") (name "unconnected-(IC8A-2Y-Pad7)") (class "Default")
      (node (ref "IC8") (pin "7") (pinfunction "2Y_7") (pintype "output"))
    )
    (net (code "338") (name "unconnected-(IC8A-3A-Pad11)") (class "Default")
      (node (ref "IC8") (pin "11") (pinfunction "3A_11") (pintype "input"))
    )
    (net (code "339") (name "unconnected-(IC8A-3B-Pad10)") (class "Default")
      (node (ref "IC8") (pin "10") (pinfunction "3B_10") (pintype "input"))
    )
    (net (code "340") (name "unconnected-(IC8A-3Y-Pad9)") (class "Default")
      (node (ref "IC8") (pin "9") (pinfunction "3Y_9") (pintype "output"))
    )
    (net (code "341") (name "unconnected-(IC8A-4A-Pad14)") (class "Default")
      (node (ref "IC8") (pin "14") (pinfunction "4A_14") (pintype "input"))
    )
    (net (code "342") (name "unconnected-(IC8A-4B-Pad13)") (class "Default")
      (node (ref "IC8") (pin "13") (pinfunction "4B_13") (pintype "input"))
    )
    (net (code "343") (name "unconnected-(IC8A-4Y-Pad12)") (class "Default")
      (node (ref "IC8") (pin "12") (pinfunction "4Y_12") (pintype "output"))
    )
    (net (code "344") (name "unconnected-(IC8A-G-Pad15)") (class "Default")
      (node (ref "IC8") (pin "15") (pinfunction "G_15") (pintype "input"))
    )
    (net (code "345") (name "unconnected-(IC8A-~{A}{slash}B-Pad1)") (class "Default")
      (node (ref "IC8") (pin "1") (pinfunction "~{A}/B_1") (pintype "input"))
    )
    (net (code "346") (name "unconnected-(IC9A-1A-Pad2)") (class "Default")
      (node (ref "IC9") (pin "2") (pinfunction "1A_2") (pintype "input"))
    )
    (net (code "347") (name "unconnected-(IC9A-1B-Pad3)") (class "Default")
      (node (ref "IC9") (pin "3") (pinfunction "1B_3") (pintype "input"))
    )
    (net (code "348") (name "unconnected-(IC9A-1Y-Pad4)") (class "Default")
      (node (ref "IC9") (pin "4") (pinfunction "1Y_4") (pintype "output"))
    )
    (net (code "349") (name "unconnected-(IC9A-2A-Pad5)") (class "Default")
      (node (ref "IC9") (pin "5") (pinfunction "2A_5") (pintype "input"))
    )
    (net (code "350") (name "unconnected-(IC9A-2B-Pad6)") (class "Default")
      (node (ref "IC9") (pin "6") (pinfunction "2B_6") (pintype "input"))
    )
    (net (code "351") (name "unconnected-(IC9A-2Y-Pad7)") (class "Default")
      (node (ref "IC9") (pin "7") (pinfunction "2Y_7") (pintype "output"))
    )
    (net (code "352") (name "unconnected-(IC9A-3A-Pad11)") (class "Default")
      (node (ref "IC9") (pin "11") (pinfunction "3A_11") (pintype "input"))
    )
    (net (code "353") (name "unconnected-(IC9A-3B-Pad10)") (class "Default")
      (node (ref "IC9") (pin "10") (pinfunction "3B_10") (pintype "input"))
    )
    (net (code "354") (name "unconnected-(IC9A-3Y-Pad9)") (class "Default")
      (node (ref "IC9") (pin "9") (pinfunction "3Y_9") (pintype "output"))
    )
    (net (code "355") (name "unconnected-(IC9A-4A-Pad14)") (class "Default")
      (node (ref "IC9") (pin "14") (pinfunction "4A_14") (pintype "input"))
    )
    (net (code "356") (name "unconnected-(IC9A-4B-Pad13)") (class "Default")
      (node (ref "IC9") (pin "13") (pinfunction "4B_13") (pintype "input"))
    )
    (net (code "357") (name "unconnected-(IC9A-4Y-Pad12)") (class "Default")
      (node (ref "IC9") (pin "12") (pinfunction "4Y_12") (pintype "output"))
    )
    (net (code "358") (name "unconnected-(IC9A-G-Pad15)") (class "Default")
      (node (ref "IC9") (pin "15") (pinfunction "G_15") (pintype "input"))
    )
    (net (code "359") (name "unconnected-(IC9A-~{A}{slash}B-Pad1)") (class "Default")
      (node (ref "IC9") (pin "1") (pinfunction "~{A}/B_1") (pintype "input"))
    )
    (net (code "360") (name "unconnected-(IC10A-1A-Pad2)") (class "Default")
      (node (ref "IC10") (pin "2") (pinfunction "1A_2") (pintype "input"))
    )
    (net (code "361") (name "unconnected-(IC10A-1B-Pad3)") (class "Default")
      (node (ref "IC10") (pin "3") (pinfunction "1B_3") (pintype "input"))
    )
    (net (code "362") (name "unconnected-(IC10A-1Y-Pad4)") (class "Default")
      (node (ref "IC10") (pin "4") (pinfunction "1Y_4") (pintype "output"))
    )
    (net (code "363") (name "unconnected-(IC10A-2A-Pad5)") (class "Default")
      (node (ref "IC10") (pin "5") (pinfunction "2A_5") (pintype "input"))
    )
    (net (code "364") (name "unconnected-(IC10A-2B-Pad6)") (class "Default")
      (node (ref "IC10") (pin "6") (pinfunction "2B_6") (pintype "input"))
    )
    (net (code "365") (name "unconnected-(IC10A-2Y-Pad7)") (class "Default")
      (node (ref "IC10") (pin "7") (pinfunction "2Y_7") (pintype "output"))
    )
    (net (code "366") (name "unconnected-(IC10A-3A-Pad11)") (class "Default")
      (node (ref "IC10") (pin "11") (pinfunction "3A_11") (pintype "input"))
    )
    (net (code "367") (name "unconnected-(IC10A-3B-Pad10)") (class "Default")
      (node (ref "IC10") (pin "10") (pinfunction "3B_10") (pintype "input"))
    )
    (net (code "368") (name "unconnected-(IC10A-3Y-Pad9)") (class "Default")
      (node (ref "IC10") (pin "9") (pinfunction "3Y_9") (pintype "output"))
    )
    (net (code "369") (name "unconnected-(IC10A-4A-Pad14)") (class "Default")
      (node (ref "IC10") (pin "14") (pinfunction "4A_14") (pintype "input"))
    )
    (net (code "370") (name "unconnected-(IC10A-4B-Pad13)") (class "Default")
      (node (ref "IC10") (pin "13") (pinfunction "4B_13") (pintype "input"))
    )
    (net (code "371") (name "unconnected-(IC10A-4Y-Pad12)") (class "Default")
      (node (ref "IC10") (pin "12") (pinfunction "4Y_12") (pintype "output"))
    )
    (net (code "372") (name "unconnected-(IC10A-G-Pad15)") (class "Default")
      (node (ref "IC10") (pin "15") (pinfunction "G_15") (pintype "input"))
    )
    (net (code "373") (name "unconnected-(IC10A-~{A}{slash}B-Pad1)") (class "Default")
      (node (ref "IC10") (pin "1") (pinfunction "~{A}/B_1") (pintype "input"))
    )
    (net (code "374") (name "unconnected-(IC12A-1A-Pad2)") (class "Default")
      (node (ref "IC12") (pin "2") (pinfunction "1A_2") (pintype "input"))
    )
    (net (code "375") (name "unconnected-(IC12A-1B-Pad3)") (class "Default")
      (node (ref "IC12") (pin "3") (pinfunction "1B_3") (pintype "input"))
    )
    (net (code "376") (name "unconnected-(IC12A-1Y-Pad4)") (class "Default")
      (node (ref "IC12") (pin "4") (pinfunction "1Y_4") (pintype "output"))
    )
    (net (code "377") (name "unconnected-(IC12A-2A-Pad5)") (class "Default")
      (node (ref "IC12") (pin "5") (pinfunction "2A_5") (pintype "input"))
    )
    (net (code "378") (name "unconnected-(IC12A-2B-Pad6)") (class "Default")
      (node (ref "IC12") (pin "6") (pinfunction "2B_6") (pintype "input"))
    )
    (net (code "379") (name "unconnected-(IC12A-2Y-Pad7)") (class "Default")
      (node (ref "IC12") (pin "7") (pinfunction "2Y_7") (pintype "output"))
    )
    (net (code "380") (name "unconnected-(IC12A-3A-Pad11)") (class "Default")
      (node (ref "IC12") (pin "11") (pinfunction "3A_11") (pintype "input"))
    )
    (net (code "381") (name "unconnected-(IC12A-3B-Pad10)") (class "Default")
      (node (ref "IC12") (pin "10") (pinfunction "3B_10") (pintype "input"))
    )
    (net (code "382") (name "unconnected-(IC12A-3Y-Pad9)") (class "Default")
      (node (ref "IC12") (pin "9") (pinfunction "3Y_9") (pintype "output"))
    )
    (net (code "383") (name "unconnected-(IC12A-4A-Pad14)") (class "Default")
      (node (ref "IC12") (pin "14") (pinfunction "4A_14") (pintype "input"))
    )
    (net (code "384") (name "unconnected-(IC12A-4B-Pad13)") (class "Default")
      (node (ref "IC12") (pin "13") (pinfunction "4B_13") (pintype "input"))
    )
    (net (code "385") (name "unconnected-(IC12A-4Y-Pad12)") (class "Default")
      (node (ref "IC12") (pin "12") (pinfunction "4Y_12") (pintype "output"))
    )
    (net (code "386") (name "unconnected-(IC12A-G-Pad15)") (class "Default")
      (node (ref "IC12") (pin "15") (pinfunction "G_15") (pintype "input"))
    )
    (net (code "387") (name "unconnected-(IC12A-~{A}{slash}B-Pad1)") (class "Default")
      (node (ref "IC12") (pin "1") (pinfunction "~{A}/B_1") (pintype "input"))
    )
    (net (code "388") (name "unconnected-(IC13A-1A-Pad2)") (class "Default")
      (node (ref "IC13") (pin "2") (pinfunction "1A_2") (pintype "input"))
    )
    (net (code "389") (name "unconnected-(IC13A-1B-Pad3)") (class "Default")
      (node (ref "IC13") (pin "3") (pinfunction "1B_3") (pintype "input"))
    )
    (net (code "390") (name "unconnected-(IC13A-1Y-Pad4)") (class "Default")
      (node (ref "IC13") (pin "4") (pinfunction "1Y_4") (pintype "output"))
    )
    (net (code "391") (name "unconnected-(IC13A-2A-Pad5)") (class "Default")
      (node (ref "IC13") (pin "5") (pinfunction "2A_5") (pintype "input"))
    )
    (net (code "392") (name "unconnected-(IC13A-2B-Pad6)") (class "Default")
      (node (ref "IC13") (pin "6") (pinfunction "2B_6") (pintype "input"))
    )
    (net (code "393") (name "unconnected-(IC13A-2Y-Pad7)") (class "Default")
      (node (ref "IC13") (pin "7") (pinfunction "2Y_7") (pintype "output"))
    )
    (net (code "394") (name "unconnected-(IC13A-3A-Pad11)") (class "Default")
      (node (ref "IC13") (pin "11") (pinfunction "3A_11") (pintype "input"))
    )
    (net (code "395") (name "unconnected-(IC13A-3B-Pad10)") (class "Default")
      (node (ref "IC13") (pin "10") (pinfunction "3B_10") (pintype "input"))
    )
    (net (code "396") (name "unconnected-(IC13A-3Y-Pad9)") (class "Default")
      (node (ref "IC13") (pin "9") (pinfunction "3Y_9") (pintype "output"))
    )
    (net (code "397") (name "unconnected-(IC13A-4A-Pad14)") (class "Default")
      (node (ref "IC13") (pin "14") (pinfunction "4A_14") (pintype "input"))
    )
    (net (code "398") (name "unconnected-(IC13A-4B-Pad13)") (class "Default")
      (node (ref "IC13") (pin "13") (pinfunction "4B_13") (pintype "input"))
    )
    (net (code "399") (name "unconnected-(IC13A-4Y-Pad12)") (class "Default")
      (node (ref "IC13") (pin "12") (pinfunction "4Y_12") (pintype "output"))
    )
    (net (code "400") (name "unconnected-(IC13A-G-Pad15)") (class "Default")
      (node (ref "IC13") (pin "15") (pinfunction "G_15") (pintype "input"))
    )
    (net (code "401") (name "unconnected-(IC13A-~{A}{slash}B-Pad1)") (class "Default")
      (node (ref "IC13") (pin "1") (pinfunction "~{A}/B_1") (pintype "input"))
    )
  )
)
